# SCH_BMS_1_2022-05-24.net
KiCad netlist of a schematic drawn in EasyEDA
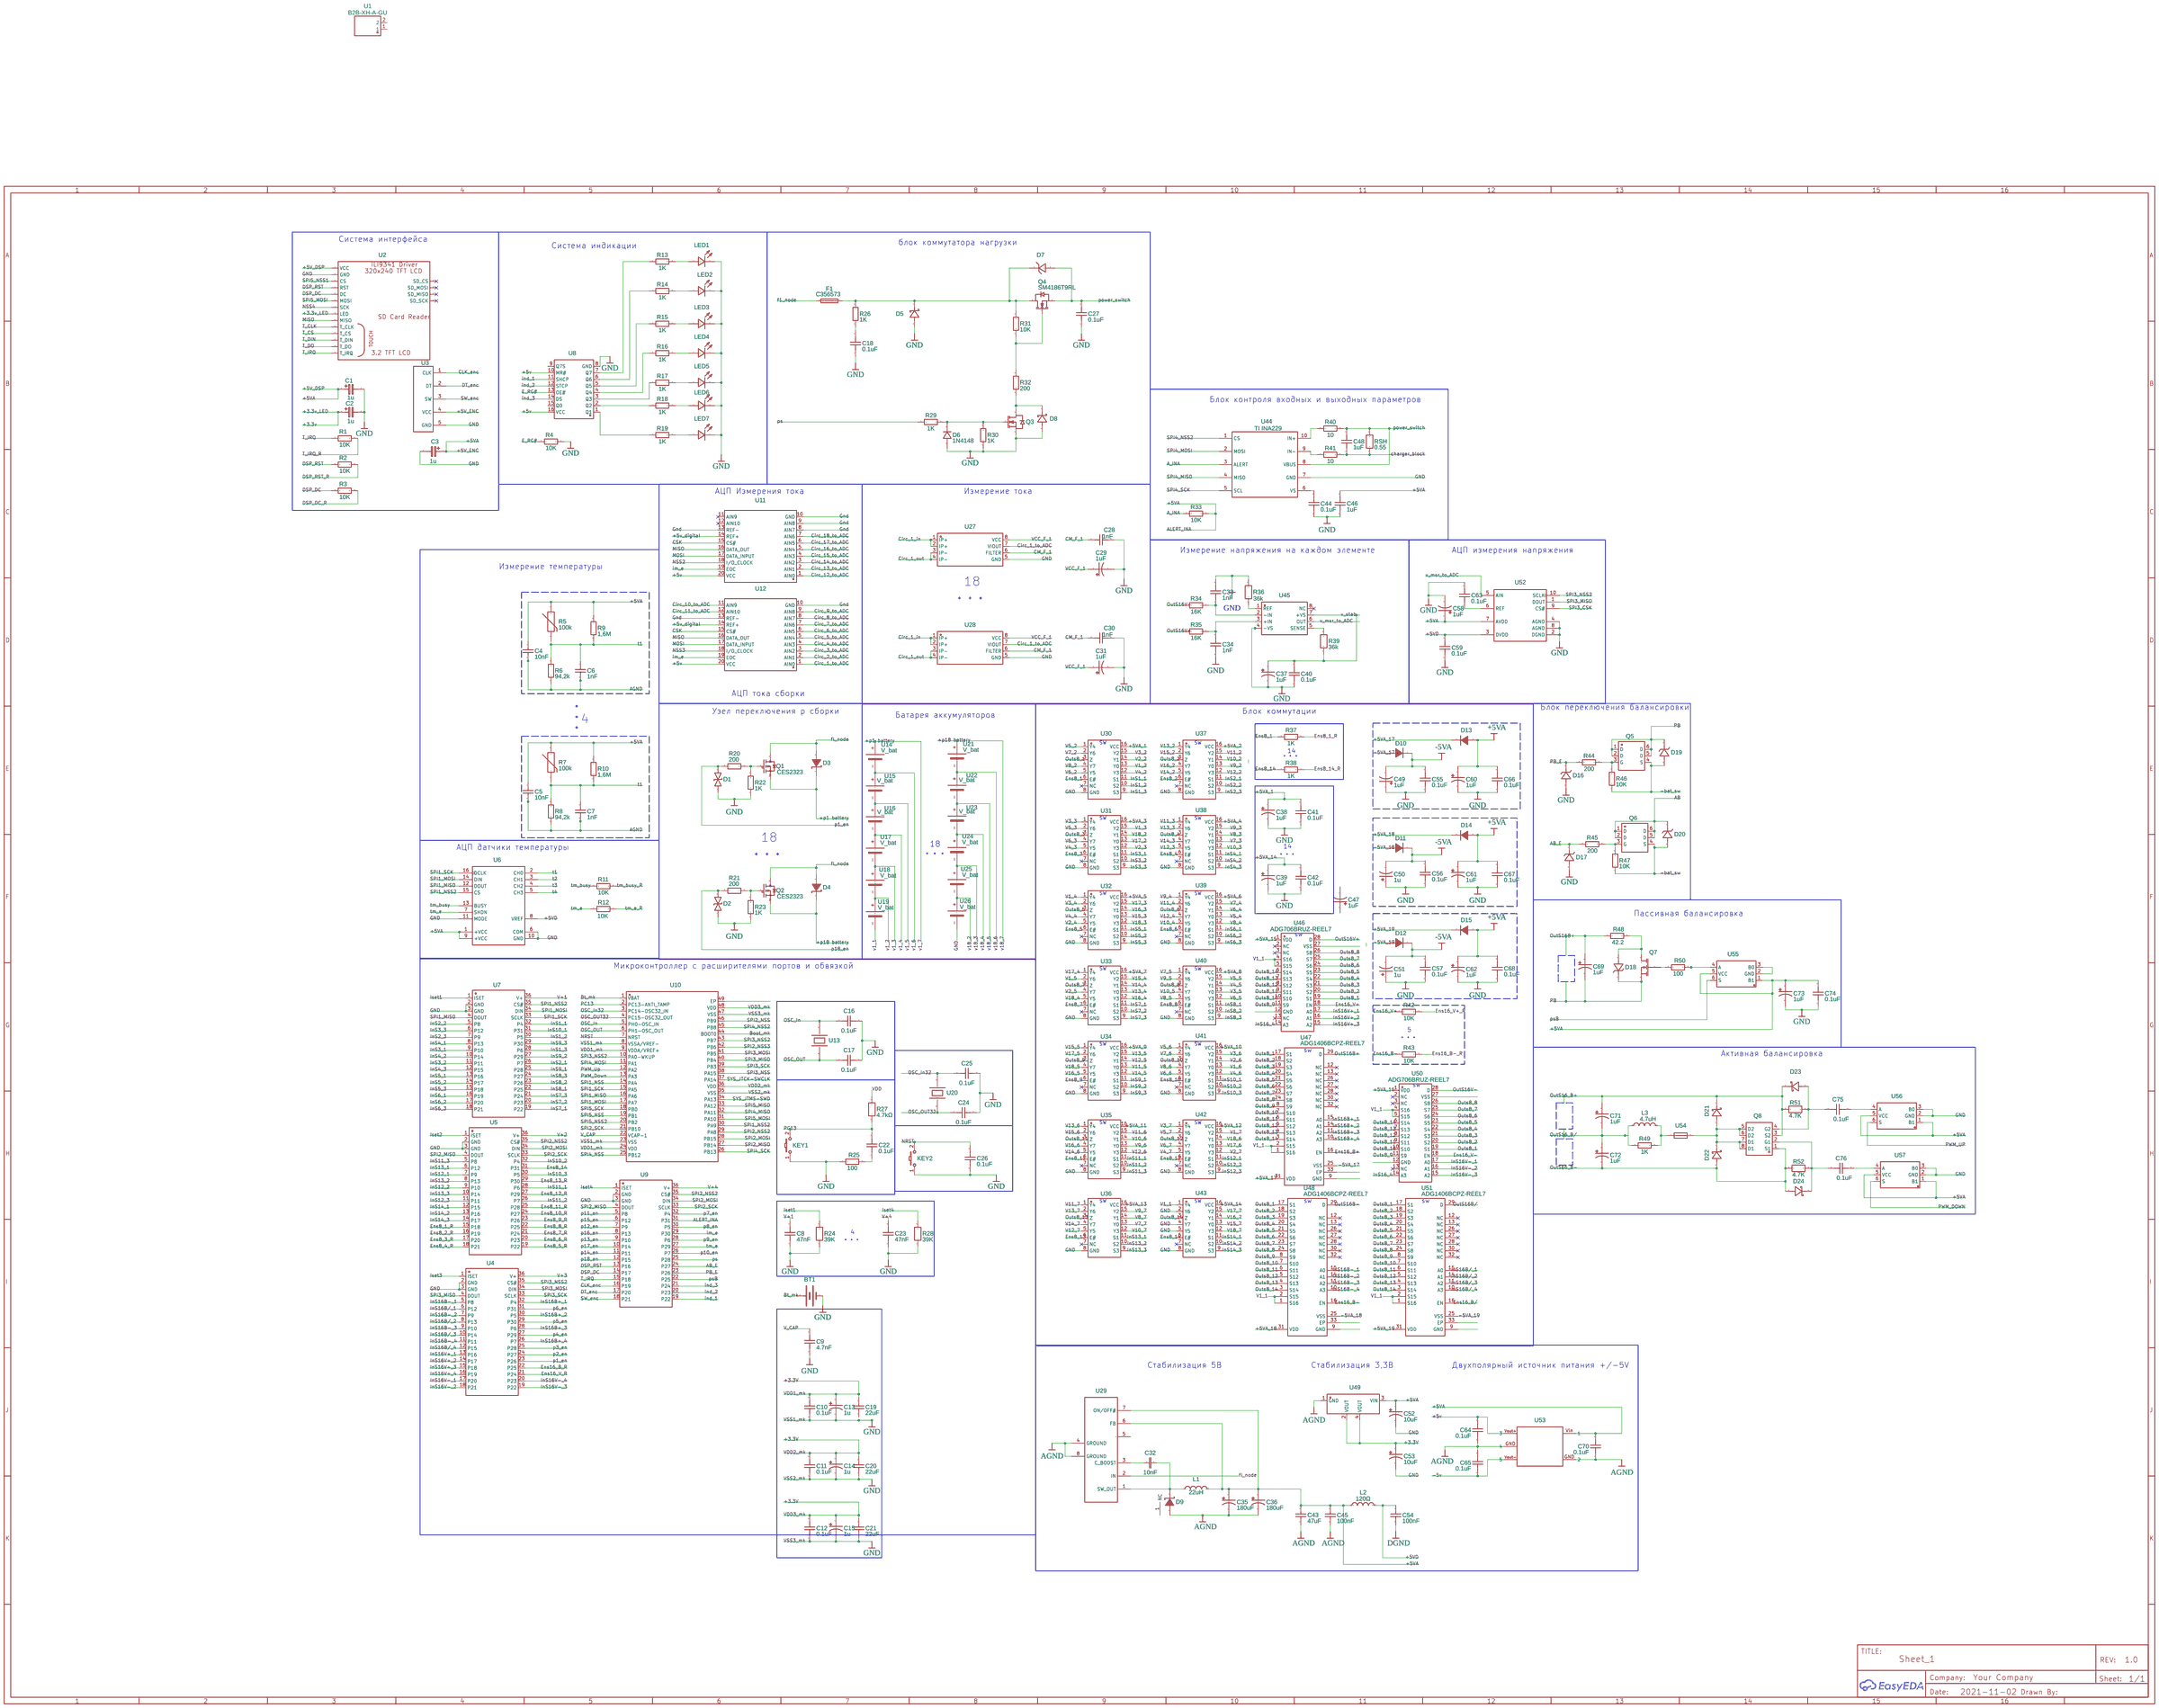
[diagram p0: schematic sheet]

(export (version "E")
  (design (tool "Eeschema 10.0.6"))
  (components
    (comp (ref "BT1")
      (value "1025")
      (fields (field (name "BOM_Supplier Part") "C238060"))
      (libsource (lib "") (part "1025"))
    )
    (comp (ref "C1") (value "1u") (libsource (lib "") (part "C_Tan_SMD_A_EU")))
    (comp (ref "C2") (value "1u") (libsource (lib "") (part "C_Tan_SMD_A_EU")))
    (comp (ref "C3") (value "1u") (libsource (lib "") (part "C_Tan_SMD_A_EU_1")))
    (comp (ref "C4")
      (value "10nF")
      (fields
        (field (name "BOM_Manufacturer Part") "GRM033R71A103KA01D")
        (field (name "BOM_Supplier Part") "C76941")
      )
      (libsource (lib "") (part "GRM033R71A103KA01D"))
    )
    (comp (ref "C5")
      (value "10nF")
      (fields
        (field (name "BOM_Manufacturer Part") "GRM033R71A103KA01D")
        (field (name "BOM_Supplier Part") "C76941")
      )
      (libsource (lib "") (part "GRM033R71A103KA01D"))
    )
    (comp (ref "C6")
      (value "1nF")
      (fields
        (field (name "BOM_Manufacturer Part") "GRM033R71A103KA01D")
        (field (name "BOM_Supplier Part") "C76941")
      )
      (libsource (lib "") (part "GRM033R71A103KA01D"))
    )
    (comp (ref "C7")
      (value "1nF")
      (fields
        (field (name "BOM_Manufacturer Part") "GRM033R71A103KA01D")
        (field (name "BOM_Supplier Part") "C76941")
      )
      (libsource (lib "") (part "GRM033R71A103KA01D"))
    )
    (comp (ref "C8")
      (value "47nF")
      (fields
        (field (name "BOM_Manufacturer Part") "GRT033R60J473KE01D")
        (field (name "BOM_Supplier Part") "C126621")
      )
      (libsource (lib "") (part "GRT033R60J473KE01D"))
    )
    (comp (ref "C9")
      (value "4.7nF")
      (fields
        (field (name "BOM_Manufacturer Part") "CC0201KRX7R5BB472")
        (field (name "BOM_Supplier Part") "C526949")
      )
      (libsource (lib "") (part "CC0201KRX7R5BB472"))
    )
    (comp (ref "C10")
      (value "0.1uF")
      (fields
        (field (name "BOM_Manufacturer Part") "0402BB104K160NGT")
        (field (name "BOM_Supplier Part") "C2173076")
      )
      (libsource (lib "") (part "0402BB104K160NGT"))
    )
    (comp (ref "C11")
      (value "0.1uF")
      (fields
        (field (name "BOM_Manufacturer Part") "0402BB104K160NGT")
        (field (name "BOM_Supplier Part") "C2173076")
      )
      (libsource (lib "") (part "0402BB104K160NGT"))
    )
    (comp (ref "C12")
      (value "0.1uF")
      (fields
        (field (name "BOM_Manufacturer Part") "0402BB104K160NGT")
        (field (name "BOM_Supplier Part") "C2173076")
      )
      (libsource (lib "") (part "0402BB104K160NGT"))
    )
    (comp (ref "C13")
      (value "1u")
      (fields
        (field (name "BOM_Manufacturer Part") "16SVP180MX")
        (field (name "BOM_Supplier Part") "C236288")
      )
      (libsource (lib "") (part "16SVP180MX"))
    )
    (comp (ref "C14")
      (value "1u")
      (fields
        (field (name "BOM_Manufacturer Part") "16SVP180MX")
        (field (name "BOM_Supplier Part") "C236288")
      )
      (libsource (lib "") (part "16SVP180MX"))
    )
    (comp (ref "C15")
      (value "1u")
      (fields
        (field (name "BOM_Manufacturer Part") "16SVP180MX")
        (field (name "BOM_Supplier Part") "C236288")
      )
      (libsource (lib "") (part "16SVP180MX"))
    )
    (comp (ref "C16")
      (value "0.1uF")
      (fields
        (field (name "BOM_Manufacturer Part") "0402BB104K160NGT")
        (field (name "BOM_Supplier Part") "C2173076")
      )
      (libsource (lib "") (part "0402BB104K160NGT_2"))
    )
    (comp (ref "C17")
      (value "0.1uF")
      (fields
        (field (name "BOM_Manufacturer Part") "0402BB104K160NGT")
        (field (name "BOM_Supplier Part") "C2173076")
      )
      (libsource (lib "") (part "0402BB104K160NGT_2"))
    )
    (comp (ref "C18")
      (value "0.1uF")
      (fields
        (field (name "BOM_Manufacturer Part") "0603BB104K500NGT")
        (field (name "BOM_Supplier Part") "C2168571")
      )
      (libsource (lib "") (part "0603BB104K500NGT"))
    )
    (comp (ref "C19")
      (value "22uF")
      (fields
        (field (name "BOM_Manufacturer Part") "GRM188B30J226MEA0D")
        (field (name "BOM_Supplier Part") "C15500")
      )
      (libsource (lib "") (part "GRM188B30J226MEA0D"))
    )
    (comp (ref "C20")
      (value "22uF")
      (fields
        (field (name "BOM_Manufacturer Part") "GRM188B30J226MEA0D")
        (field (name "BOM_Supplier Part") "C15500")
      )
      (libsource (lib "") (part "GRM188B30J226MEA0D"))
    )
    (comp (ref "C21")
      (value "22uF")
      (fields
        (field (name "BOM_Manufacturer Part") "GRM188B30J226MEA0D")
        (field (name "BOM_Supplier Part") "C15500")
      )
      (libsource (lib "") (part "GRM188B30J226MEA0D"))
    )
    (comp (ref "C22")
      (value "0.1uF")
      (fields
        (field (name "BOM_Manufacturer Part") "0402BB104K160NGT")
        (field (name "BOM_Supplier Part") "C2173076")
      )
      (libsource (lib "") (part "0402BB104K160NGT"))
    )
    (comp (ref "C23")
      (value "47nF")
      (fields
        (field (name "BOM_Manufacturer Part") "GRT033R60J473KE01D")
        (field (name "BOM_Supplier Part") "C126621")
      )
      (libsource (lib "") (part "GRT033R60J473KE01D"))
    )
    (comp (ref "C24")
      (value "0.1uF")
      (fields
        (field (name "BOM_Manufacturer Part") "0402BB104K160NGT")
        (field (name "BOM_Supplier Part") "C2173076")
      )
      (libsource (lib "") (part "0402BB104K160NGT_2"))
    )
    (comp (ref "C25")
      (value "0.1uF")
      (fields
        (field (name "BOM_Manufacturer Part") "0402BB104K160NGT")
        (field (name "BOM_Supplier Part") "C2173076")
      )
      (libsource (lib "") (part "0402BB104K160NGT_2"))
    )
    (comp (ref "C26")
      (value "0.1uF")
      (fields
        (field (name "BOM_Manufacturer Part") "0402BB104K160NGT")
        (field (name "BOM_Supplier Part") "C2173076")
      )
      (libsource (lib "") (part "0402BB104K160NGT"))
    )
    (comp (ref "C27")
      (value "0.1uF")
      (fields
        (field (name "BOM_Manufacturer Part") "0603BB104K500NGT")
        (field (name "BOM_Supplier Part") "C2168571")
      )
      (libsource (lib "") (part "0603BB104K500NGT"))
    )
    (comp (ref "C28")
      (value "1nF")
      (fields
        (field (name "BOM_Manufacturer Part") "0201B102J500CT")
        (field (name "BOM_Supplier Part") "C458605")
      )
      (libsource (lib "") (part "0201B102J500CT_1"))
    )
    (comp (ref "C29")
      (value "1uF")
      (fields
        (field (name "BOM_Manufacturer Part") "CA45-A-16V-1uF-K")
        (field (name "BOM_Supplier Part") "C140386")
      )
      (libsource (lib "") (part "CA45-A-16V-1UF-K"))
    )
    (comp (ref "C30")
      (value "1nF")
      (fields
        (field (name "BOM_Manufacturer Part") "0201B102J500CT")
        (field (name "BOM_Supplier Part") "C458605")
      )
      (libsource (lib "") (part "0201B102J500CT_1"))
    )
    (comp (ref "C31")
      (value "1uF")
      (fields
        (field (name "BOM_Manufacturer Part") "CA45-A-16V-1uF-K")
        (field (name "BOM_Supplier Part") "C140386")
      )
      (libsource (lib "") (part "CA45-A-16V-1UF-K"))
    )
    (comp (ref "C32")
      (value "10nF")
      (fields
        (field (name "BOM_Manufacturer Part") "C0603X5R103KDT")
        (field (name "BOM_Supplier Part") "C258479")
      )
      (libsource (lib "") (part "C0603X5R103KDT"))
    )
    (comp (ref "C33")
      (value "1nF")
      (fields
        (field (name "BOM_Manufacturer Part") "0201B102J500CT")
        (field (name "BOM_Supplier Part") "C458605")
      )
      (libsource (lib "") (part "0201B102J500CT"))
    )
    (comp (ref "C34")
      (value "1nF")
      (fields
        (field (name "BOM_Manufacturer Part") "0201B102J500CT")
        (field (name "BOM_Supplier Part") "C458605")
      )
      (libsource (lib "") (part "0201B102J500CT"))
    )
    (comp (ref "C35")
      (value "180uF")
      (fields
        (field (name "BOM_Manufacturer Part") "PCV1V181MCL2GS")
        (field (name "BOM_Supplier Part") "C488000")
      )
      (libsource (lib "") (part "PCV1V181MCL2GS"))
    )
    (comp (ref "C36")
      (value "180uF")
      (fields
        (field (name "BOM_Manufacturer Part") "PCV1V181MCL2GS")
        (field (name "BOM_Supplier Part") "C488000")
      )
      (libsource (lib "") (part "PCV1V181MCL2GS"))
    )
    (comp (ref "C37")
      (value "1uF")
      (fields
        (field (name "BOM_Manufacturer Part") "VE-010M1C0405-TRO")
        (field (name "BOM_Supplier Part") "C249445")
      )
      (libsource (lib "") (part "VE-010M1C0405-TRO"))
    )
    (comp (ref "C38")
      (value "1uF")
      (fields
        (field (name "BOM_Manufacturer Part") "VE-010M1C0405-TRO")
        (field (name "BOM_Supplier Part") "C249445")
      )
      (libsource (lib "") (part "VE-010M1C0405-TRO"))
    )
    (comp (ref "C39")
      (value "1uF")
      (fields
        (field (name "BOM_Manufacturer Part") "VE-010M1C0405-TRO")
        (field (name "BOM_Supplier Part") "C249445")
      )
      (libsource (lib "") (part "VE-010M1C0405-TRO"))
    )
    (comp (ref "C40")
      (value "0.1uF")
      (fields
        (field (name "BOM_Manufacturer Part") "0402BB104K160NGT")
        (field (name "BOM_Supplier Part") "C2173076")
      )
      (libsource (lib "") (part "0402BB104K160NGT"))
    )
    (comp (ref "C41")
      (value "0.1uF")
      (fields
        (field (name "BOM_Manufacturer Part") "0402BB104K160NGT")
        (field (name "BOM_Supplier Part") "C2173076")
      )
      (libsource (lib "") (part "0402BB104K160NGT"))
    )
    (comp (ref "C42")
      (value "0.1uF")
      (fields
        (field (name "BOM_Manufacturer Part") "0402BB104K160NGT")
        (field (name "BOM_Supplier Part") "C2173076")
      )
      (libsource (lib "") (part "0402BB104K160NGT"))
    )
    (comp (ref "C43")
      (value "47uF")
      (fields
        (field (name "BOM_Manufacturer Part") "0805X476M6R3")
        (field (name "BOM_Supplier Part") "C98821")
      )
      (libsource (lib "") (part "0805X476M6R3"))
    )
    (comp (ref "C44")
      (value "0.1uF")
      (fields
        (field (name "BOM_Manufacturer Part") "0402BB104K160NGT")
        (field (name "BOM_Supplier Part") "C2173076")
      )
      (libsource (lib "") (part "0402BB104K160NGT"))
    )
    (comp (ref "C45")
      (value "100nF")
      (fields
        (field (name "BOM_Manufacturer Part") "C0201X6S104K6R3NTA")
        (field (name "BOM_Supplier Part") "C357757")
      )
      (libsource (lib "") (part "C0201X6S104K6R3NTA"))
    )
    (comp (ref "C46")
      (value "1uF")
      (fields
        (field (name "BOM_Manufacturer Part") "CL10F105ZP8NNNC")
        (field (name "BOM_Supplier Part") "C84710")
      )
      (libsource (lib "") (part "CL10F105ZP8NNNC"))
    )
    (comp (ref "C47")
      (value "1uF")
      (fields
        (field (name "BOM_Manufacturer Part") "VE-010M1C0405-TRO")
        (field (name "BOM_Supplier Part") "C249445")
      )
      (libsource (lib "") (part "VE-010M1C0405-TRO_2"))
    )
    (comp (ref "C48")
      (value "1uF")
      (fields
        (field (name "BOM_Manufacturer Part") "CL10F105ZP8NNNC")
        (field (name "BOM_Supplier Part") "C84710")
      )
      (libsource (lib "") (part "CL10F105ZP8NNNC"))
    )
    (comp (ref "C49")
      (value "1uF")
      (fields
        (field (name "BOM_Manufacturer Part") "VE-010M1C0405-TRO")
        (field (name "BOM_Supplier Part") "C249445")
      )
      (libsource (lib "") (part "VE-010M1C0405-TRO_2"))
    )
    (comp (ref "C50") (value "1u") (libsource (lib "") (part "C_Tan_SMD_A_US")))
    (comp (ref "C51") (value "1u") (libsource (lib "") (part "C_Tan_SMD_A_US_1")))
    (comp (ref "C52")
      (value "10uF")
      (fields
        (field (name "BOM_Manufacturer Part") "VE-100M0J0305-TRO")
        (field (name "BOM_Supplier Part") "C249448")
      )
      (libsource (lib "") (part "VE-100M0J0305-TRO"))
    )
    (comp (ref "C53")
      (value "10uF")
      (fields
        (field (name "BOM_Manufacturer Part") "VE-100M0J0305-TRO")
        (field (name "BOM_Supplier Part") "C249448")
      )
      (libsource (lib "") (part "VE-100M0J0305-TRO"))
    )
    (comp (ref "C54")
      (value "100nF")
      (fields
        (field (name "BOM_Manufacturer Part") "C0201X6S104K6R3NTA")
        (field (name "BOM_Supplier Part") "C357757")
      )
      (libsource (lib "") (part "C0201X6S104K6R3NTA"))
    )
    (comp (ref "C55")
      (value "0.1uF")
      (fields
        (field (name "BOM_Manufacturer Part") "0402BB104K160NGT")
        (field (name "BOM_Supplier Part") "C2173076")
      )
      (libsource (lib "") (part "0402BB104K160NGT"))
    )
    (comp (ref "C56")
      (value "0.1uF")
      (fields
        (field (name "BOM_Manufacturer Part") "0402BB104K160NGT")
        (field (name "BOM_Supplier Part") "C2173076")
      )
      (libsource (lib "") (part "0402BB104K160NGT"))
    )
    (comp (ref "C57")
      (value "0.1uF")
      (fields
        (field (name "BOM_Manufacturer Part") "0402BB104K160NGT")
        (field (name "BOM_Supplier Part") "C2173076")
      )
      (libsource (lib "") (part "0402BB104K160NGT"))
    )
    (comp (ref "C58")
      (value "1uF")
      (fields
        (field (name "BOM_Manufacturer Part") "VE-010M1C0405-TRO")
        (field (name "BOM_Supplier Part") "C249445")
      )
      (libsource (lib "") (part "VE-010M1C0405-TRO_2"))
    )
    (comp (ref "C59")
      (value "0.1uF")
      (fields
        (field (name "BOM_Manufacturer Part") "0402BB104K160NGT")
        (field (name "BOM_Supplier Part") "C2173076")
      )
      (libsource (lib "") (part "0402BB104K160NGT"))
    )
    (comp (ref "C60")
      (value "1uF")
      (fields
        (field (name "BOM_Manufacturer Part") "VE-010M1C0405-TRO")
        (field (name "BOM_Supplier Part") "C249445")
      )
      (libsource (lib "") (part "VE-010M1C0405-TRO"))
    )
    (comp (ref "C61")
      (value "1uF")
      (fields
        (field (name "BOM_Manufacturer Part") "VE-010M1C0405-TRO")
        (field (name "BOM_Supplier Part") "C249445")
      )
      (libsource (lib "") (part "VE-010M1C0405-TRO"))
    )
    (comp (ref "C62")
      (value "1uF")
      (fields
        (field (name "BOM_Manufacturer Part") "VE-010M1C0405-TRO")
        (field (name "BOM_Supplier Part") "C249445")
      )
      (libsource (lib "") (part "VE-010M1C0405-TRO_1"))
    )
    (comp (ref "C63")
      (value "0.1uF")
      (fields
        (field (name "BOM_Manufacturer Part") "0402BB104K160NGT")
        (field (name "BOM_Supplier Part") "C2173076")
      )
      (libsource (lib "") (part "0402BB104K160NGT"))
    )
    (comp (ref "C64")
      (value "0.1uF")
      (fields
        (field (name "BOM_Manufacturer Part") "0402BB104K160NGT")
        (field (name "BOM_Supplier Part") "C2173076")
      )
      (libsource (lib "") (part "0402BB104K160NGT_3"))
    )
    (comp (ref "C65")
      (value "0.1uF")
      (fields
        (field (name "BOM_Manufacturer Part") "0402BB104K160NGT")
        (field (name "BOM_Supplier Part") "C2173076")
      )
      (libsource (lib "") (part "0402BB104K160NGT_3"))
    )
    (comp (ref "C66")
      (value "0.1uF")
      (fields
        (field (name "BOM_Manufacturer Part") "0402BB104K160NGT")
        (field (name "BOM_Supplier Part") "C2173076")
      )
      (libsource (lib "") (part "0402BB104K160NGT"))
    )
    (comp (ref "C67")
      (value "0.1uF")
      (fields
        (field (name "BOM_Manufacturer Part") "0402BB104K160NGT")
        (field (name "BOM_Supplier Part") "C2173076")
      )
      (libsource (lib "") (part "0402BB104K160NGT"))
    )
    (comp (ref "C68")
      (value "0.1uF")
      (fields
        (field (name "BOM_Manufacturer Part") "0402BB104K160NGT")
        (field (name "BOM_Supplier Part") "C2173076")
      )
      (libsource (lib "") (part "0402BB104K160NGT"))
    )
    (comp (ref "C69")
      (value "1uF")
      (fields
        (field (name "BOM_Manufacturer Part") "VE-010M1C0405-TRO")
        (field (name "BOM_Supplier Part") "C249445")
      )
      (libsource (lib "") (part "VE-010M1C0405-TRO_1"))
    )
    (comp (ref "C70")
      (value "0.1uF")
      (fields
        (field (name "BOM_Manufacturer Part") "0402BB104K160NGT")
        (field (name "BOM_Supplier Part") "C2173076")
      )
      (libsource (lib "") (part "0402BB104K160NGT_3"))
    )
    (comp (ref "C71")
      (value "1uF")
      (fields
        (field (name "BOM_Manufacturer Part") "VE-010M1C0405-TRO")
        (field (name "BOM_Supplier Part") "C249445")
      )
      (libsource (lib "") (part "VE-010M1C0405-TRO"))
    )
    (comp (ref "C72")
      (value "1uF")
      (fields
        (field (name "BOM_Manufacturer Part") "VE-010M1C0405-TRO")
        (field (name "BOM_Supplier Part") "C249445")
      )
      (libsource (lib "") (part "VE-010M1C0405-TRO_1"))
    )
    (comp (ref "C73")
      (value "1uF")
      (fields
        (field (name "BOM_Manufacturer Part") "VE-010M1C0405-TRO")
        (field (name "BOM_Supplier Part") "C249445")
      )
      (libsource (lib "") (part "VE-010M1C0405-TRO_1"))
    )
    (comp (ref "C74")
      (value "0.1uF")
      (fields
        (field (name "BOM_Manufacturer Part") "0402BB104K160NGT")
        (field (name "BOM_Supplier Part") "C2173076")
      )
      (libsource (lib "") (part "0402BB104K160NGT"))
    )
    (comp (ref "C75")
      (value "0.1uF")
      (fields
        (field (name "BOM_Manufacturer Part") "0402BB104K160NGT")
        (field (name "BOM_Supplier Part") "C2173076")
      )
      (libsource (lib "") (part "0402BB104K160NGT_1"))
    )
    (comp (ref "C76")
      (value "0.1uF")
      (fields
        (field (name "BOM_Manufacturer Part") "0402BB104K160NGT")
        (field (name "BOM_Supplier Part") "C2173076")
      )
      (libsource (lib "") (part "0402BB104K160NGT_1"))
    )
    (comp (ref "D1")
      (value "UCLAMP0541Z.TFT")
      (fields (field (name "BOM_Supplier Part") "C193630"))
      (libsource (lib "") (part "UCLAMP0541Z.TFT"))
    )
    (comp (ref "D2")
      (value "UCLAMP0541Z.TFT")
      (fields (field (name "BOM_Supplier Part") "C193630"))
      (libsource (lib "") (part "UCLAMP0541Z.TFT"))
    )
    (comp (ref "D3")
      (value "1.0SMBJ30A")
      (fields
        (field (name "BOM_Manufacturer Part") "1.0SMBJ20A")
        (field (name "BOM_Supplier Part") "C501367")
      )
      (libsource (lib "") (part "1.0SMBJ20A"))
    )
    (comp (ref "D4")
      (value "1.0SMBJ30A")
      (fields
        (field (name "BOM_Manufacturer Part") "1.0SMBJ20A")
        (field (name "BOM_Supplier Part") "C501367")
      )
      (libsource (lib "") (part "1.0SMBJ20A"))
    )
    (comp (ref "D5")
      (value "PMEG3020EGWJ")
      (fields (field (name "BOM_Supplier Part") "C552875"))
      (libsource (lib "") (part "PMEG3020EGWJ"))
    )
    (comp (ref "D6")
      (value "1N4148")
      (fields (field (name "BOM_Supplier Part") "C14516"))
      (libsource (lib "") (part "1N4148"))
    )
    (comp (ref "D7")
      (value "1SMAF4751A_C475445")
      (fields
        (field (name "BOM_Manufacturer Part") "1SMAF4751A")
        (field (name "BOM_Supplier Part") "C475445")
      )
      (libsource (lib "") (part "1SMAF4751A_C475445"))
    )
    (comp (ref "D8")
      (value "PMEG3020EGWJ")
      (fields (field (name "BOM_Supplier Part") "C552875"))
      (libsource (lib "") (part "PMEG3020EGWJ"))
    )
    (comp (ref "D9")
      (value "VS-6TQ045SPBF")
      (fields (field (name "BOM_Supplier Part") "C145462"))
      (libsource (lib "") (part "VS-6TQ045SPBF"))
    )
    (comp (ref "D10")
      (value "WSB5557Z-2/TR")
      (fields (field (name "BOM_Supplier Part") "C239812"))
      (libsource (lib "") (part "WSB5557Z-2/TR"))
    )
    (comp (ref "D11")
      (value "WSB5557Z-2/TR")
      (fields (field (name "BOM_Supplier Part") "C239812"))
      (libsource (lib "") (part "WSB5557Z-2/TR"))
    )
    (comp (ref "D12")
      (value "WSB5557Z-2/TR")
      (fields (field (name "BOM_Supplier Part") "C239812"))
      (libsource (lib "") (part "WSB5557Z-2/TR"))
    )
    (comp (ref "D13")
      (value "WSB5557Z-2/TR")
      (fields (field (name "BOM_Supplier Part") "C239812"))
      (libsource (lib "") (part "WSB5557Z-2/TR_1"))
    )
    (comp (ref "D14")
      (value "WSB5557Z-2/TR")
      (fields (field (name "BOM_Supplier Part") "C239812"))
      (libsource (lib "") (part "WSB5557Z-2/TR_1"))
    )
    (comp (ref "D15")
      (value "WSB5557Z-2/TR")
      (fields (field (name "BOM_Supplier Part") "C239812"))
      (libsource (lib "") (part "WSB5557Z-2/TR_1"))
    )
    (comp (ref "D16")
      (value "MMSZ5233BS-7-F")
      (fields (field (name "BOM_Supplier Part") "C508230"))
      (libsource (lib "") (part "MMSZ5233BS-7-F"))
    )
    (comp (ref "D17")
      (value "MMSZ5233BS-7-F")
      (fields (field (name "BOM_Supplier Part") "C508230"))
      (libsource (lib "") (part "MMSZ5233BS-7-F"))
    )
    (comp (ref "D18")
      (value "BZT52B10S RRG")
      (fields (field (name "BOM_Supplier Part") "C485479"))
      (libsource (lib "") (part "BZT52B10S RRG"))
    )
    (comp (ref "D19")
      (value "BZT52B10S RRG")
      (fields (field (name "BOM_Supplier Part") "C485479"))
      (libsource (lib "") (part "BZT52B10S RRG_1"))
    )
    (comp (ref "D20")
      (value "BZT52B10S RRG")
      (fields (field (name "BOM_Supplier Part") "C485479"))
      (libsource (lib "") (part "BZT52B10S RRG_1"))
    )
    (comp (ref "D21")
      (value "PMEG3020EGWJ")
      (fields (field (name "BOM_Supplier Part") "C552875"))
      (libsource (lib "") (part "PMEG3020EGWJ"))
    )
    (comp (ref "D22")
      (value "PMEG3020EGWJ")
      (fields (field (name "BOM_Supplier Part") "C552875"))
      (libsource (lib "") (part "PMEG3020EGWJ"))
    )
    (comp (ref "D23")
      (value "PMEG3020EGWJ")
      (fields (field (name "BOM_Supplier Part") "C552875"))
      (libsource (lib "") (part "PMEG3020EGWJ_1"))
    )
    (comp (ref "D24")
      (value "PMEG3020EGWJ")
      (fields (field (name "BOM_Supplier Part") "C552875"))
      (libsource (lib "") (part "PMEG3020EGWJ_2"))
    )
    (comp (ref "F1")
      (value "C356573")
      (fields (field (name "BOM_Manufacturer Part") "25F-100H"))
      (libsource (lib "") (part "25F-100H"))
    )
    (comp (ref "KEY1")
      (value "K2-3.6×6.1_SMD")
      (fields
        (field (name "BOM_Manufacturer Part") "K2-1107ST-A4SW-06")
        (field (name "BOM_Supplier Part") "C118141")
      )
      (libsource (lib "") (part "K2-3.6×6.1_SMD"))
    )
    (comp (ref "KEY2")
      (value "K2-3.6×6.1_SMD")
      (fields
        (field (name "BOM_Manufacturer Part") "K2-1107ST-A4SW-06")
        (field (name "BOM_Supplier Part") "C118141")
      )
      (libsource (lib "") (part "K2-3.6×6.1_SMD"))
    )
    (comp (ref "L1")
      (value "22uH")
      (fields
        (field (name "BOM_Manufacturer Part") "LQH44PN220MP0L")
        (field (name "BOM_Supplier Part") "C341778")
      )
      (libsource (lib "") (part "LQH44PN220MP0L"))
    )
    (comp (ref "L2")
      (value "120Ω")
      (fields
        (field (name "BOM_Manufacturer Part") "BLM21PG121SZ1D")
        (field (name "BOM_Supplier Part") "C160987")
      )
      (libsource (lib "") (part "BLM21PG121SZ1D"))
    )
    (comp (ref "L3")
      (value "4.7uH")
      (fields
        (field (name "BOM_Manufacturer Part") "CKCS4030-4.7uH/M-2131")
        (field (name "BOM_Supplier Part") "C354588")
      )
      (libsource (lib "") (part "CKCS4030-4.7UH/M-2131"))
    )
    (comp (ref "LED1")
      (value "LED-0603_R")
      (fields
        (field (name "BOM_Manufacturer Part") "19-217/R6C-AL1M2VY/3T")
        (field (name "BOM_Supplier Part") "C72044")
      )
      (libsource (lib "") (part "LED-0603_R"))
    )
    (comp (ref "LED2")
      (value "LED-0603_R")
      (fields
        (field (name "BOM_Manufacturer Part") "19-217/R6C-AL1M2VY/3T")
        (field (name "BOM_Supplier Part") "C72044")
      )
      (libsource (lib "") (part "LED-0603_R"))
    )
    (comp (ref "LED3")
      (value "LED-0603_R")
      (fields
        (field (name "BOM_Manufacturer Part") "19-217/R6C-AL1M2VY/3T")
        (field (name "BOM_Supplier Part") "C72044")
      )
      (libsource (lib "") (part "LED-0603_R"))
    )
    (comp (ref "LED4")
      (value "LED-0603_R")
      (fields
        (field (name "BOM_Manufacturer Part") "19-217/R6C-AL1M2VY/3T")
        (field (name "BOM_Supplier Part") "C72044")
      )
      (libsource (lib "") (part "LED-0603_R"))
    )
    (comp (ref "LED5")
      (value "LED-0603_R")
      (fields
        (field (name "BOM_Manufacturer Part") "19-217/R6C-AL1M2VY/3T")
        (field (name "BOM_Supplier Part") "C72044")
      )
      (libsource (lib "") (part "LED-0603_R"))
    )
    (comp (ref "LED6")
      (value "LED-0603_R")
      (fields
        (field (name "BOM_Manufacturer Part") "19-217/R6C-AL1M2VY/3T")
        (field (name "BOM_Supplier Part") "C72044")
      )
      (libsource (lib "") (part "LED-0603_R"))
    )
    (comp (ref "LED7")
      (value "LED-0603_R")
      (fields
        (field (name "BOM_Manufacturer Part") "19-217/R6C-AL1M2VY/3T")
        (field (name "BOM_Supplier Part") "C72044")
      )
      (libsource (lib "") (part "LED-0603_R"))
    )
    (comp (ref "Q1")
      (value "CES2323")
      (fields (field (name "BOM_Supplier Part") "C83044"))
      (libsource (lib "") (part "CES2323"))
    )
    (comp (ref "Q2")
      (value "CES2323")
      (fields (field (name "BOM_Supplier Part") "C83044"))
      (libsource (lib "") (part "CES2323"))
    )
    (comp (ref "Q3")
      (value "SM2326NSANC-TRG")
      (fields (field (name "BOM_Supplier Part") "C368561"))
      (libsource (lib "") (part "SM2326NSANC-TRG"))
    )
    (comp (ref "Q4")
      (value "SM4186T9RL")
      (fields (field (name "BOM_Supplier Part") "C496601"))
      (libsource (lib "") (part "SM4186T9RL"))
    )
    (comp (ref "Q5")
      (value "SI1422DH-T1-GE3")
      (fields (field (name "BOM_Supplier Part") "C144842"))
      (libsource (lib "") (part "SI1422DH-T1-GE3"))
    )
    (comp (ref "Q6")
      (value "SI1422DH-T1-GE3")
      (fields (field (name "BOM_Supplier Part") "C144842"))
      (libsource (lib "") (part "SI1422DH-T1-GE3"))
    )
    (comp (ref "Q7") (value "MTN003N02Y3") (libsource (lib "") (part "SLS2302")))
    (comp (ref "Q8")
      (value "FDS4897A")
      (fields (field (name "BOM_Supplier Part") "C693180"))
      (libsource (lib "") (part "FDS4897A"))
    )
    (comp (ref "R1")
      (value "10K")
      (fields
        (field (name "BOM_Manufacturer Part") "0603WAF1002T5E")
        (field (name "BOM_Supplier Part") "C25804")
      )
      (libsource (lib "") (part "0603WAF1002T5E"))
    )
    (comp (ref "R2")
      (value "10K")
      (fields
        (field (name "BOM_Manufacturer Part") "0603WAF1002T5E")
        (field (name "BOM_Supplier Part") "C25804")
      )
      (libsource (lib "") (part "0603WAF1002T5E"))
    )
    (comp (ref "R3")
      (value "10K")
      (fields
        (field (name "BOM_Manufacturer Part") "0603WAF1002T5E")
        (field (name "BOM_Supplier Part") "C25804")
      )
      (libsource (lib "") (part "0603WAF1002T5E"))
    )
    (comp (ref "R4")
      (value "10K")
      (fields
        (field (name "BOM_Manufacturer Part") "0603WAF1002T5E")
        (field (name "BOM_Supplier Part") "C25804")
      )
      (libsource (lib "") (part "0603WAF1002T5E"))
    )
    (comp (ref "R5")
      (value "100k")
      (fields
        (field (name "BOM_Manufacturer Part") "MF52A1104F3950(P209-15A)")
        (field (name "BOM_Supplier Part") "C13424")
      )
      (libsource (lib "") (part "MF52A1104F3950(P209-15A)"))
    )
    (comp (ref "R6")
      (value "94,2k")
      (fields
        (field (name "BOM_Manufacturer Part") "WR02X1873FAL")
        (field (name "BOM_Supplier Part") "C171920")
      )
      (libsource (lib "") (part "WR02X1873FAL"))
    )
    (comp (ref "R7")
      (value "100k")
      (fields
        (field (name "BOM_Manufacturer Part") "MF52A1104F3950(P209-15A)")
        (field (name "BOM_Supplier Part") "C13424")
      )
      (libsource (lib "") (part "MF52A1104F3950(P209-15A)"))
    )
    (comp (ref "R8")
      (value "94,2k")
      (fields
        (field (name "BOM_Manufacturer Part") "WR02X1873FAL")
        (field (name "BOM_Supplier Part") "C171920")
      )
      (libsource (lib "") (part "WR02X1873FAL"))
    )
    (comp (ref "R9")
      (value "1,6M")
      (fields
        (field (name "BOM_Manufacturer Part") "CR1206-FX-1603ELF")
        (field (name "BOM_Supplier Part") "C204681")
      )
      (libsource (lib "") (part "CR1206-FX-1603ELF"))
    )
    (comp (ref "R10")
      (value "1,6M")
      (fields
        (field (name "BOM_Manufacturer Part") "CR1206-FX-1603ELF")
        (field (name "BOM_Supplier Part") "C204681")
      )
      (libsource (lib "") (part "CR1206-FX-1603ELF"))
    )
    (comp (ref "R11")
      (value "10K")
      (fields
        (field (name "BOM_Manufacturer Part") "0603WAF1002T5E")
        (field (name "BOM_Supplier Part") "C25804")
      )
      (libsource (lib "") (part "0603WAF1002T5E"))
    )
    (comp (ref "R12")
      (value "10K")
      (fields
        (field (name "BOM_Manufacturer Part") "0603WAF1002T5E")
        (field (name "BOM_Supplier Part") "C25804")
      )
      (libsource (lib "") (part "0603WAF1002T5E"))
    )
    (comp (ref "R13")
      (value "1K")
      (fields
        (field (name "BOM_Manufacturer Part") "CR1206F41001G")
        (field (name "BOM_Supplier Part") "C102060")
      )
      (libsource (lib "") (part "CR1206F41001G"))
    )
    (comp (ref "R14")
      (value "1K")
      (fields
        (field (name "BOM_Manufacturer Part") "CR1206F41001G")
        (field (name "BOM_Supplier Part") "C102060")
      )
      (libsource (lib "") (part "CR1206F41001G"))
    )
    (comp (ref "R15")
      (value "1K")
      (fields
        (field (name "BOM_Manufacturer Part") "CR1206F41001G")
        (field (name "BOM_Supplier Part") "C102060")
      )
      (libsource (lib "") (part "CR1206F41001G"))
    )
    (comp (ref "R16")
      (value "1K")
      (fields
        (field (name "BOM_Manufacturer Part") "CR1206F41001G")
        (field (name "BOM_Supplier Part") "C102060")
      )
      (libsource (lib "") (part "CR1206F41001G"))
    )
    (comp (ref "R17")
      (value "1K")
      (fields
        (field (name "BOM_Manufacturer Part") "CR1206F41001G")
        (field (name "BOM_Supplier Part") "C102060")
      )
      (libsource (lib "") (part "CR1206F41001G"))
    )
    (comp (ref "R18")
      (value "1K")
      (fields
        (field (name "BOM_Manufacturer Part") "CR1206F41001G")
        (field (name "BOM_Supplier Part") "C102060")
      )
      (libsource (lib "") (part "CR1206F41001G"))
    )
    (comp (ref "R19")
      (value "1K")
      (fields
        (field (name "BOM_Manufacturer Part") "CR1206F41001G")
        (field (name "BOM_Supplier Part") "C102060")
      )
      (libsource (lib "") (part "CR1206F41001G"))
    )
    (comp (ref "R20")
      (value "200")
      (fields
        (field (name "BOM_Manufacturer Part") "RMC12062005%N")
        (field (name "BOM_Supplier Part") "C269602")
      )
      (libsource (lib "") (part "RMC12062005%N"))
    )
    (comp (ref "R21")
      (value "200")
      (fields
        (field (name "BOM_Manufacturer Part") "RMC12062005%N")
        (field (name "BOM_Supplier Part") "C269602")
      )
      (libsource (lib "") (part "RMC12062005%N"))
    )
    (comp (ref "R22")
      (value "1K")
      (fields
        (field (name "BOM_Manufacturer Part") "CR1206F41001G")
        (field (name "BOM_Supplier Part") "C102060")
      )
      (libsource (lib "") (part "CR1206F41001G_1"))
    )
    (comp (ref "R23")
      (value "1K")
      (fields
        (field (name "BOM_Manufacturer Part") "CR1206F41001G")
        (field (name "BOM_Supplier Part") "C102060")
      )
      (libsource (lib "") (part "CR1206F41001G_1"))
    )
    (comp (ref "R24")
      (value "39K")
      (fields
        (field (name "BOM_Manufacturer Part") "ERJ6ENF3902V")
        (field (name "BOM_Supplier Part") "C413307")
      )
      (libsource (lib "") (part "ERJ6ENF3902V"))
    )
    (comp (ref "R25")
      (value "100")
      (fields
        (field (name "BOM_Manufacturer Part") "CR1206F100RP05")
        (field (name "BOM_Supplier Part") "C245445")
      )
      (libsource (lib "") (part "CR1206F100RP05"))
    )
    (comp (ref "R26")
      (value "1K")
      (fields
        (field (name "BOM_Manufacturer Part") "CR1206F41001G")
        (field (name "BOM_Supplier Part") "C102060")
      )
      (libsource (lib "") (part "CR1206F41001G_1"))
    )
    (comp (ref "R27")
      (value "4.7kΩ")
      (fields
        (field (name "BOM_Manufacturer Part") "RK73G2ATTD4701F")
        (field (name "BOM_Supplier Part") "C516091")
      )
      (libsource (lib "") (part "RK73G2ATTD4701F"))
    )
    (comp (ref "R28")
      (value "39K")
      (fields
        (field (name "BOM_Manufacturer Part") "ERJ6ENF3902V")
        (field (name "BOM_Supplier Part") "C413307")
      )
      (libsource (lib "") (part "ERJ6ENF3902V"))
    )
    (comp (ref "R29")
      (value "1K")
      (fields
        (field (name "BOM_Manufacturer Part") "RMC12061K5%N")
        (field (name "BOM_Supplier Part") "C269755")
      )
      (libsource (lib "") (part "RMC12061K5%N"))
    )
    (comp (ref "R30")
      (value "1K")
      (fields
        (field (name "BOM_Manufacturer Part") "RMC12061K5%N")
        (field (name "BOM_Supplier Part") "C269755")
      )
      (libsource (lib "") (part "RMC12061K5%N_1"))
    )
    (comp (ref "R31")
      (value "10K")
      (fields
        (field (name "BOM_Manufacturer Part") "0603WAF1002T5E")
        (field (name "BOM_Supplier Part") "C25804")
      )
      (libsource (lib "") (part "0603WAF1002T5E_1"))
    )
    (comp (ref "R32")
      (value "200")
      (fields
        (field (name "BOM_Manufacturer Part") "RMC12062005%N")
        (field (name "BOM_Supplier Part") "C269602")
      )
      (libsource (lib "") (part "RMC12062005%N_1"))
    )
    (comp (ref "R33")
      (value "10K")
      (fields
        (field (name "BOM_Manufacturer Part") "RNCF0402BTE10K0")
        (field (name "BOM_Supplier Part") "C346559")
      )
      (libsource (lib "") (part "RNCF0402BTE10K0"))
    )
    (comp (ref "R34")
      (value "16K")
      (fields
        (field (name "BOM_Manufacturer Part") "CR1206-FX-1602ELF")
        (field (name "BOM_Supplier Part") "C204680")
      )
      (libsource (lib "") (part "CR1206-FX-1602ELF"))
    )
    (comp (ref "R35")
      (value "16K")
      (fields
        (field (name "BOM_Manufacturer Part") "CR1206-FX-1602ELF")
        (field (name "BOM_Supplier Part") "C204680")
      )
      (libsource (lib "") (part "CR1206-FX-1602ELF"))
    )
    (comp (ref "R36")
      (value "36k")
      (fields
        (field (name "BOM_Manufacturer Part") "RK73H2BTTD3602F")
        (field (name "BOM_Supplier Part") "C880208")
      )
      (libsource (lib "") (part "RK73H2BTTD3602F"))
    )
    (comp (ref "R37")
      (value "1K")
      (fields
        (field (name "BOM_Manufacturer Part") "RC-01W103JT")
        (field (name "BOM_Supplier Part") "C304504")
      )
      (libsource (lib "") (part "RC-01W103JT"))
    )
    (comp (ref "R38")
      (value "1K")
      (fields
        (field (name "BOM_Manufacturer Part") "RC-01W103JT")
        (field (name "BOM_Supplier Part") "C304504")
      )
      (libsource (lib "") (part "RC-01W103JT"))
    )
    (comp (ref "R39")
      (value "36k")
      (fields
        (field (name "BOM_Manufacturer Part") "RK73H2BTTD3602F")
        (field (name "BOM_Supplier Part") "C880208")
      )
      (libsource (lib "") (part "RK73H2BTTD3602F"))
    )
    (comp (ref "R40")
      (value "10")
      (fields
        (field (name "BOM_Manufacturer Part") "RMC1206101%N")
        (field (name "BOM_Supplier Part") "C269633")
      )
      (libsource (lib "") (part "RMC1206101%N"))
    )
    (comp (ref "R41")
      (value "10")
      (fields
        (field (name "BOM_Manufacturer Part") "RMC1206101%N")
        (field (name "BOM_Supplier Part") "C269633")
      )
      (libsource (lib "") (part "RMC1206101%N"))
    )
    (comp (ref "R42")
      (value "10K")
      (fields
        (field (name "BOM_Manufacturer Part") "RC-01W103JT")
        (field (name "BOM_Supplier Part") "C304504")
      )
      (libsource (lib "") (part "RC-01W103JT"))
    )
    (comp (ref "R43")
      (value "10K")
      (fields
        (field (name "BOM_Manufacturer Part") "RC-01W103JT")
        (field (name "BOM_Supplier Part") "C304504")
      )
      (libsource (lib "") (part "RC-01W103JT"))
    )
    (comp (ref "R44")
      (value "200")
      (fields
        (field (name "BOM_Manufacturer Part") "RMC12062005%N")
        (field (name "BOM_Supplier Part") "C269602")
      )
      (libsource (lib "") (part "RMC12062005%N"))
    )
    (comp (ref "R45")
      (value "200")
      (fields
        (field (name "BOM_Manufacturer Part") "RMC12062005%N")
        (field (name "BOM_Supplier Part") "C269602")
      )
      (libsource (lib "") (part "RMC12062005%N"))
    )
    (comp (ref "R46")
      (value "10K")
      (fields
        (field (name "BOM_Manufacturer Part") "RC-01W103JT")
        (field (name "BOM_Supplier Part") "C304504")
      )
      (libsource (lib "") (part "RC-01W103JT_1"))
    )
    (comp (ref "R47")
      (value "10K")
      (fields
        (field (name "BOM_Manufacturer Part") "RC-01W103JT")
        (field (name "BOM_Supplier Part") "C304504")
      )
      (libsource (lib "") (part "RC-01W103JT_1"))
    )
    (comp (ref "R48")
      (value "42.2")
      (fields
        (field (name "BOM_Manufacturer Part") "RC-12K42R2FT")
        (field (name "BOM_Supplier Part") "C454007")
      )
      (libsource (lib "") (part "RC-12K42R2FT"))
    )
    (comp (ref "R49")
      (value "1K")
      (fields
        (field (name "BOM_Manufacturer Part") "TR1218F1KE0450")
        (field (name "BOM_Supplier Part") "C175641")
      )
      (libsource (lib "") (part "TR1218F1KE0450"))
    )
    (comp (ref "R50")
      (value "100")
      (fields
        (field (name "BOM_Manufacturer Part") "FCR1206J100RP055W")
        (field (name "BOM_Supplier Part") "C153338")
      )
      (libsource (lib "") (part "FCR1206J100RP055W"))
    )
    (comp (ref "R51")
      (value "4.7K")
      (fields (field (name "BOM_Manufacturer Part") "К") (field (name "BOM_Supplier Part") "C427213"))
      (libsource (lib "") (part "ERJPA2J472X"))
    )
    (comp (ref "R52")
      (value "4.7K")
      (fields
        (field (name "BOM_Manufacturer Part") "ERJPA2J472X")
        (field (name "BOM_Supplier Part") "C427213")
      )
      (libsource (lib "") (part "ERJPA2J472X"))
    )
    (comp (ref "RSH")
      (value "0.55")
      (fields (field (name "BOM_Manufacturer Part") "CSS1206DT50L0"))
      (libsource (lib "") (part "R_0603_EU"))
    )
    (comp (ref "U1")
      (value "B2B-XH-A-GU")
      (fields (field (name "BOM_Supplier Part") "C265283"))
      (libsource (lib "") (part "B2B-XH-A-GU"))
    )
    (comp (ref "U2") (value "3.2_TFT_LCD_SPI_TOUCH") (libsource (lib "") (part "3.2_TFT_LCD_SPI_TOUCH")))
    (comp (ref "U3")
      (value "Rotary_encoder_module")
      (fields (field (name "BOM_Supplier Part") "undefined"))
      (libsource (lib "") (part "Rotary_encoder_module"))
    )
    (comp (ref "U4")
      (value "MAX7301AAX+")
      (fields (field (name "BOM_Supplier Part") "C143583"))
      (libsource (lib "") (part "MAX7301AAX+"))
    )
    (comp (ref "U5")
      (value "MAX7301AAX+")
      (fields (field (name "BOM_Supplier Part") "C143583"))
      (libsource (lib "") (part "MAX7301AAX+"))
    )
    (comp (ref "U6")
      (value "ADS7841E/2K5")
      (fields (field (name "BOM_Supplier Part") "C41778"))
      (libsource (lib "") (part "ADS7841E/2K5"))
    )
    (comp (ref "U7")
      (value "MAX7301AAX+")
      (fields (field (name "BOM_Supplier Part") "C143583"))
      (libsource (lib "") (part "MAX7301AAX+"))
    )
    (comp (ref "U8")
      (value "74HC595PW,112")
      (fields (field (name "BOM_Supplier Part") "C547128"))
      (libsource (lib "") (part "74HC595PW,112"))
    )
    (comp (ref "U9")
      (value "MAX7301AAX+")
      (fields (field (name "BOM_Supplier Part") "C143583"))
      (libsource (lib "") (part "MAX7301AAX+"))
    )
    (comp (ref "U10")
      (value "STM32F411CCU6TR")
      (fields (field (name "BOM_Supplier Part") "C190642"))
      (libsource (lib "") (part "STM32F411CCU6TR"))
    )
    (comp (ref "U11")
      (value "TLC2543N")
      (fields (field (name "BOM_Supplier Part") "C398066"))
      (libsource (lib "") (part "TLC2543N"))
    )
    (comp (ref "U12")
      (value "TLC2543N")
      (fields (field (name "BOM_Supplier Part") "C398066"))
      (libsource (lib "") (part "TLC2543N"))
    )
    (comp (ref "U13") (value "SMAQ-7050A") (libsource (lib "") (part "SMAQ-7050A")))
    (comp (ref "U14") (value "V_bat") (libsource (lib "") (part "V_bat")))
    (comp (ref "U15") (value "V_bat") (libsource (lib "") (part "V_bat")))
    (comp (ref "U16") (value "V_bat") (libsource (lib "") (part "V_bat")))
    (comp (ref "U17") (value "V_bat") (libsource (lib "") (part "V_bat")))
    (comp (ref "U18") (value "V_bat") (libsource (lib "") (part "V_bat")))
    (comp (ref "U19") (value "V_bat") (libsource (lib "") (part "V_bat")))
    (comp (ref "U20") (value "SMAQ-7050A") (libsource (lib "") (part "SMAQ-7050A")))
    (comp (ref "U21") (value "V_bat") (libsource (lib "") (part "V_bat")))
    (comp (ref "U22") (value "V_bat") (libsource (lib "") (part "V_bat")))
    (comp (ref "U23") (value "V_bat") (libsource (lib "") (part "V_bat")))
    (comp (ref "U24") (value "V_bat") (libsource (lib "") (part "V_bat")))
    (comp (ref "U25") (value "V_bat") (libsource (lib "") (part "V_bat")))
    (comp (ref "U26") (value "V_bat") (libsource (lib "") (part "V_bat")))
    (comp (ref "U27")
      (value "ACS714LLCTR-50A-T")
      (fields (field (name "BOM_Supplier Part") "C163302"))
      (libsource (lib "") (part "ACS714LLCTR-50A-T"))
    )
    (comp (ref "U28")
      (value "ACS714LLCTR-50A-T")
      (fields (field (name "BOM_Supplier Part") "C163302"))
      (libsource (lib "") (part "ACS714LLCTR-50A-T"))
    )
    (comp (ref "U29")
      (value "LM2678SX-ADJ/NOPB")
      (fields (field (name "BOM_Supplier Part") "C40844"))
      (libsource (lib "") (part "LM2678SX-ADJ/NOPB"))
    )
    (comp (ref "U30")
      (value "NX3L4051PW,118")
      (fields (field (name "BOM_Supplier Part") "C2673441"))
      (libsource (lib "") (part "NX3L4051PW,118"))
    )
    (comp (ref "U31")
      (value "NX3L4051PW,118")
      (fields (field (name "BOM_Supplier Part") "C2673441"))
      (libsource (lib "") (part "NX3L4051PW,118"))
    )
    (comp (ref "U32")
      (value "NX3L4051PW,118")
      (fields (field (name "BOM_Supplier Part") "C2673441"))
      (libsource (lib "") (part "NX3L4051PW,118"))
    )
    (comp (ref "U33")
      (value "NX3L4051PW,118")
      (fields (field (name "BOM_Supplier Part") "C2673441"))
      (libsource (lib "") (part "NX3L4051PW,118"))
    )
    (comp (ref "U34")
      (value "NX3L4051PW,118")
      (fields (field (name "BOM_Supplier Part") "C2673441"))
      (libsource (lib "") (part "NX3L4051PW,118"))
    )
    (comp (ref "U35")
      (value "NX3L4051PW,118")
      (fields (field (name "BOM_Supplier Part") "C2673441"))
      (libsource (lib "") (part "NX3L4051PW,118"))
    )
    (comp (ref "U36")
      (value "NX3L4051PW,118")
      (fields (field (name "BOM_Supplier Part") "C2673441"))
      (libsource (lib "") (part "NX3L4051PW,118"))
    )
    (comp (ref "U37")
      (value "NX3L4051PW,118")
      (fields (field (name "BOM_Supplier Part") "C2673441"))
      (libsource (lib "") (part "NX3L4051PW,118"))
    )
    (comp (ref "U38")
      (value "NX3L4051PW,118")
      (fields (field (name "BOM_Supplier Part") "C2673441"))
      (libsource (lib "") (part "NX3L4051PW,118"))
    )
    (comp (ref "U39")
      (value "NX3L4051PW,118")
      (fields (field (name "BOM_Supplier Part") "C2673441"))
      (libsource (lib "") (part "NX3L4051PW,118"))
    )
    (comp (ref "U40")
      (value "NX3L4051PW,118")
      (fields (field (name "BOM_Supplier Part") "C2673441"))
      (libsource (lib "") (part "NX3L4051PW,118"))
    )
    (comp (ref "U41")
      (value "NX3L4051PW,118")
      (fields (field (name "BOM_Supplier Part") "C2673441"))
      (libsource (lib "") (part "NX3L4051PW,118"))
    )
    (comp (ref "U42")
      (value "NX3L4051PW,118")
      (fields (field (name "BOM_Supplier Part") "C2673441"))
      (libsource (lib "") (part "NX3L4051PW,118"))
    )
    (comp (ref "U43")
      (value "NX3L4051PW,118")
      (fields (field (name "BOM_Supplier Part") "C2673441"))
      (libsource (lib "") (part "NX3L4051PW,118"))
    )
    (comp (ref "U44")
      (value "TI INA229")
      (fields (field (name "BOM_Manufacturer Part") "INA229"))
      (libsource (lib "") (part "TI INA229"))
    )
    (comp (ref "U45")
      (value "AD8278ARZ-R7")
      (fields (field (name "BOM_Supplier Part") "C652635"))
      (libsource (lib "") (part "AD8278ARZ-R7"))
    )
    (comp (ref "U46")
      (value "ADG706BRUZ-REEL7")
      (fields (field (name "BOM_Supplier Part") "C408400"))
      (libsource (lib "") (part "ADG706BRUZ-REEL7"))
    )
    (comp (ref "U47") (value "ADG1406BCPZ-REEL7") (libsource (lib "") (part "ADG1406BCPZ-REEL7")))
    (comp (ref "U48") (value "ADG1406BCPZ-REEL7") (libsource (lib "") (part "ADG1406BCPZ-REEL7")))
    (comp (ref "U49")
      (value "AIC1117A-25GYTR")
      (fields (field (name "BOM_Supplier Part") "C238209"))
      (libsource (lib "") (part "AIC1117A-25GYTR"))
    )
    (comp (ref "U50")
      (value "ADG706BRUZ-REEL7")
      (fields (field (name "BOM_Supplier Part") "C408400"))
      (libsource (lib "") (part "ADG706BRUZ-REEL7"))
    )
    (comp (ref "U51") (value "ADG1406BCPZ-REEL7") (libsource (lib "") (part "ADG1406BCPZ-REEL7")))
    (comp (ref "U52")
      (value "MAX11100EUB+")
      (fields (field (name "BOM_Supplier Part") "C143329"))
      (libsource (lib "") (part "MAX11100EUB+"))
    )
    (comp (ref "U53") (value "DD1718PA") (libsource (lib "") (part "DD1718PA")))
    (comp (ref "U54")
      (value "0435002.KR")
      (fields (field (name "BOM_Supplier Part") "C206948"))
      (libsource (lib "") (part "0435002.KR"))
    )
    (comp (ref "U55")
      (value "NLAS4157DFT2G")
      (fields (field (name "BOM_Supplier Part") "C106912"))
      (libsource (lib "") (part "NLAS4157DFT2G"))
    )
    (comp (ref "U56")
      (value "NLAS4157DFT2G")
      (fields (field (name "BOM_Supplier Part") "C106912"))
      (libsource (lib "") (part "NLAS4157DFT2G"))
    )
    (comp (ref "U57")
      (value "NLAS4157DFT2G")
      (fields (field (name "BOM_Supplier Part") "C106912"))
      (libsource (lib "") (part "NLAS4157DFT2G"))
    )
  )
  (nets
    (net (code "1") (name "+5VA") (class "Default")
      (node (ref "C1") (pin "1") (pinfunction "1_1") (pintype "unspecified"))
      (node (ref "C3") (pin "1") (pinfunction "1_1") (pintype "unspecified"))
      (node (ref "C35") (pin "1") (pinfunction "1_1") (pintype "unspecified"))
      (node (ref "C36") (pin "1") (pinfunction "1_1") (pintype "unspecified"))
      (node (ref "C4") (pin "1") (pinfunction "1_1") (pintype "input"))
      (node (ref "C43") (pin "2") (pinfunction "2_2") (pintype "input"))
      (node (ref "C45") (pin "1") (pinfunction "1_1") (pintype "input"))
      (node (ref "C46") (pin "2") (pinfunction "2_2") (pintype "unspecified"))
      (node (ref "C5") (pin "1") (pinfunction "1_1") (pintype "input"))
      (node (ref "C52") (pin "1") (pinfunction "1_1") (pintype "unspecified"))
      (node (ref "C58") (pin "1") (pinfunction "1_1") (pintype "unspecified"))
      (node (ref "C60") (pin "1") (pinfunction "1_1") (pintype "unspecified"))
      (node (ref "C61") (pin "1") (pinfunction "1_1") (pintype "unspecified"))
      (node (ref "C62") (pin "1") (pinfunction "1_1") (pintype "unspecified"))
      (node (ref "C66") (pin "2") (pinfunction "2_2") (pintype "unspecified"))
      (node (ref "C67") (pin "2") (pinfunction "2_2") (pintype "unspecified"))
      (node (ref "C70") (pin "2") (pinfunction "2_2") (pintype "unspecified"))
      (node (ref "C73") (pin "1") (pinfunction "1_1") (pintype "unspecified"))
      (node (ref "C74") (pin "2") (pinfunction "2_2") (pintype "unspecified"))
      (node (ref "D13") (pin "2") (pinfunction "A_2") (pintype "unspecified"))
      (node (ref "D14") (pin "2") (pinfunction "A_2") (pintype "unspecified"))
      (node (ref "D15") (pin "2") (pinfunction "A_2") (pintype "unspecified"))
      (node (ref "L1") (pin "2") (pinfunction "2_2") (pintype "unspecified"))
      (node (ref "L2") (pin "1") (pinfunction "1_1") (pintype "unspecified"))
      (node (ref "R10") (pin "2") (pinfunction "2_2") (pintype "unspecified"))
      (node (ref "R33") (pin "1") (pinfunction "1_1") (pintype "unspecified"))
      (node (ref "R5") (pin "2") (pinfunction "2_2") (pintype "unspecified"))
      (node (ref "R7") (pin "2") (pinfunction "2_2") (pintype "unspecified"))
      (node (ref "R9") (pin "2") (pinfunction "2_2") (pintype "unspecified"))
      (node (ref "U2") (pin "1") (pinfunction "VCC_1") (pintype "passive"))
      (node (ref "U29") (pin "6") (pinfunction "FB_6") (pintype "unspecified"))
      (node (ref "U29") (pin "7") (pinfunction "ON/OFF#_7") (pintype "unspecified"))
      (node (ref "U3") (pin "4") (pinfunction "VCC_4") (pintype "unspecified"))
      (node (ref "U49") (pin "3") (pinfunction "VIN_3") (pintype "unspecified"))
      (node (ref "U52") (pin "7") (pinfunction "AVDD_7") (pintype "passive"))
      (node (ref "U55") (pin "1") (pinfunction "B1_1") (pintype "unspecified"))
      (node (ref "U55") (pin "5") (pinfunction "VCC_5") (pintype "unspecified"))
      (node (ref "U56") (pin "1") (pinfunction "B1_1") (pintype "unspecified"))
      (node (ref "U56") (pin "5") (pinfunction "VCC_5") (pintype "unspecified"))
      (node (ref "U57") (pin "1") (pinfunction "B1_1") (pintype "unspecified"))
      (node (ref "U57") (pin "5") (pinfunction "VCC_5") (pintype "unspecified"))
      (node (ref "U6") (pin "1") (pinfunction "+VCC_1") (pintype "passive"))
      (node (ref "U6") (pin "9") (pinfunction "+VCC_9") (pintype "passive"))
      (node (ref "U9") (pin "31") (pinfunction "P31_31") (pintype "unspecified"))
    )
    (net (code "2") (name "-5VA") (class "Default")
      (node (ref "C49") (pin "2") (pinfunction "2_2") (pintype "unspecified"))
      (node (ref "C50") (pin "2") (pinfunction "2_2") (pintype "unspecified"))
      (node (ref "C51") (pin "2") (pinfunction "2_2") (pintype "unspecified"))
      (node (ref "C55") (pin "2") (pinfunction "2_2") (pintype "unspecified"))
      (node (ref "D10") (pin "1") (pinfunction "K_1") (pintype "unspecified"))
      (node (ref "D11") (pin "1") (pinfunction "K_1") (pintype "unspecified"))
      (node (ref "D12") (pin "1") (pinfunction "K_1") (pintype "unspecified"))
    )
    (net (code "3") (name "/+3.3V") (class "Default")
      (node (ref "C10") (pin "2") (pinfunction "2_2") (pintype "unspecified"))
      (node (ref "C11") (pin "2") (pinfunction "2_2") (pintype "unspecified"))
      (node (ref "C12") (pin "2") (pinfunction "2_2") (pintype "unspecified"))
      (node (ref "C13") (pin "1") (pinfunction "1_1") (pintype "unspecified"))
      (node (ref "C14") (pin "1") (pinfunction "1_1") (pintype "unspecified"))
      (node (ref "C15") (pin "1") (pinfunction "1_1") (pintype "unspecified"))
      (node (ref "C19") (pin "2") (pinfunction "2_2") (pintype "input"))
      (node (ref "C20") (pin "2") (pinfunction "2_2") (pintype "input"))
      (node (ref "C21") (pin "2") (pinfunction "2_2") (pintype "input"))
      (node (ref "C53") (pin "1") (pinfunction "1_1") (pintype "unspecified"))
      (node (ref "U10") (pin "24") (pinfunction "VDD_24") (pintype "unspecified"))
      (node (ref "U10") (pin "36") (pinfunction "VDD_36") (pintype "unspecified"))
      (node (ref "U10") (pin "48") (pinfunction "VDD_48") (pintype "unspecified"))
      (node (ref "U10") (pin "9") (pinfunction "VDDA/VREF+_9") (pintype "unspecified"))
      (node (ref "U49") (pin "2") (pinfunction "VOUT_2") (pintype "unspecified"))
      (node (ref "U49") (pin "4") (pinfunction "VOUT_4") (pintype "unspecified"))
    )
    (net (code "4") (name "/+3.3v") (class "Default")
      (node (ref "C2") (pin "1") (pinfunction "1_1") (pintype "unspecified"))
      (node (ref "U2") (pin "8") (pinfunction "LED_8") (pintype "unspecified"))
    )
    (net (code "5") (name "/+5VA_1") (class "Default")
      (node (ref "C38") (pin "1") (pinfunction "1_1") (pintype "unspecified"))
      (node (ref "C41") (pin "2") (pinfunction "2_2") (pintype "unspecified"))
      (node (ref "U30") (pin "16") (pinfunction "VCC_16") (pintype "unspecified"))
    )
    (net (code "6") (name "/+5VA_2") (class "Default")
      (node (ref "U37") (pin "16") (pinfunction "VCC_16") (pintype "unspecified"))
    )
    (net (code "7") (name "/+5VA_3") (class "Default")
      (node (ref "U31") (pin "16") (pinfunction "VCC_16") (pintype "unspecified"))
    )
    (net (code "8") (name "/+5VA_4") (class "Default")
      (node (ref "U38") (pin "16") (pinfunction "VCC_16") (pintype "unspecified"))
    )
    (net (code "9") (name "/+5VA_5") (class "Default")
      (node (ref "U32") (pin "16") (pinfunction "VCC_16") (pintype "unspecified"))
    )
    (net (code "10") (name "/+5VA_6") (class "Default")
      (node (ref "U39") (pin "16") (pinfunction "VCC_16") (pintype "unspecified"))
    )
    (net (code "11") (name "/+5VA_7") (class "Default")
      (node (ref "U33") (pin "16") (pinfunction "VCC_16") (pintype "unspecified"))
    )
    (net (code "12") (name "/+5VA_8") (class "Default")
      (node (ref "U40") (pin "16") (pinfunction "VCC_16") (pintype "unspecified"))
    )
    (net (code "13") (name "/+5VA_9") (class "Default")
      (node (ref "U34") (pin "16") (pinfunction "VCC_16") (pintype "unspecified"))
    )
    (net (code "14") (name "/+5VA_10") (class "Default")
      (node (ref "U41") (pin "16") (pinfunction "VCC_16") (pintype "unspecified"))
    )
    (net (code "15") (name "/+5VA_11") (class "Default")
      (node (ref "U35") (pin "16") (pinfunction "VCC_16") (pintype "unspecified"))
    )
    (net (code "16") (name "/+5VA_12") (class "Default")
      (node (ref "U42") (pin "16") (pinfunction "VCC_16") (pintype "unspecified"))
    )
    (net (code "17") (name "/+5VA_13") (class "Default")
      (node (ref "U36") (pin "16") (pinfunction "VCC_16") (pintype "unspecified"))
    )
    (net (code "18") (name "/+5VA_14") (class "Default")
      (node (ref "C39") (pin "1") (pinfunction "1_1") (pintype "unspecified"))
      (node (ref "C42") (pin "2") (pinfunction "2_2") (pintype "unspecified"))
      (node (ref "U43") (pin "16") (pinfunction "VCC_16") (pintype "unspecified"))
    )
    (net (code "19") (name "/+5VA_15") (class "Default")
      (node (ref "U46") (pin "1") (pinfunction "VDD_1") (pintype "unspecified"))
    )
    (net (code "20") (name "/+5VA_16") (class "Default")
      (node (ref "U50") (pin "1") (pinfunction "VDD_1") (pintype "unspecified"))
    )
    (net (code "21") (name "/+5VA_17") (class "Default")
      (node (ref "D13") (pin "1") (pinfunction "K_1") (pintype "unspecified"))
      (node (ref "U47") (pin "31") (pinfunction "VDD_31") (pintype "passive"))
    )
    (net (code "22") (name "/+5VA_18") (class "Default")
      (node (ref "D14") (pin "1") (pinfunction "K_1") (pintype "unspecified"))
      (node (ref "U48") (pin "31") (pinfunction "VDD_31") (pintype "passive"))
    )
    (net (code "23") (name "/+5VA_19") (class "Default")
      (node (ref "D15") (pin "1") (pinfunction "K_1") (pintype "unspecified"))
      (node (ref "U51") (pin "31") (pinfunction "VDD_31") (pintype "passive"))
    )
    (net (code "24") (name "/+5VD") (class "Default")
      (node (ref "C54") (pin "1") (pinfunction "1_1") (pintype "input"))
      (node (ref "C59") (pin "2") (pinfunction "2_2") (pintype "unspecified"))
      (node (ref "L2") (pin "2") (pinfunction "2_2") (pintype "unspecified"))
      (node (ref "U52") (pin "3") (pinfunction "DVDD_3") (pintype "passive"))
      (node (ref "U6") (pin "8") (pinfunction "VREF_8") (pintype "unspecified"))
    )
    (net (code "25") (name "/+5v") (class "Default")
      (node (ref "C64") (pin "2") (pinfunction "2_2") (pintype "unspecified"))
      (node (ref "U11") (pin "20") (pinfunction "VCC_20") (pintype "unspecified"))
      (node (ref "U12") (pin "20") (pinfunction "VCC_20") (pintype "unspecified"))
      (node (ref "U8") (pin "10") (pinfunction "MR#_10") (pintype "unspecified"))
      (node (ref "U8") (pin "16") (pinfunction "VCC_16") (pintype "unspecified"))
    )
    (net (code "26") (name "/+5v_digital") (class "Default")
      (node (ref "U11") (pin "14") (pinfunction "REF+_14") (pintype "unspecified"))
      (node (ref "U12") (pin "14") (pinfunction "REF+_14") (pintype "unspecified"))
    )
    (net (code "27") (name "/+p1 battery") (class "Default")
      (node (ref "D3") (pin "1") (pinfunction "K_1") (pintype "unspecified"))
      (node (ref "Q1") (pin "2") (pinfunction "S_2") (pintype "unspecified"))
      (node (ref "U14") (pin "+") (pinfunction "5_+") (pintype "unspecified"))
    )
    (net (code "28") (name "/+p18 battery") (class "Default")
      (node (ref "D4") (pin "1") (pinfunction "K_1") (pintype "unspecified"))
      (node (ref "Q2") (pin "2") (pinfunction "S_2") (pintype "unspecified"))
      (node (ref "U21") (pin "+") (pinfunction "5_+") (pintype "unspecified"))
    )
    (net (code "29") (name "/-5VA_17") (class "Default")
      (node (ref "D10") (pin "2") (pinfunction "A_2") (pintype "unspecified"))
      (node (ref "U47") (pin "25") (pinfunction "VSS_25") (pintype "passive"))
    )
    (net (code "30") (name "/-5VA_18") (class "Default")
      (node (ref "D11") (pin "2") (pinfunction "A_2") (pintype "unspecified"))
      (node (ref "U48") (pin "25") (pinfunction "VSS_25") (pintype "passive"))
    )
    (net (code "31") (name "/-5VA_19") (class "Default")
      (node (ref "D12") (pin "2") (pinfunction "A_2") (pintype "unspecified"))
      (node (ref "U51") (pin "25") (pinfunction "VSS_25") (pintype "passive"))
    )
    (net (code "32") (name "/-5v") (class "Default")
      (node (ref "C65") (pin "1") (pinfunction "1_1") (pintype "unspecified"))
    )
    (net (code "33") (name "/-bat_sw") (class "Default")
      (node (ref "D19") (pin "2") (pinfunction "A_2") (pintype "unspecified"))
      (node (ref "D20") (pin "2") (pinfunction "A_2") (pintype "unspecified"))
      (node (ref "Q5") (pin "4") (pinfunction "S_4") (pintype "unspecified"))
      (node (ref "Q6") (pin "4") (pinfunction "S_4") (pintype "unspecified"))
      (node (ref "R46") (pin "1") (pinfunction "1_1") (pintype "unspecified"))
      (node (ref "R47") (pin "1") (pinfunction "1_1") (pintype "unspecified"))
    )
    (net (code "34") (name "/AB") (class "Default")
      (node (ref "D20") (pin "1") (pinfunction "K_1") (pintype "unspecified"))
      (node (ref "Q6") (pin "1") (pinfunction "D_1") (pintype "unspecified"))
      (node (ref "Q6") (pin "2") (pinfunction "D_2") (pintype "unspecified"))
      (node (ref "Q6") (pin "5") (pinfunction "D_5") (pintype "unspecified"))
      (node (ref "Q6") (pin "6") (pinfunction "D_6") (pintype "unspecified"))
    )
    (net (code "35") (name "/AB_E") (class "Default")
      (node (ref "D17") (pin "1") (pinfunction "K_1") (pintype "unspecified"))
      (node (ref "R45") (pin "2") (pinfunction "2_2") (pintype "unspecified"))
      (node (ref "U9") (pin "24") (pinfunction "P27_24") (pintype "unspecified"))
    )
    (net (code "36") (name "/A_INA") (class "Default")
      (node (ref "R33") (pin "2") (pinfunction "2_2") (pintype "unspecified"))
      (node (ref "U44") (pin "3") (pinfunction "ALERT_3") (pintype "unspecified"))
    )
    (net (code "37") (name "/Boot_mk") (class "Default")
      (node (ref "U10") (pin "44") (pinfunction "BOOT0_44") (pintype "unspecified"))
    )
    (net (code "38") (name "/Bt_mk") (class "Default")
      (node (ref "BT1") (pin "1") (pinfunction "+_1") (pintype "passive"))
      (node (ref "U10") (pin "1") (pinfunction "VBAT_1") (pintype "unspecified"))
    )
    (net (code "39") (name "/CLK_enc") (class "Default")
      (node (ref "U3") (pin "1") (pinfunction "CLK_1") (pintype "unspecified"))
      (node (ref "U9") (pin "16") (pinfunction "P19_16") (pintype "unspecified"))
    )
    (net (code "40") (name "/CM_F_1") (class "Default")
      (node (ref "C28") (pin "1") (pinfunction "1_1") (pintype "unspecified"))
      (node (ref "C30") (pin "1") (pinfunction "1_1") (pintype "unspecified"))
      (node (ref "U27") (pin "6") (pinfunction "FILTER_6") (pintype "unspecified"))
      (node (ref "U28") (pin "6") (pinfunction "FILTER_6") (pintype "unspecified"))
    )
    (net (code "41") (name "/CSK") (class "Default")
      (node (ref "U11") (pin "15") (pinfunction "CS#_15") (pintype "unspecified"))
      (node (ref "U12") (pin "15") (pinfunction "CS#_15") (pintype "unspecified"))
    )
    (net (code "42") (name "/Circ_1_in") (class "Default")
      (node (ref "U27") (pin "1") (pinfunction "IP+_1") (pintype "unspecified"))
      (node (ref "U27") (pin "2") (pinfunction "IP+_2") (pintype "unspecified"))
      (node (ref "U28") (pin "1") (pinfunction "IP+_1") (pintype "unspecified"))
      (node (ref "U28") (pin "2") (pinfunction "IP+_2") (pintype "unspecified"))
    )
    (net (code "43") (name "/Circ_1_out") (class "Default")
      (node (ref "U27") (pin "3") (pinfunction "IP-_3") (pintype "unspecified"))
      (node (ref "U27") (pin "4") (pinfunction "IP-_4") (pintype "unspecified"))
      (node (ref "U28") (pin "3") (pinfunction "IP-_3") (pintype "unspecified"))
      (node (ref "U28") (pin "4") (pinfunction "IP-_4") (pintype "unspecified"))
    )
    (net (code "44") (name "/Circ_1_to_ADC") (class "Default")
      (node (ref "U12") (pin "1") (pinfunction "AIN0_1") (pintype "unspecified"))
      (node (ref "U27") (pin "7") (pinfunction "VIOUT_7") (pintype "unspecified"))
      (node (ref "U28") (pin "7") (pinfunction "VIOUT_7") (pintype "unspecified"))
    )
    (net (code "45") (name "/Circ_2_to_ADC") (class "Default")
      (node (ref "U12") (pin "2") (pinfunction "AIN1_2") (pintype "unspecified"))
    )
    (net (code "46") (name "/Circ_3_to_ADC") (class "Default")
      (node (ref "U12") (pin "3") (pinfunction "AIN2_3") (pintype "unspecified"))
    )
    (net (code "47") (name "/Circ_4_to_ADC") (class "Default")
      (node (ref "U12") (pin "4") (pinfunction "AIN3_4") (pintype "unspecified"))
    )
    (net (code "48") (name "/Circ_5_to_ADC") (class "Default")
      (node (ref "U12") (pin "5") (pinfunction "AIN4_5") (pintype "unspecified"))
    )
    (net (code "49") (name "/Circ_6_to_ADC") (class "Default")
      (node (ref "U12") (pin "6") (pinfunction "AIN5_6") (pintype "unspecified"))
    )
    (net (code "50") (name "/Circ_7_to_ADC") (class "Default")
      (node (ref "U12") (pin "7") (pinfunction "AIN6_7") (pintype "unspecified"))
    )
    (net (code "51") (name "/Circ_8_to_ADC") (class "Default")
      (node (ref "U12") (pin "8") (pinfunction "AIN7_8") (pintype "unspecified"))
    )
    (net (code "52") (name "/Circ_9_to_ADC") (class "Default")
      (node (ref "U12") (pin "9") (pinfunction "AIN8_9") (pintype "unspecified"))
    )
    (net (code "53") (name "/Circ_10_to_ADC") (class "Default")
      (node (ref "U12") (pin "11") (pinfunction "AIN9_11") (pintype "unspecified"))
    )
    (net (code "54") (name "/Circ_11_to_ADC") (class "Default")
      (node (ref "U12") (pin "12") (pinfunction "AIN10_12") (pintype "unspecified"))
    )
    (net (code "55") (name "/Circ_12_to_ADC") (class "Default")
      (node (ref "U11") (pin "1") (pinfunction "AIN0_1") (pintype "unspecified"))
    )
    (net (code "56") (name "/Circ_13_to_ADC") (class "Default")
      (node (ref "U11") (pin "2") (pinfunction "AIN1_2") (pintype "unspecified"))
    )
    (net (code "57") (name "/Circ_14_to_ADC") (class "Default")
      (node (ref "U11") (pin "3") (pinfunction "AIN2_3") (pintype "unspecified"))
    )
    (net (code "58") (name "/Circ_15_to_ADC") (class "Default")
      (node (ref "U11") (pin "4") (pinfunction "AIN3_4") (pintype "unspecified"))
    )
    (net (code "59") (name "/Circ_16_to_ADC") (class "Default")
      (node (ref "U11") (pin "5") (pinfunction "AIN4_5") (pintype "unspecified"))
    )
    (net (code "60") (name "/Circ_17_to_ADC") (class "Default")
      (node (ref "U11") (pin "6") (pinfunction "AIN5_6") (pintype "unspecified"))
    )
    (net (code "61") (name "/Circ_18_to_ADC") (class "Default")
      (node (ref "U11") (pin "7") (pinfunction "AIN6_7") (pintype "unspecified"))
    )
    (net (code "62") (name "/DSP_DC") (class "Default")
      (node (ref "R3") (pin "1") (pinfunction "1_1") (pintype "input"))
      (node (ref "U2") (pin "5") (pinfunction "DC_5") (pintype "unspecified"))
      (node (ref "U9") (pin "14") (pinfunction "P17_14") (pintype "unspecified"))
    )
    (net (code "63") (name "/DSP_DC_R") (class "Default")
      (node (ref "R3") (pin "2") (pinfunction "2_2") (pintype "input"))
    )
    (net (code "64") (name "/DSP_RST") (class "Default")
      (node (ref "R2") (pin "1") (pinfunction "1_1") (pintype "input"))
      (node (ref "U2") (pin "4") (pinfunction "RST_4") (pintype "unspecified"))
      (node (ref "U9") (pin "13") (pinfunction "P16_13") (pintype "unspecified"))
    )
    (net (code "65") (name "/DSP_RST_R") (class "Default")
      (node (ref "R2") (pin "2") (pinfunction "2_2") (pintype "input"))
    )
    (net (code "66") (name "/DT_enc") (class "Default")
      (node (ref "U3") (pin "2") (pinfunction "DT_2") (pintype "unspecified"))
      (node (ref "U9") (pin "17") (pinfunction "P20_17") (pintype "unspecified"))
    )
    (net (code "67") (name "/E_RG#") (class "Default")
      (node (ref "R4") (pin "1") (pinfunction "1_1") (pintype "input"))
      (node (ref "U8") (pin "13") (pinfunction "OE#_13") (pintype "unspecified"))
    )
    (net (code "68") (name "/Ens8_1") (class "Default")
      (node (ref "R37") (pin "1") (pinfunction "1_1") (pintype "unspecified"))
      (node (ref "U30") (pin "6") (pinfunction "E#_6") (pintype "unspecified"))
    )
    (net (code "69") (name "/Ens8_1_R") (class "Default")
      (node (ref "R37") (pin "2") (pinfunction "2_2") (pintype "unspecified"))
      (node (ref "U5") (pin "15") (pinfunction "P18_15") (pintype "unspecified"))
    )
    (net (code "70") (name "/Ens8_2") (class "Default")
      (node (ref "U37") (pin "6") (pinfunction "E#_6") (pintype "unspecified"))
    )
    (net (code "71") (name "/Ens8_2_R") (class "Default")
      (node (ref "U5") (pin "16") (pinfunction "P19_16") (pintype "unspecified"))
    )
    (net (code "72") (name "/Ens8_3") (class "Default")
      (node (ref "U31") (pin "6") (pinfunction "E#_6") (pintype "unspecified"))
    )
    (net (code "73") (name "/Ens8_3_R") (class "Default")
      (node (ref "U5") (pin "17") (pinfunction "P20_17") (pintype "unspecified"))
    )
    (net (code "74") (name "/Ens8_4") (class "Default")
      (node (ref "U38") (pin "6") (pinfunction "E#_6") (pintype "unspecified"))
    )
    (net (code "75") (name "/Ens8_4_R") (class "Default")
      (node (ref "U5") (pin "18") (pinfunction "P21_18") (pintype "unspecified"))
    )
    (net (code "76") (name "/Ens8_5") (class "Default")
      (node (ref "U32") (pin "6") (pinfunction "E#_6") (pintype "unspecified"))
    )
    (net (code "77") (name "/Ens8_5_R") (class "Default")
      (node (ref "U5") (pin "19") (pinfunction "P22_19") (pintype "unspecified"))
    )
    (net (code "78") (name "/Ens8_6") (class "Default")
      (node (ref "U39") (pin "6") (pinfunction "E#_6") (pintype "unspecified"))
    )
    (net (code "79") (name "/Ens8_6_R") (class "Default")
      (node (ref "U5") (pin "20") (pinfunction "P23_20") (pintype "unspecified"))
    )
    (net (code "80") (name "/Ens8_7") (class "Default")
      (node (ref "U33") (pin "6") (pinfunction "E#_6") (pintype "unspecified"))
    )
    (net (code "81") (name "/Ens8_7_R") (class "Default")
      (node (ref "U5") (pin "21") (pinfunction "P24_21") (pintype "unspecified"))
    )
    (net (code "82") (name "/Ens8_8") (class "Default")
      (node (ref "U40") (pin "6") (pinfunction "E#_6") (pintype "unspecified"))
    )
    (net (code "83") (name "/Ens8_8_R") (class "Default")
      (node (ref "U5") (pin "22") (pinfunction "P25_22") (pintype "unspecified"))
    )
    (net (code "84") (name "/Ens8_9") (class "Default")
      (node (ref "U34") (pin "6") (pinfunction "E#_6") (pintype "unspecified"))
    )
    (net (code "85") (name "/Ens8_9_R") (class "Default")
      (node (ref "U5") (pin "23") (pinfunction "P26_23") (pintype "unspecified"))
    )
    (net (code "86") (name "/Ens8_10") (class "Default")
      (node (ref "U41") (pin "6") (pinfunction "E#_6") (pintype "unspecified"))
    )
    (net (code "87") (name "/Ens8_10_R") (class "Default")
      (node (ref "U5") (pin "24") (pinfunction "P27_24") (pintype "unspecified"))
    )
    (net (code "88") (name "/Ens8_11") (class "Default")
      (node (ref "U35") (pin "6") (pinfunction "E#_6") (pintype "unspecified"))
    )
    (net (code "89") (name "/Ens8_11_R") (class "Default")
      (node (ref "U5") (pin "25") (pinfunction "P28_25") (pintype "unspecified"))
    )
    (net (code "90") (name "/Ens8_12") (class "Default")
      (node (ref "U42") (pin "6") (pinfunction "E#_6") (pintype "unspecified"))
    )
    (net (code "91") (name "/Ens8_12_R") (class "Default")
      (node (ref "U5") (pin "27") (pinfunction "P29_27") (pintype "unspecified"))
    )
    (net (code "92") (name "/Ens8_13") (class "Default")
      (node (ref "U36") (pin "6") (pinfunction "E#_6") (pintype "unspecified"))
    )
    (net (code "93") (name "/Ens8_13_R") (class "Default")
      (node (ref "U5") (pin "29") (pinfunction "P30_29") (pintype "unspecified"))
    )
    (net (code "94") (name "/Ens8_14") (class "Default")
      (node (ref "R38") (pin "1") (pinfunction "1_1") (pintype "unspecified"))
      (node (ref "U43") (pin "6") (pinfunction "E#_6") (pintype "unspecified"))
      (node (ref "U5") (pin "31") (pinfunction "P31_31") (pintype "unspecified"))
    )
    (net (code "95") (name "/Ens8_14_R") (class "Default")
      (node (ref "R38") (pin "2") (pinfunction "2_2") (pintype "unspecified"))
    )
    (net (code "96") (name "/Ens16_B+") (class "Default")
      (node (ref "U47") (pin "16") (pinfunction "EN_16") (pintype "unspecified"))
    )
    (net (code "97") (name "/Ens16_B-") (class "Default")
      (node (ref "R43") (pin "1") (pinfunction "1_1") (pintype "unspecified"))
      (node (ref "U48") (pin "16") (pinfunction "EN_16") (pintype "unspecified"))
    )
    (net (code "98") (name "/Ens16_B-_R") (class "Default")
      (node (ref "R43") (pin "2") (pinfunction "2_2") (pintype "unspecified"))
    )
    (net (code "99") (name "/Ens16_B_R") (class "Default")
      (node (ref "U4") (pin "22") (pinfunction "P25_22") (pintype "unspecified"))
    )
    (net (code "100") (name "/Ens16_B{slash}") (class "Default")
      (node (ref "U51") (pin "16") (pinfunction "EN_16") (pintype "unspecified"))
    )
    (net (code "101") (name "/Ens16_V+") (class "Default")
      (node (ref "R42") (pin "1") (pinfunction "1_1") (pintype "unspecified"))
      (node (ref "U46") (pin "18") (pinfunction "EN_18") (pintype "unspecified"))
    )
    (net (code "102") (name "/Ens16_V+_R") (class "Default")
      (node (ref "R42") (pin "2") (pinfunction "2_2") (pintype "unspecified"))
    )
    (net (code "103") (name "/Ens16_V-") (class "Default")
      (node (ref "U50") (pin "18") (pinfunction "EN_18") (pintype "unspecified"))
    )
    (net (code "104") (name "/Ens16_V_R") (class "Default")
      (node (ref "U4") (pin "21") (pinfunction "P24_21") (pintype "unspecified"))
    )
    (net (code "105") (name "/Gnd") (class "Default")
      (node (ref "U11") (pin "10") (pinfunction "GND_10") (pintype "unspecified"))
      (node (ref "U11") (pin "13") (pinfunction "REF-_13") (pintype "unspecified"))
      (node (ref "U11") (pin "8") (pinfunction "AIN7_8") (pintype "unspecified"))
      (node (ref "U11") (pin "9") (pinfunction "AIN8_9") (pintype "unspecified"))
      (node (ref "U12") (pin "10") (pinfunction "GND_10") (pintype "unspecified"))
      (node (ref "U12") (pin "13") (pinfunction "REF-_13") (pintype "unspecified"))
    )
    (net (code "106") (name "/InS1_1") (class "Default")
      (node (ref "U30") (pin "11") (pinfunction "S1_11") (pintype "unspecified"))
      (node (ref "U7") (pin "32") (pinfunction "P4_32") (pintype "unspecified"))
    )
    (net (code "107") (name "/InS1_2") (class "Default")
      (node (ref "U30") (pin "10") (pinfunction "S2_10") (pintype "unspecified"))
      (node (ref "U7") (pin "30") (pinfunction "P5_30") (pintype "unspecified"))
    )
    (net (code "108") (name "/InS1_3") (class "Default")
      (node (ref "U30") (pin "9") (pinfunction "S3_9") (pintype "unspecified"))
      (node (ref "U7") (pin "28") (pinfunction "P6_28") (pintype "unspecified"))
    )
    (net (code "109") (name "/InS2_1") (class "Default")
      (node (ref "U37") (pin "11") (pinfunction "S1_11") (pintype "unspecified"))
      (node (ref "U7") (pin "26") (pinfunction "P7_26") (pintype "unspecified"))
    )
    (net (code "110") (name "/InS2_2") (class "Default")
      (node (ref "U37") (pin "10") (pinfunction "S2_10") (pintype "unspecified"))
      (node (ref "U7") (pin "5") (pinfunction "P8_5") (pintype "unspecified"))
    )
    (net (code "111") (name "/InS2_3") (class "Default")
      (node (ref "U37") (pin "9") (pinfunction "S3_9") (pintype "unspecified"))
      (node (ref "U7") (pin "7") (pinfunction "P9_7") (pintype "unspecified"))
    )
    (net (code "112") (name "/InS3_1") (class "Default")
      (node (ref "U31") (pin "11") (pinfunction "S1_11") (pintype "unspecified"))
      (node (ref "U7") (pin "9") (pinfunction "P10_9") (pintype "unspecified"))
    )
    (net (code "113") (name "/InS3_2") (class "Default")
      (node (ref "U31") (pin "10") (pinfunction "S2_10") (pintype "unspecified"))
      (node (ref "U7") (pin "11") (pinfunction "P11_11") (pintype "unspecified"))
    )
    (net (code "114") (name "/InS3_3") (class "Default")
      (node (ref "U31") (pin "9") (pinfunction "S3_9") (pintype "unspecified"))
      (node (ref "U7") (pin "6") (pinfunction "P12_6") (pintype "unspecified"))
    )
    (net (code "115") (name "/InS4_1") (class "Default")
      (node (ref "U38") (pin "11") (pinfunction "S1_11") (pintype "unspecified"))
      (node (ref "U7") (pin "8") (pinfunction "P13_8") (pintype "unspecified"))
    )
    (net (code "116") (name "/InS4_2") (class "Default")
      (node (ref "U38") (pin "10") (pinfunction "S2_10") (pintype "unspecified"))
      (node (ref "U7") (pin "10") (pinfunction "P14_10") (pintype "unspecified"))
    )
    (net (code "117") (name "/InS4_3") (class "Default")
      (node (ref "U38") (pin "9") (pinfunction "S3_9") (pintype "unspecified"))
      (node (ref "U7") (pin "12") (pinfunction "P15_12") (pintype "unspecified"))
    )
    (net (code "118") (name "/InS5_1") (class "Default")
      (node (ref "U32") (pin "11") (pinfunction "S1_11") (pintype "unspecified"))
      (node (ref "U7") (pin "13") (pinfunction "P16_13") (pintype "unspecified"))
    )
    (net (code "119") (name "/InS5_2") (class "Default")
      (node (ref "U32") (pin "10") (pinfunction "S2_10") (pintype "unspecified"))
      (node (ref "U7") (pin "14") (pinfunction "P17_14") (pintype "unspecified"))
    )
    (net (code "120") (name "/InS5_3") (class "Default")
      (node (ref "U32") (pin "9") (pinfunction "S3_9") (pintype "unspecified"))
      (node (ref "U7") (pin "15") (pinfunction "P18_15") (pintype "unspecified"))
    )
    (net (code "121") (name "/InS6_1") (class "Default")
      (node (ref "U39") (pin "11") (pinfunction "S1_11") (pintype "unspecified"))
      (node (ref "U7") (pin "16") (pinfunction "P19_16") (pintype "unspecified"))
    )
    (net (code "122") (name "/InS6_2") (class "Default")
      (node (ref "U39") (pin "10") (pinfunction "S2_10") (pintype "unspecified"))
      (node (ref "U7") (pin "17") (pinfunction "P20_17") (pintype "unspecified"))
    )
    (net (code "123") (name "/InS6_3") (class "Default")
      (node (ref "U39") (pin "9") (pinfunction "S3_9") (pintype "unspecified"))
      (node (ref "U7") (pin "18") (pinfunction "P21_18") (pintype "unspecified"))
    )
    (net (code "124") (name "/InS7_1") (class "Default")
      (node (ref "U33") (pin "11") (pinfunction "S1_11") (pintype "unspecified"))
      (node (ref "U7") (pin "19") (pinfunction "P22_19") (pintype "unspecified"))
    )
    (net (code "125") (name "/InS7_2") (class "Default")
      (node (ref "U33") (pin "10") (pinfunction "S2_10") (pintype "unspecified"))
      (node (ref "U7") (pin "20") (pinfunction "P23_20") (pintype "unspecified"))
    )
    (net (code "126") (name "/InS7_3") (class "Default")
      (node (ref "U33") (pin "9") (pinfunction "S3_9") (pintype "unspecified"))
      (node (ref "U7") (pin "21") (pinfunction "P24_21") (pintype "unspecified"))
    )
    (net (code "127") (name "/InS8_1") (class "Default")
      (node (ref "U40") (pin "11") (pinfunction "S1_11") (pintype "unspecified"))
      (node (ref "U7") (pin "22") (pinfunction "P25_22") (pintype "unspecified"))
    )
    (net (code "128") (name "/InS8_2") (class "Default")
      (node (ref "U40") (pin "10") (pinfunction "S2_10") (pintype "unspecified"))
      (node (ref "U7") (pin "23") (pinfunction "P26_23") (pintype "unspecified"))
    )
    (net (code "129") (name "/InS8_3") (class "Default")
      (node (ref "U40") (pin "9") (pinfunction "S3_9") (pintype "unspecified"))
      (node (ref "U7") (pin "24") (pinfunction "P27_24") (pintype "unspecified"))
    )
    (net (code "130") (name "/InS9_1") (class "Default")
      (node (ref "U34") (pin "11") (pinfunction "S1_11") (pintype "unspecified"))
      (node (ref "U7") (pin "25") (pinfunction "P28_25") (pintype "unspecified"))
    )
    (net (code "131") (name "/InS9_2") (class "Default")
      (node (ref "U34") (pin "10") (pinfunction "S2_10") (pintype "unspecified"))
      (node (ref "U7") (pin "27") (pinfunction "P29_27") (pintype "unspecified"))
    )
    (net (code "132") (name "/InS9_3") (class "Default")
      (node (ref "U34") (pin "9") (pinfunction "S3_9") (pintype "unspecified"))
      (node (ref "U7") (pin "29") (pinfunction "P30_29") (pintype "unspecified"))
    )
    (net (code "133") (name "/InS10_1") (class "Default")
      (node (ref "U41") (pin "11") (pinfunction "S1_11") (pintype "unspecified"))
      (node (ref "U7") (pin "31") (pinfunction "P31_31") (pintype "unspecified"))
    )
    (net (code "134") (name "/InS10_2") (class "Default")
      (node (ref "U41") (pin "10") (pinfunction "S2_10") (pintype "unspecified"))
      (node (ref "U5") (pin "32") (pinfunction "P4_32") (pintype "unspecified"))
    )
    (net (code "135") (name "/InS10_3") (class "Default")
      (node (ref "U41") (pin "9") (pinfunction "S3_9") (pintype "unspecified"))
      (node (ref "U5") (pin "30") (pinfunction "P5_30") (pintype "unspecified"))
    )
    (net (code "136") (name "/InS11_1") (class "Default")
      (node (ref "U35") (pin "11") (pinfunction "S1_11") (pintype "unspecified"))
      (node (ref "U5") (pin "28") (pinfunction "P6_28") (pintype "unspecified"))
    )
    (net (code "137") (name "/InS11_2") (class "Default")
      (node (ref "U35") (pin "10") (pinfunction "S2_10") (pintype "unspecified"))
      (node (ref "U5") (pin "26") (pinfunction "P7_26") (pintype "unspecified"))
    )
    (net (code "138") (name "/InS11_3") (class "Default")
      (node (ref "U35") (pin "9") (pinfunction "S3_9") (pintype "unspecified"))
      (node (ref "U5") (pin "5") (pinfunction "P8_5") (pintype "unspecified"))
    )
    (net (code "139") (name "/InS12_1") (class "Default")
      (node (ref "U42") (pin "11") (pinfunction "S1_11") (pintype "unspecified"))
      (node (ref "U5") (pin "7") (pinfunction "P9_7") (pintype "unspecified"))
    )
    (net (code "140") (name "/InS12_2") (class "Default")
      (node (ref "U42") (pin "10") (pinfunction "S2_10") (pintype "unspecified"))
      (node (ref "U5") (pin "9") (pinfunction "P10_9") (pintype "unspecified"))
    )
    (net (code "141") (name "/InS12_3") (class "Default")
      (node (ref "U42") (pin "9") (pinfunction "S3_9") (pintype "unspecified"))
      (node (ref "U5") (pin "11") (pinfunction "P11_11") (pintype "unspecified"))
    )
    (net (code "142") (name "/InS13_1") (class "Default")
      (node (ref "U36") (pin "11") (pinfunction "S1_11") (pintype "unspecified"))
      (node (ref "U5") (pin "6") (pinfunction "P12_6") (pintype "unspecified"))
    )
    (net (code "143") (name "/InS13_2") (class "Default")
      (node (ref "U36") (pin "10") (pinfunction "S2_10") (pintype "unspecified"))
      (node (ref "U5") (pin "8") (pinfunction "P13_8") (pintype "unspecified"))
    )
    (net (code "144") (name "/InS13_3") (class "Default")
      (node (ref "U36") (pin "9") (pinfunction "S3_9") (pintype "unspecified"))
      (node (ref "U5") (pin "10") (pinfunction "P14_10") (pintype "unspecified"))
    )
    (net (code "145") (name "/InS14_1") (class "Default")
      (node (ref "U43") (pin "11") (pinfunction "S1_11") (pintype "unspecified"))
      (node (ref "U5") (pin "12") (pinfunction "P15_12") (pintype "unspecified"))
    )
    (net (code "146") (name "/InS14_2") (class "Default")
      (node (ref "U43") (pin "10") (pinfunction "S2_10") (pintype "unspecified"))
      (node (ref "U5") (pin "13") (pinfunction "P16_13") (pintype "unspecified"))
    )
    (net (code "147") (name "/InS14_3") (class "Default")
      (node (ref "U43") (pin "9") (pinfunction "S3_9") (pintype "unspecified"))
      (node (ref "U5") (pin "14") (pinfunction "P17_14") (pintype "unspecified"))
    )
    (net (code "148") (name "/InS16B+_1") (class "Default")
      (node (ref "U4") (pin "32") (pinfunction "P4_32") (pintype "unspecified"))
      (node (ref "U47") (pin "15") (pinfunction "A0_15") (pintype "unspecified"))
    )
    (net (code "149") (name "/InS16B+_2") (class "Default")
      (node (ref "U4") (pin "30") (pinfunction "P5_30") (pintype "unspecified"))
      (node (ref "U47") (pin "14") (pinfunction "A1_14") (pintype "unspecified"))
    )
    (net (code "150") (name "/InS16B+_3") (class "Default")
      (node (ref "U4") (pin "28") (pinfunction "P6_28") (pintype "unspecified"))
      (node (ref "U47") (pin "11") (pinfunction "A2_11") (pintype "unspecified"))
    )
    (net (code "151") (name "/InS16B+_4") (class "Default")
      (node (ref "U4") (pin "26") (pinfunction "P7_26") (pintype "unspecified"))
      (node (ref "U47") (pin "10") (pinfunction "A3_10") (pintype "unspecified"))
    )
    (net (code "152") (name "/InS16B-_1") (class "Default")
      (node (ref "U4") (pin "5") (pinfunction "P8_5") (pintype "unspecified"))
      (node (ref "U48") (pin "15") (pinfunction "A0_15") (pintype "unspecified"))
    )
    (net (code "153") (name "/InS16B-_2") (class "Default")
      (node (ref "U4") (pin "7") (pinfunction "P9_7") (pintype "unspecified"))
      (node (ref "U48") (pin "14") (pinfunction "A1_14") (pintype "unspecified"))
    )
    (net (code "154") (name "/InS16B-_3") (class "Default")
      (node (ref "U4") (pin "9") (pinfunction "P10_9") (pintype "unspecified"))
      (node (ref "U48") (pin "11") (pinfunction "A2_11") (pintype "unspecified"))
    )
    (net (code "155") (name "/InS16B-_4") (class "Default")
      (node (ref "U4") (pin "11") (pinfunction "P11_11") (pintype "unspecified"))
      (node (ref "U48") (pin "10") (pinfunction "A3_10") (pintype "unspecified"))
    )
    (net (code "156") (name "/InS16B{slash}_1") (class "Default")
      (node (ref "U4") (pin "6") (pinfunction "P12_6") (pintype "unspecified"))
      (node (ref "U51") (pin "15") (pinfunction "A0_15") (pintype "unspecified"))
    )
    (net (code "157") (name "/InS16B{slash}_2") (class "Default")
      (node (ref "U4") (pin "8") (pinfunction "P13_8") (pintype "unspecified"))
      (node (ref "U51") (pin "14") (pinfunction "A1_14") (pintype "unspecified"))
    )
    (net (code "158") (name "/InS16B{slash}_3") (class "Default")
      (node (ref "U4") (pin "10") (pinfunction "P14_10") (pintype "unspecified"))
      (node (ref "U51") (pin "11") (pinfunction "A2_11") (pintype "unspecified"))
    )
    (net (code "159") (name "/InS16B{slash}_4") (class "Default")
      (node (ref "U4") (pin "12") (pinfunction "P15_12") (pintype "unspecified"))
      (node (ref "U51") (pin "10") (pinfunction "A3_10") (pintype "unspecified"))
    )
    (net (code "160") (name "/InS16V+_1") (class "Default")
      (node (ref "U4") (pin "13") (pinfunction "P16_13") (pintype "unspecified"))
      (node (ref "U46") (pin "17") (pinfunction "A0_17") (pintype "unspecified"))
    )
    (net (code "161") (name "/InS16V+_2") (class "Default")
      (node (ref "U4") (pin "14") (pinfunction "P17_14") (pintype "unspecified"))
      (node (ref "U46") (pin "16") (pinfunction "A1_16") (pintype "unspecified"))
    )
    (net (code "162") (name "/InS16V+_3") (class "Default")
      (node (ref "U4") (pin "15") (pinfunction "P18_15") (pintype "unspecified"))
      (node (ref "U46") (pin "15") (pinfunction "A2_15") (pintype "unspecified"))
    )
    (net (code "163") (name "/InS16V+_4") (class "Default")
      (node (ref "U4") (pin "16") (pinfunction "P19_16") (pintype "unspecified"))
    )
    (net (code "164") (name "/InS16V-_1") (class "Default")
      (node (ref "U4") (pin "17") (pinfunction "P20_17") (pintype "unspecified"))
      (node (ref "U50") (pin "17") (pinfunction "A0_17") (pintype "unspecified"))
    )
    (net (code "165") (name "/InS16V-_2") (class "Default")
      (node (ref "U4") (pin "18") (pinfunction "P21_18") (pintype "unspecified"))
      (node (ref "U50") (pin "16") (pinfunction "A1_16") (pintype "unspecified"))
    )
    (net (code "166") (name "/InS16V-_3") (class "Default")
      (node (ref "U4") (pin "19") (pinfunction "P22_19") (pintype "unspecified"))
      (node (ref "U50") (pin "15") (pinfunction "A2_15") (pintype "unspecified"))
    )
    (net (code "167") (name "/InS16V-_4") (class "Default")
      (node (ref "U4") (pin "20") (pinfunction "P23_20") (pintype "unspecified"))
    )
    (net (code "168") (name "/InS16_4") (class "Default")
      (node (ref "U46") (pin "14") (pinfunction "A3_14") (pintype "unspecified"))
      (node (ref "U50") (pin "14") (pinfunction "A3_14") (pintype "unspecified"))
    )
    (net (code "169") (name "/Iset1") (class "Default")
      (node (ref "R24") (pin "2") (pinfunction "2_2") (pintype "unspecified"))
      (node (ref "U7") (pin "1") (pinfunction "ISET_1") (pintype "unspecified"))
    )
    (net (code "170") (name "/Iset2") (class "Default")
      (node (ref "U5") (pin "1") (pinfunction "ISET_1") (pintype "unspecified"))
    )
    (net (code "171") (name "/Iset3") (class "Default")
      (node (ref "U4") (pin "1") (pinfunction "ISET_1") (pintype "unspecified"))
    )
    (net (code "172") (name "/Iset4") (class "Default")
      (node (ref "R28") (pin "2") (pinfunction "2_2") (pintype "unspecified"))
      (node (ref "U9") (pin "1") (pinfunction "ISET_1") (pintype "unspecified"))
    )
    (net (code "173") (name "/MISO") (class "Default")
      (node (ref "U11") (pin "16") (pinfunction "DATA_OUT_16") (pintype "unspecified"))
      (node (ref "U12") (pin "16") (pinfunction "DATA_OUT_16") (pintype "unspecified"))
      (node (ref "U2") (pin "9") (pinfunction "MISO_9") (pintype "unspecified"))
    )
    (net (code "174") (name "/MOSI") (class "Default")
      (node (ref "U11") (pin "17") (pinfunction "DATA_INPUT_17") (pintype "unspecified"))
      (node (ref "U12") (pin "17") (pinfunction "DATA_INPUT_17") (pintype "unspecified"))
    )
    (net (code "175") (name "/NRST") (class "Default")
      (node (ref "C26") (pin "2") (pinfunction "2_2") (pintype "unspecified"))
      (node (ref "KEY2") (pin "2") (pinfunction "2_2") (pintype "unspecified"))
      (node (ref "U10") (pin "7") (pinfunction "NRST_7") (pintype "unspecified"))
    )
    (net (code "176") (name "/NSS2") (class "Default")
      (node (ref "U11") (pin "18") (pinfunction "I/O_CLOCK_18") (pintype "unspecified"))
    )
    (net (code "177") (name "/NSS3") (class "Default")
      (node (ref "U12") (pin "18") (pinfunction "I/O_CLOCK_18") (pintype "unspecified"))
    )
    (net (code "178") (name "/NSS4") (class "Default")
      (node (ref "U2") (pin "7") (pinfunction "SCK_7") (pintype "unspecified"))
    )
    (net (code "179") (name "/OSC_In") (class "Default")
      (node (ref "C16") (pin "1") (pinfunction "1_1") (pintype "unspecified"))
      (node (ref "U10") (pin "5") (pinfunction "PH0-OSC_IN_5") (pintype "unspecified"))
      (node (ref "U13") (pin "P$1") (pinfunction "PIN1_P$1") (pintype "unspecified"))
    )
    (net (code "180") (name "/OSC_In32") (class "Default")
      (node (ref "C25") (pin "1") (pinfunction "1_1") (pintype "unspecified"))
      (node (ref "U10") (pin "3") (pinfunction "PC14-OSC32_IN_3") (pintype "unspecified"))
      (node (ref "U20") (pin "P$1") (pinfunction "PIN1_P$1") (pintype "unspecified"))
    )
    (net (code "181") (name "/OSC_OUT") (class "Default")
      (node (ref "C17") (pin "1") (pinfunction "1_1") (pintype "unspecified"))
      (node (ref "U10") (pin "6") (pinfunction "PH1-OSC_OUT_6") (pintype "unspecified"))
      (node (ref "U13") (pin "P$2") (pinfunction "PIN2_P$2") (pintype "unspecified"))
    )
    (net (code "182") (name "/OSC_OUT32") (class "Default")
      (node (ref "C24") (pin "1") (pinfunction "1_1") (pintype "unspecified"))
      (node (ref "U10") (pin "4") (pinfunction "PC15-OSC32_OUT_4") (pintype "unspecified"))
      (node (ref "U20") (pin "P$2") (pinfunction "PIN2_P$2") (pintype "unspecified"))
    )
    (net (code "183") (name "/OutS16B+") (class "Default")
      (node (ref "C69") (pin "1") (pinfunction "1_1") (pintype "unspecified"))
      (node (ref "R48") (pin "1") (pinfunction "1_1") (pintype "unspecified"))
      (node (ref "U47") (pin "29") (pinfunction "D_29") (pintype "unspecified"))
    )
    (net (code "184") (name "/OutS16B-") (class "Default")
      (node (ref "U48") (pin "29") (pinfunction "D_29") (pintype "unspecified"))
    )
    (net (code "185") (name "/OutS16B{slash}") (class "Default")
      (node (ref "U51") (pin "29") (pinfunction "D_29") (pintype "unspecified"))
    )
    (net (code "186") (name "/OutS16V+") (class "Default")
      (node (ref "R35") (pin "1") (pinfunction "1_1") (pintype "unspecified"))
      (node (ref "U46") (pin "28") (pinfunction "D_28") (pintype "unspecified"))
    )
    (net (code "187") (name "/OutS16V-") (class "Default")
      (node (ref "R34") (pin "1") (pinfunction "1_1") (pintype "unspecified"))
      (node (ref "U50") (pin "28") (pinfunction "D_28") (pintype "unspecified"))
    )
    (net (code "188") (name "/OutS16_B+") (class "Default")
      (node (ref "C71") (pin "1") (pinfunction "1_1") (pintype "unspecified"))
      (node (ref "D21") (pin "1") (pinfunction "C_1") (pintype "unspecified"))
      (node (ref "D23") (pin "1") (pinfunction "C_1") (pintype "unspecified"))
      (node (ref "Q8") (pin "3") (pinfunction "S2_3") (pintype "unspecified"))
      (node (ref "R51") (pin "1") (pinfunction "1_1") (pintype "unspecified"))
    )
    (net (code "189") (name "/OutS16_B-") (class "Default")
      (node (ref "C72") (pin "2") (pinfunction "2_2") (pintype "unspecified"))
      (node (ref "D22") (pin "2") (pinfunction "A_2") (pintype "unspecified"))
      (node (ref "D24") (pin "2") (pinfunction "A_2") (pintype "unspecified"))
      (node (ref "Q8") (pin "1") (pinfunction "S1_1") (pintype "unspecified"))
      (node (ref "R52") (pin "1") (pinfunction "1_1") (pintype "unspecified"))
    )
    (net (code "190") (name "/OutS16_B{slash}") (class "Default")
      (node (ref "C71") (pin "2") (pinfunction "2_2") (pintype "unspecified"))
      (node (ref "C72") (pin "1") (pinfunction "1_1") (pintype "unspecified"))
      (node (ref "L3") (pin "1") (pinfunction "1_1") (pintype "unspecified"))
      (node (ref "R49") (pin "1") (pinfunction "1_1") (pintype "unspecified"))
    )
    (net (code "191") (name "/Outs8_1") (class "Default")
      (node (ref "U30") (pin "3") (pinfunction "Z_3") (pintype "unspecified"))
      (node (ref "U46") (pin "19") (pinfunction "S1_19") (pintype "unspecified"))
      (node (ref "U47") (pin "17") (pinfunction "S1_17") (pintype "unspecified"))
      (node (ref "U48") (pin "17") (pinfunction "S1_17") (pintype "unspecified"))
      (node (ref "U50") (pin "19") (pinfunction "S1_19") (pintype "unspecified"))
      (node (ref "U51") (pin "17") (pinfunction "S1_17") (pintype "unspecified"))
    )
    (net (code "192") (name "/Outs8_2") (class "Default")
      (node (ref "U37") (pin "3") (pinfunction "Z_3") (pintype "unspecified"))
      (node (ref "U46") (pin "20") (pinfunction "S2_20") (pintype "unspecified"))
      (node (ref "U47") (pin "18") (pinfunction "S2_18") (pintype "unspecified"))
      (node (ref "U48") (pin "18") (pinfunction "S2_18") (pintype "unspecified"))
      (node (ref "U50") (pin "20") (pinfunction "S2_20") (pintype "unspecified"))
      (node (ref "U51") (pin "18") (pinfunction "S2_18") (pintype "unspecified"))
    )
    (net (code "193") (name "/Outs8_3") (class "Default")
      (node (ref "U31") (pin "3") (pinfunction "Z_3") (pintype "unspecified"))
      (node (ref "U46") (pin "21") (pinfunction "S3_21") (pintype "unspecified"))
      (node (ref "U47") (pin "19") (pinfunction "S3_19") (pintype "unspecified"))
      (node (ref "U48") (pin "19") (pinfunction "S3_19") (pintype "unspecified"))
      (node (ref "U50") (pin "21") (pinfunction "S3_21") (pintype "unspecified"))
      (node (ref "U51") (pin "19") (pinfunction "S3_19") (pintype "unspecified"))
    )
    (net (code "194") (name "/Outs8_4") (class "Default")
      (node (ref "U38") (pin "3") (pinfunction "Z_3") (pintype "unspecified"))
      (node (ref "U46") (pin "22") (pinfunction "S4_22") (pintype "unspecified"))
      (node (ref "U47") (pin "20") (pinfunction "S4_20") (pintype "unspecified"))
      (node (ref "U48") (pin "20") (pinfunction "S4_20") (pintype "unspecified"))
      (node (ref "U50") (pin "22") (pinfunction "S4_22") (pintype "unspecified"))
      (node (ref "U51") (pin "20") (pinfunction "S4_20") (pintype "unspecified"))
    )
    (net (code "195") (name "/Outs8_5") (class "Default")
      (node (ref "U32") (pin "3") (pinfunction "Z_3") (pintype "unspecified"))
      (node (ref "U46") (pin "23") (pinfunction "S5_23") (pintype "unspecified"))
      (node (ref "U47") (pin "21") (pinfunction "S5_21") (pintype "unspecified"))
      (node (ref "U48") (pin "21") (pinfunction "S5_21") (pintype "unspecified"))
      (node (ref "U50") (pin "23") (pinfunction "S5_23") (pintype "unspecified"))
      (node (ref "U51") (pin "21") (pinfunction "S5_21") (pintype "unspecified"))
    )
    (net (code "196") (name "/Outs8_6") (class "Default")
      (node (ref "U39") (pin "3") (pinfunction "Z_3") (pintype "unspecified"))
      (node (ref "U46") (pin "24") (pinfunction "S6_24") (pintype "unspecified"))
      (node (ref "U47") (pin "22") (pinfunction "S6_22") (pintype "unspecified"))
      (node (ref "U48") (pin "22") (pinfunction "S6_22") (pintype "unspecified"))
      (node (ref "U50") (pin "24") (pinfunction "S6_24") (pintype "unspecified"))
      (node (ref "U51") (pin "22") (pinfunction "S6_22") (pintype "unspecified"))
    )
    (net (code "197") (name "/Outs8_7") (class "Default")
      (node (ref "U33") (pin "3") (pinfunction "Z_3") (pintype "unspecified"))
      (node (ref "U46") (pin "25") (pinfunction "S7_25") (pintype "unspecified"))
      (node (ref "U47") (pin "23") (pinfunction "S7_23") (pintype "unspecified"))
      (node (ref "U48") (pin "23") (pinfunction "S7_23") (pintype "unspecified"))
      (node (ref "U50") (pin "25") (pinfunction "S7_25") (pintype "unspecified"))
      (node (ref "U51") (pin "23") (pinfunction "S7_23") (pintype "unspecified"))
    )
    (net (code "198") (name "/Outs8_8") (class "Default")
      (node (ref "U40") (pin "3") (pinfunction "Z_3") (pintype "unspecified"))
      (node (ref "U46") (pin "26") (pinfunction "S8_26") (pintype "unspecified"))
      (node (ref "U47") (pin "24") (pinfunction "S8_24") (pintype "unspecified"))
      (node (ref "U48") (pin "24") (pinfunction "S8_24") (pintype "unspecified"))
      (node (ref "U50") (pin "26") (pinfunction "S8_26") (pintype "unspecified"))
      (node (ref "U51") (pin "24") (pinfunction "S8_24") (pintype "unspecified"))
    )
    (net (code "199") (name "/Outs8_9") (class "Default")
      (node (ref "U34") (pin "3") (pinfunction "Z_3") (pintype "unspecified"))
      (node (ref "U46") (pin "11") (pinfunction "S9_11") (pintype "unspecified"))
      (node (ref "U47") (pin "8") (pinfunction "S9_8") (pintype "unspecified"))
      (node (ref "U48") (pin "8") (pinfunction "S9_8") (pintype "unspecified"))
      (node (ref "U50") (pin "11") (pinfunction "S9_11") (pintype "unspecified"))
      (node (ref "U51") (pin "8") (pinfunction "S9_8") (pintype "unspecified"))
    )
    (net (code "200") (name "/Outs8_10") (class "Default")
      (node (ref "U41") (pin "3") (pinfunction "Z_3") (pintype "unspecified"))
      (node (ref "U46") (pin "10") (pinfunction "S10_10") (pintype "unspecified"))
      (node (ref "U47") (pin "7") (pinfunction "S10_7") (pintype "unspecified"))
      (node (ref "U48") (pin "7") (pinfunction "S10_7") (pintype "unspecified"))
      (node (ref "U50") (pin "10") (pinfunction "S10_10") (pintype "unspecified"))
      (node (ref "U51") (pin "7") (pinfunction "S10_7") (pintype "unspecified"))
    )
    (net (code "201") (name "/Outs8_11") (class "Default")
      (node (ref "U35") (pin "3") (pinfunction "Z_3") (pintype "unspecified"))
      (node (ref "U46") (pin "9") (pinfunction "S11_9") (pintype "unspecified"))
      (node (ref "U47") (pin "6") (pinfunction "S11_6") (pintype "unspecified"))
      (node (ref "U48") (pin "6") (pinfunction "S11_6") (pintype "unspecified"))
      (node (ref "U50") (pin "9") (pinfunction "S11_9") (pintype "unspecified"))
      (node (ref "U51") (pin "6") (pinfunction "S11_6") (pintype "unspecified"))
    )
    (net (code "202") (name "/Outs8_12") (class "Default")
      (node (ref "U42") (pin "3") (pinfunction "Z_3") (pintype "unspecified"))
      (node (ref "U46") (pin "8") (pinfunction "S12_8") (pintype "unspecified"))
      (node (ref "U47") (pin "5") (pinfunction "S12_5") (pintype "unspecified"))
      (node (ref "U48") (pin "5") (pinfunction "S12_5") (pintype "unspecified"))
      (node (ref "U50") (pin "8") (pinfunction "S12_8") (pintype "unspecified"))
      (node (ref "U51") (pin "5") (pinfunction "S12_5") (pintype "unspecified"))
    )
    (net (code "203") (name "/Outs8_13") (class "Default")
      (node (ref "U36") (pin "3") (pinfunction "Z_3") (pintype "unspecified"))
      (node (ref "U46") (pin "7") (pinfunction "S13_7") (pintype "unspecified"))
      (node (ref "U47") (pin "4") (pinfunction "S13_4") (pintype "unspecified"))
      (node (ref "U48") (pin "4") (pinfunction "S13_4") (pintype "unspecified"))
      (node (ref "U50") (pin "7") (pinfunction "S13_7") (pintype "unspecified"))
      (node (ref "U51") (pin "4") (pinfunction "S13_4") (pintype "unspecified"))
    )
    (net (code "204") (name "/Outs8_14") (class "Default")
      (node (ref "U43") (pin "3") (pinfunction "Z_3") (pintype "unspecified"))
      (node (ref "U46") (pin "6") (pinfunction "S14_6") (pintype "unspecified"))
      (node (ref "U47") (pin "3") (pinfunction "S14_3") (pintype "unspecified"))
      (node (ref "U48") (pin "3") (pinfunction "S14_3") (pintype "unspecified"))
      (node (ref "U50") (pin "6") (pinfunction "S14_6") (pintype "unspecified"))
      (node (ref "U51") (pin "3") (pinfunction "S14_3") (pintype "unspecified"))
    )
    (net (code "205") (name "/PB") (class "Default")
      (node (ref "C69") (pin "2") (pinfunction "2_2") (pintype "unspecified"))
      (node (ref "D18") (pin "1") (pinfunction "K_1") (pintype "unspecified"))
      (node (ref "D19") (pin "1") (pinfunction "K_1") (pintype "unspecified"))
      (node (ref "Q5") (pin "1") (pinfunction "D_1") (pintype "unspecified"))
      (node (ref "Q5") (pin "2") (pinfunction "D_2") (pintype "unspecified"))
      (node (ref "Q5") (pin "5") (pinfunction "D_5") (pintype "unspecified"))
      (node (ref "Q5") (pin "6") (pinfunction "D_6") (pintype "unspecified"))
      (node (ref "Q7") (pin "3") (pinfunction "D_3") (pintype "unspecified"))
    )
    (net (code "206") (name "/PB_E") (class "Default")
      (node (ref "D16") (pin "1") (pinfunction "K_1") (pintype "unspecified"))
      (node (ref "R44") (pin "2") (pinfunction "2_2") (pintype "unspecified"))
      (node (ref "U9") (pin "23") (pinfunction "P26_23") (pintype "unspecified"))
    )
    (net (code "207") (name "/PC13") (class "Default")
      (node (ref "C22") (pin "2") (pinfunction "2_2") (pintype "unspecified"))
      (node (ref "KEY1") (pin "2") (pinfunction "2_2") (pintype "unspecified"))
      (node (ref "R27") (pin "1") (pinfunction "1_1") (pintype "unspecified"))
      (node (ref "U10") (pin "2") (pinfunction "PC13-ANTI_TAMP_2") (pintype "unspecified"))
    )
    (net (code "208") (name "/PWM_DOWN") (class "Default")
      (node (ref "U57") (pin "6") (pinfunction "S_6") (pintype "unspecified"))
    )
    (net (code "209") (name "/PWM_Down") (class "Default")
      (node (ref "U10") (pin "13") (pinfunction "PA3_13") (pintype "unspecified"))
    )
    (net (code "210") (name "/PWM_UP") (class "Default")
      (node (ref "U56") (pin "6") (pinfunction "S_6") (pintype "unspecified"))
    )
    (net (code "211") (name "/PWM_Up") (class "Default")
      (node (ref "U10") (pin "12") (pinfunction "PA2_12") (pintype "unspecified"))
    )
    (net (code "212") (name "/SPI1_MISO") (class "Default")
      (node (ref "U10") (pin "16") (pinfunction "PA6_16") (pintype "unspecified"))
      (node (ref "U6") (pin "12") (pinfunction "DOUT_12") (pintype "unspecified"))
      (node (ref "U7") (pin "4") (pinfunction "DOUT_4") (pintype "unspecified"))
    )
    (net (code "213") (name "/SPI1_MOSI") (class "Default")
      (node (ref "U10") (pin "17") (pinfunction "PA7_17") (pintype "unspecified"))
      (node (ref "U6") (pin "14") (pinfunction "DIN_14") (pintype "unspecified"))
      (node (ref "U7") (pin "34") (pinfunction "DIN_34") (pintype "unspecified"))
    )
    (net (code "214") (name "/SPI1_NSS") (class "Default")
      (node (ref "U10") (pin "14") (pinfunction "PA4_14") (pintype "unspecified"))
    )
    (net (code "215") (name "/SPI1_NSS2") (class "Default")
      (node (ref "U10") (pin "30") (pinfunction "PA9_30") (pintype "unspecified"))
      (node (ref "U6") (pin "15") (pinfunction "CS_15") (pintype "unspecified"))
      (node (ref "U7") (pin "35") (pinfunction "CS#_35") (pintype "unspecified"))
    )
    (net (code "216") (name "/SPI1_SCK") (class "Default")
      (node (ref "U10") (pin "15") (pinfunction "PA5_15") (pintype "unspecified"))
      (node (ref "U6") (pin "16") (pinfunction "DCLK_16") (pintype "unspecified"))
      (node (ref "U7") (pin "33") (pinfunction "SCLK_33") (pintype "unspecified"))
    )
    (net (code "217") (name "/SPI2_MISO") (class "Default")
      (node (ref "U10") (pin "27") (pinfunction "PB14_27") (pintype "unspecified"))
      (node (ref "U5") (pin "4") (pinfunction "DOUT_4") (pintype "unspecified"))
      (node (ref "U9") (pin "4") (pinfunction "DOUT_4") (pintype "unspecified"))
    )
    (net (code "218") (name "/SPI2_MOSI") (class "Default")
      (node (ref "U10") (pin "28") (pinfunction "PB15_28") (pintype "unspecified"))
      (node (ref "U5") (pin "34") (pinfunction "DIN_34") (pintype "unspecified"))
      (node (ref "U9") (pin "34") (pinfunction "DIN_34") (pintype "unspecified"))
    )
    (net (code "219") (name "/SPI2_NSS") (class "Default")
      (node (ref "U10") (pin "46") (pinfunction "PB9_46") (pintype "unspecified"))
    )
    (net (code "220") (name "/SPI2_NSS2") (class "Default")
      (node (ref "U10") (pin "29") (pinfunction "PA8_29") (pintype "unspecified"))
      (node (ref "U5") (pin "35") (pinfunction "CS#_35") (pintype "unspecified"))
      (node (ref "U9") (pin "35") (pinfunction "CS#_35") (pintype "unspecified"))
    )
    (net (code "221") (name "/SPI2_NSS3") (class "Default")
      (node (ref "U10") (pin "42") (pinfunction "PB6_42") (pintype "unspecified"))
    )
    (net (code "222") (name "/SPI2_SCK") (class "Default")
      (node (ref "U10") (pin "21") (pinfunction "PB10_21") (pintype "unspecified"))
      (node (ref "U5") (pin "33") (pinfunction "SCLK_33") (pintype "unspecified"))
      (node (ref "U9") (pin "33") (pinfunction "SCLK_33") (pintype "unspecified"))
    )
    (net (code "223") (name "/SPI3_CSK") (class "Default")
      (node (ref "U52") (pin "9") (pinfunction "CS#_9") (pintype "unspecified"))
    )
    (net (code "224") (name "/SPI3_MISO") (class "Default")
      (node (ref "U10") (pin "40") (pinfunction "PB4_40") (pintype "unspecified"))
      (node (ref "U4") (pin "4") (pinfunction "DOUT_4") (pintype "unspecified"))
      (node (ref "U52") (pin "1") (pinfunction "DOUT_1") (pintype "unspecified"))
    )
    (net (code "225") (name "/SPI3_MOSI") (class "Default")
      (node (ref "U10") (pin "41") (pinfunction "PB5_41") (pintype "unspecified"))
      (node (ref "U4") (pin "34") (pinfunction "DIN_34") (pintype "unspecified"))
    )
    (net (code "226") (name "/SPI3_NSS") (class "Default")
      (node (ref "U10") (pin "38") (pinfunction "PA15_38") (pintype "unspecified"))
    )
    (net (code "227") (name "/SPI3_NSS2") (class "Default")
      (node (ref "U10") (pin "10") (pinfunction "PA0-WKUP_10") (pintype "unspecified"))
      (node (ref "U10") (pin "43") (pinfunction "PB7_43") (pintype "unspecified"))
      (node (ref "U4") (pin "35") (pinfunction "CS#_35") (pintype "unspecified"))
      (node (ref "U52") (pin "10") (pinfunction "SCLK_10") (pintype "unspecified"))
    )
    (net (code "228") (name "/SPI3_SCK") (class "Default")
      (node (ref "U10") (pin "39") (pinfunction "PB3_39") (pintype "unspecified"))
      (node (ref "U4") (pin "33") (pinfunction "SCLK_33") (pintype "unspecified"))
    )
    (net (code "229") (name "/SPI4_MISO") (class "Default")
      (node (ref "U10") (pin "32") (pinfunction "PA11_32") (pintype "unspecified"))
      (node (ref "U44") (pin "4") (pinfunction "MISO_4") (pintype "unspecified"))
    )
    (net (code "230") (name "/SPI4_MOSI") (class "Default")
      (node (ref "U10") (pin "11") (pinfunction "PA1_11") (pintype "unspecified"))
      (node (ref "U44") (pin "2") (pinfunction "MOSI_2") (pintype "unspecified"))
    )
    (net (code "231") (name "/SPI4_NSS") (class "Default")
      (node (ref "U10") (pin "25") (pinfunction "PB12_25") (pintype "unspecified"))
    )
    (net (code "232") (name "/SPI4_NSS2") (class "Default")
      (node (ref "U10") (pin "45") (pinfunction "PB8_45") (pintype "unspecified"))
      (node (ref "U44") (pin "1") (pinfunction "CS_1") (pintype "unspecified"))
    )
    (net (code "233") (name "/SPI4_SCK") (class "Default")
      (node (ref "U10") (pin "26") (pinfunction "PB13_26") (pintype "unspecified"))
      (node (ref "U44") (pin "5") (pinfunction "SCL_5") (pintype "unspecified"))
    )
    (net (code "234") (name "/SPI5_MISO") (class "Default")
      (node (ref "U10") (pin "33") (pinfunction "PA12_33") (pintype "unspecified"))
    )
    (net (code "235") (name "/SPI5_MOSI") (class "Default")
      (node (ref "U10") (pin "31") (pinfunction "PA10_31") (pintype "unspecified"))
      (node (ref "U2") (pin "6") (pinfunction "MOSI_6") (pintype "unspecified"))
    )
    (net (code "236") (name "/SPI5_NSS") (class "Default")
      (node (ref "U10") (pin "19") (pinfunction "PB1_19") (pintype "unspecified"))
    )
    (net (code "237") (name "/SPI5_NSS1") (class "Default")
      (node (ref "U2") (pin "3") (pinfunction "CS_3") (pintype "unspecified"))
    )
    (net (code "238") (name "/SPI5_NSS2") (class "Default")
      (node (ref "U10") (pin "20") (pinfunction "PB2_20") (pintype "unspecified"))
    )
    (net (code "239") (name "/SPI5_SCK") (class "Default")
      (node (ref "U10") (pin "18") (pinfunction "PB0_18") (pintype "unspecified"))
    )
    (net (code "240") (name "/SW_enc") (class "Default")
      (node (ref "U3") (pin "3") (pinfunction "SW_3") (pintype "unspecified"))
      (node (ref "U9") (pin "18") (pinfunction "P21_18") (pintype "unspecified"))
    )
    (net (code "241") (name "/SYS_JTCK-SWCLK") (class "Default")
      (node (ref "U10") (pin "37") (pinfunction "PA14_37") (pintype "unspecified"))
    )
    (net (code "242") (name "/SYS_JTMS-SWD") (class "Default")
      (node (ref "U10") (pin "34") (pinfunction "PA13_34") (pintype "unspecified"))
    )
    (net (code "243") (name "/T_CLK") (class "Default")
      (node (ref "U2") (pin "10") (pinfunction "T_CLK_10") (pintype "unspecified"))
    )
    (net (code "244") (name "/T_CS") (class "Default")
      (node (ref "U2") (pin "11") (pinfunction "T_CS_11") (pintype "unspecified"))
    )
    (net (code "245") (name "/T_DIN") (class "Default")
      (node (ref "U2") (pin "12") (pinfunction "T_DIN_12") (pintype "unspecified"))
    )
    (net (code "246") (name "/T_DO") (class "Default")
      (node (ref "U2") (pin "13") (pinfunction "T_DO_13") (pintype "unspecified"))
    )
    (net (code "247") (name "/T_IRQ") (class "Default")
      (node (ref "R1") (pin "1") (pinfunction "1_1") (pintype "input"))
      (node (ref "U2") (pin "14") (pinfunction "T_IRQ_14") (pintype "unspecified"))
      (node (ref "U9") (pin "15") (pinfunction "P18_15") (pintype "unspecified"))
    )
    (net (code "248") (name "/T_IRQ_R") (class "Default")
      (node (ref "R1") (pin "2") (pinfunction "2_2") (pintype "input"))
    )
    (net (code "249") (name "/V+1") (class "Default")
      (node (ref "C8") (pin "2") (pinfunction "2_2") (pintype "unspecified"))
      (node (ref "U7") (pin "36") (pinfunction "V+_36") (pintype "unspecified"))
    )
    (net (code "250") (name "/V+2") (class "Default")
      (node (ref "U5") (pin "36") (pinfunction "V+_36") (pintype "unspecified"))
    )
    (net (code "251") (name "/V+3") (class "Default")
      (node (ref "U4") (pin "36") (pinfunction "V+_36") (pintype "unspecified"))
    )
    (net (code "252") (name "/V+4") (class "Default")
      (node (ref "C23") (pin "2") (pinfunction "2_2") (pintype "unspecified"))
      (node (ref "U9") (pin "36") (pinfunction "V+_36") (pintype "unspecified"))
    )
    (net (code "253") (name "/V1_1") (class "Default")
      (node (ref "U43") (pin "1") (pinfunction "Y4_1") (pintype "unspecified"))
      (node (ref "U46") (pin "4") (pinfunction "S16_4") (pintype "unspecified"))
      (node (ref "U46") (pin "5") (pinfunction "S15_5") (pintype "unspecified"))
      (node (ref "U47") (pin "1") (pinfunction "S16_1") (pintype "unspecified"))
      (node (ref "U47") (pin "2") (pinfunction "S15_2") (pintype "unspecified"))
      (node (ref "U48") (pin "1") (pinfunction "S16_1") (pintype "unspecified"))
      (node (ref "U48") (pin "2") (pinfunction "S15_2") (pintype "unspecified"))
      (node (ref "U50") (pin "4") (pinfunction "S16_4") (pintype "unspecified"))
      (node (ref "U50") (pin "5") (pinfunction "S15_5") (pintype "unspecified"))
      (node (ref "U51") (pin "1") (pinfunction "S16_1") (pintype "unspecified"))
      (node (ref "U51") (pin "2") (pinfunction "S15_2") (pintype "unspecified"))
    )
    (net (code "254") (name "/V1_2") (class "Default")
      (node (ref "U30") (pin "13") (pinfunction "Y0_13") (pintype "unspecified"))
    )
    (net (code "255") (name "/V1_3") (class "Default")
      (node (ref "U31") (pin "15") (pinfunction "Y2_15") (pintype "unspecified"))
    )
    (net (code "256") (name "/V1_4") (class "Default")
      (node (ref "U32") (pin "1") (pinfunction "Y4_1") (pintype "unspecified"))
    )
    (net (code "257") (name "/V1_5") (class "Default")
      (node (ref "U33") (pin "2") (pinfunction "Y6_2") (pintype "unspecified"))
    )
    (net (code "258") (name "/V1_6") (class "Default")
      (node (ref "U41") (pin "13") (pinfunction "Y0_13") (pintype "unspecified"))
    )
    (net (code "259") (name "/V1_7") (class "Default")
      (node (ref "U42") (pin "15") (pinfunction "Y2_15") (pintype "unspecified"))
    )
    (net (code "260") (name "/V2_2") (class "Default")
      (node (ref "U30") (pin "14") (pinfunction "Y1_14") (pintype "unspecified"))
    )
    (net (code "261") (name "/V2_3") (class "Default")
      (node (ref "U31") (pin "12") (pinfunction "Y3_12") (pintype "unspecified"))
    )
    (net (code "262") (name "/V2_4") (class "Default")
      (node (ref "U32") (pin "5") (pinfunction "Y5_5") (pintype "unspecified"))
    )
    (net (code "263") (name "/V2_5") (class "Default")
      (node (ref "U33") (pin "4") (pinfunction "Y7_4") (pintype "unspecified"))
    )
    (net (code "264") (name "/V2_6") (class "Default")
      (node (ref "U41") (pin "14") (pinfunction "Y1_14") (pintype "unspecified"))
    )
    (net (code "265") (name "/V2_7") (class "Default")
      (node (ref "U42") (pin "12") (pinfunction "Y3_12") (pintype "unspecified"))
    )
    (net (code "266") (name "/V3_2") (class "Default")
      (node (ref "U30") (pin "15") (pinfunction "Y2_15") (pintype "unspecified"))
    )
    (net (code "267") (name "/V3_3") (class "Default")
      (node (ref "U31") (pin "1") (pinfunction "Y4_1") (pintype "unspecified"))
    )
    (net (code "268") (name "/V3_4") (class "Default")
      (node (ref "U32") (pin "2") (pinfunction "Y6_2") (pintype "unspecified"))
    )
    (net (code "269") (name "/V3_5") (class "Default")
      (node (ref "U40") (pin "13") (pinfunction "Y0_13") (pintype "unspecified"))
    )
    (net (code "270") (name "/V3_6") (class "Default")
      (node (ref "U41") (pin "15") (pinfunction "Y2_15") (pintype "unspecified"))
    )
    (net (code "271") (name "/V3_7") (class "Default")
      (node (ref "U42") (pin "1") (pinfunction "Y4_1") (pintype "unspecified"))
    )
    (net (code "272") (name "/V4_2") (class "Default")
      (node (ref "U30") (pin "12") (pinfunction "Y3_12") (pintype "unspecified"))
    )
    (net (code "273") (name "/V4_3") (class "Default")
      (node (ref "U31") (pin "5") (pinfunction "Y5_5") (pintype "unspecified"))
    )
    (net (code "274") (name "/V4_4") (class "Default")
      (node (ref "U32") (pin "4") (pinfunction "Y7_4") (pintype "unspecified"))
    )
    (net (code "275") (name "/V4_5") (class "Default")
      (node (ref "U40") (pin "14") (pinfunction "Y1_14") (pintype "unspecified"))
    )
    (net (code "276") (name "/V4_6") (class "Default")
      (node (ref "U41") (pin "12") (pinfunction "Y3_12") (pintype "unspecified"))
    )
    (net (code "277") (name "/V4_7") (class "Default")
      (node (ref "U42") (pin "5") (pinfunction "Y5_5") (pintype "unspecified"))
    )
    (net (code "278") (name "/V5_2") (class "Default")
      (node (ref "U30") (pin "1") (pinfunction "Y4_1") (pintype "unspecified"))
    )
    (net (code "279") (name "/V5_3") (class "Default")
      (node (ref "U31") (pin "2") (pinfunction "Y6_2") (pintype "unspecified"))
    )
    (net (code "280") (name "/V5_4") (class "Default")
      (node (ref "U39") (pin "13") (pinfunction "Y0_13") (pintype "unspecified"))
    )
    (net (code "281") (name "/V5_5") (class "Default")
      (node (ref "U40") (pin "15") (pinfunction "Y2_15") (pintype "unspecified"))
    )
    (net (code "282") (name "/V5_6") (class "Default")
      (node (ref "U41") (pin "1") (pinfunction "Y4_1") (pintype "unspecified"))
    )
    (net (code "283") (name "/V5_7") (class "Default")
      (node (ref "U42") (pin "2") (pinfunction "Y6_2") (pintype "unspecified"))
    )
    (net (code "284") (name "/V6_2") (class "Default")
      (node (ref "U30") (pin "5") (pinfunction "Y5_5") (pintype "unspecified"))
    )
    (net (code "285") (name "/V6_3") (class "Default")
      (node (ref "U31") (pin "4") (pinfunction "Y7_4") (pintype "unspecified"))
    )
    (net (code "286") (name "/V6_4") (class "Default")
      (node (ref "U39") (pin "14") (pinfunction "Y1_14") (pintype "unspecified"))
    )
    (net (code "287") (name "/V6_5") (class "Default")
      (node (ref "U40") (pin "12") (pinfunction "Y3_12") (pintype "unspecified"))
    )
    (net (code "288") (name "/V6_6") (class "Default")
      (node (ref "U41") (pin "5") (pinfunction "Y5_5") (pintype "unspecified"))
    )
    (net (code "289") (name "/V6_7") (class "Default")
      (node (ref "U42") (pin "4") (pinfunction "Y7_4") (pintype "unspecified"))
    )
    (net (code "290") (name "/V7_2") (class "Default")
      (node (ref "U30") (pin "2") (pinfunction "Y6_2") (pintype "unspecified"))
    )
    (net (code "291") (name "/V7_3") (class "Default")
      (node (ref "U38") (pin "13") (pinfunction "Y0_13") (pintype "unspecified"))
    )
    (net (code "292") (name "/V7_4") (class "Default")
      (node (ref "U39") (pin "15") (pinfunction "Y2_15") (pintype "unspecified"))
    )
    (net (code "293") (name "/V7_5") (class "Default")
      (node (ref "U40") (pin "1") (pinfunction "Y4_1") (pintype "unspecified"))
    )
    (net (code "294") (name "/V7_6") (class "Default")
      (node (ref "U41") (pin "2") (pinfunction "Y6_2") (pintype "unspecified"))
    )
    (net (code "295") (name "/V7_7") (class "Default")
      (node (ref "U36") (pin "13") (pinfunction "Y0_13") (pintype "unspecified"))
    )
    (net (code "296") (name "/V8_2") (class "Default")
      (node (ref "U30") (pin "4") (pinfunction "Y7_4") (pintype "unspecified"))
    )
    (net (code "297") (name "/V8_3") (class "Default")
      (node (ref "U38") (pin "14") (pinfunction "Y1_14") (pintype "unspecified"))
    )
    (net (code "298") (name "/V8_4") (class "Default")
      (node (ref "U39") (pin "12") (pinfunction "Y3_12") (pintype "unspecified"))
    )
    (net (code "299") (name "/V8_5") (class "Default")
      (node (ref "U40") (pin "5") (pinfunction "Y5_5") (pintype "unspecified"))
    )
    (net (code "300") (name "/V8_6") (class "Default")
      (node (ref "U41") (pin "4") (pinfunction "Y7_4") (pintype "unspecified"))
    )
    (net (code "301") (name "/V8_7") (class "Default")
      (node (ref "U36") (pin "14") (pinfunction "Y1_14") (pintype "unspecified"))
    )
    (net (code "302") (name "/V9_2") (class "Default")
      (node (ref "U37") (pin "13") (pinfunction "Y0_13") (pintype "unspecified"))
    )
    (net (code "303") (name "/V9_3") (class "Default")
      (node (ref "U38") (pin "15") (pinfunction "Y2_15") (pintype "unspecified"))
    )
    (net (code "304") (name "/V9_4") (class "Default")
      (node (ref "U39") (pin "1") (pinfunction "Y4_1") (pintype "unspecified"))
    )
    (net (code "305") (name "/V9_5") (class "Default")
      (node (ref "U40") (pin "2") (pinfunction "Y6_2") (pintype "unspecified"))
    )
    (net (code "306") (name "/V9_6") (class "Default")
      (node (ref "U35") (pin "13") (pinfunction "Y0_13") (pintype "unspecified"))
    )
    (net (code "307") (name "/V9_7") (class "Default")
      (node (ref "U36") (pin "15") (pinfunction "Y2_15") (pintype "unspecified"))
    )
    (net (code "308") (name "/V10_2") (class "Default")
      (node (ref "U37") (pin "14") (pinfunction "Y1_14") (pintype "unspecified"))
    )
    (net (code "309") (name "/V10_3") (class "Default")
      (node (ref "U38") (pin "12") (pinfunction "Y3_12") (pintype "unspecified"))
    )
    (net (code "310") (name "/V10_4") (class "Default")
      (node (ref "U39") (pin "5") (pinfunction "Y5_5") (pintype "unspecified"))
    )
    (net (code "311") (name "/V10_5") (class "Default")
      (node (ref "U40") (pin "4") (pinfunction "Y7_4") (pintype "unspecified"))
    )
    (net (code "312") (name "/V10_6") (class "Default")
      (node (ref "U35") (pin "14") (pinfunction "Y1_14") (pintype "unspecified"))
    )
    (net (code "313") (name "/V10_7") (class "Default")
      (node (ref "U36") (pin "12") (pinfunction "Y3_12") (pintype "unspecified"))
    )
    (net (code "314") (name "/V11_2") (class "Default")
      (node (ref "U37") (pin "15") (pinfunction "Y2_15") (pintype "unspecified"))
    )
    (net (code "315") (name "/V11_3") (class "Default")
      (node (ref "U38") (pin "1") (pinfunction "Y4_1") (pintype "unspecified"))
    )
    (net (code "316") (name "/V11_4") (class "Default")
      (node (ref "U39") (pin "2") (pinfunction "Y6_2") (pintype "unspecified"))
    )
    (net (code "317") (name "/V11_5") (class "Default")
      (node (ref "U34") (pin "13") (pinfunction "Y0_13") (pintype "unspecified"))
    )
    (net (code "318") (name "/V11_6") (class "Default")
      (node (ref "U35") (pin "15") (pinfunction "Y2_15") (pintype "unspecified"))
    )
    (net (code "319") (name "/V11_7") (class "Default")
      (node (ref "U36") (pin "1") (pinfunction "Y4_1") (pintype "unspecified"))
    )
    (net (code "320") (name "/V12_2") (class "Default")
      (node (ref "U37") (pin "12") (pinfunction "Y3_12") (pintype "unspecified"))
    )
    (net (code "321") (name "/V12_3") (class "Default")
      (node (ref "U38") (pin "5") (pinfunction "Y5_5") (pintype "unspecified"))
    )
    (net (code "322") (name "/V12_4") (class "Default")
      (node (ref "U39") (pin "4") (pinfunction "Y7_4") (pintype "unspecified"))
    )
    (net (code "323") (name "/V12_5") (class "Default")
      (node (ref "U34") (pin "14") (pinfunction "Y1_14") (pintype "unspecified"))
    )
    (net (code "324") (name "/V12_6") (class "Default")
      (node (ref "U35") (pin "12") (pinfunction "Y3_12") (pintype "unspecified"))
    )
    (net (code "325") (name "/V12_7") (class "Default")
      (node (ref "U36") (pin "5") (pinfunction "Y5_5") (pintype "unspecified"))
    )
    (net (code "326") (name "/V13_2") (class "Default")
      (node (ref "U37") (pin "1") (pinfunction "Y4_1") (pintype "unspecified"))
    )
    (net (code "327") (name "/V13_3") (class "Default")
      (node (ref "U38") (pin "2") (pinfunction "Y6_2") (pintype "unspecified"))
    )
    (net (code "328") (name "/V13_4") (class "Default")
      (node (ref "U33") (pin "13") (pinfunction "Y0_13") (pintype "unspecified"))
    )
    (net (code "329") (name "/V13_5") (class "Default")
      (node (ref "U34") (pin "15") (pinfunction "Y2_15") (pintype "unspecified"))
    )
    (net (code "330") (name "/V13_6") (class "Default")
      (node (ref "U35") (pin "1") (pinfunction "Y4_1") (pintype "unspecified"))
    )
    (net (code "331") (name "/V13_7") (class "Default")
      (node (ref "U36") (pin "2") (pinfunction "Y6_2") (pintype "unspecified"))
    )
    (net (code "332") (name "/V14_2") (class "Default")
      (node (ref "U37") (pin "5") (pinfunction "Y5_5") (pintype "unspecified"))
    )
    (net (code "333") (name "/V14_3") (class "Default")
      (node (ref "U38") (pin "4") (pinfunction "Y7_4") (pintype "unspecified"))
    )
    (net (code "334") (name "/V14_4") (class "Default")
      (node (ref "U33") (pin "14") (pinfunction "Y1_14") (pintype "unspecified"))
    )
    (net (code "335") (name "/V14_5") (class "Default")
      (node (ref "U34") (pin "12") (pinfunction "Y3_12") (pintype "unspecified"))
    )
    (net (code "336") (name "/V14_6") (class "Default")
      (node (ref "U35") (pin "5") (pinfunction "Y5_5") (pintype "unspecified"))
    )
    (net (code "337") (name "/V14_7") (class "Default")
      (node (ref "U36") (pin "4") (pinfunction "Y7_4") (pintype "unspecified"))
    )
    (net (code "338") (name "/V15_2") (class "Default")
      (node (ref "U37") (pin "2") (pinfunction "Y6_2") (pintype "unspecified"))
    )
    (net (code "339") (name "/V15_3") (class "Default")
      (node (ref "U32") (pin "13") (pinfunction "Y0_13") (pintype "unspecified"))
    )
    (net (code "340") (name "/V15_4") (class "Default")
      (node (ref "U33") (pin "15") (pinfunction "Y2_15") (pintype "unspecified"))
    )
    (net (code "341") (name "/V15_5") (class "Default")
      (node (ref "U34") (pin "1") (pinfunction "Y4_1") (pintype "unspecified"))
    )
    (net (code "342") (name "/V15_6") (class "Default")
      (node (ref "U35") (pin "2") (pinfunction "Y6_2") (pintype "unspecified"))
    )
    (net (code "343") (name "/V15_7") (class "Default")
      (node (ref "U43") (pin "13") (pinfunction "Y0_13") (pintype "unspecified"))
    )
    (net (code "344") (name "/V16_2") (class "Default")
      (node (ref "U37") (pin "4") (pinfunction "Y7_4") (pintype "unspecified"))
    )
    (net (code "345") (name "/V16_3") (class "Default")
      (node (ref "U32") (pin "14") (pinfunction "Y1_14") (pintype "unspecified"))
    )
    (net (code "346") (name "/V16_4") (class "Default")
      (node (ref "U33") (pin "12") (pinfunction "Y3_12") (pintype "unspecified"))
    )
    (net (code "347") (name "/V16_5") (class "Default")
      (node (ref "U34") (pin "5") (pinfunction "Y5_5") (pintype "unspecified"))
    )
    (net (code "348") (name "/V16_6") (class "Default")
      (node (ref "U35") (pin "4") (pinfunction "Y7_4") (pintype "unspecified"))
    )
    (net (code "349") (name "/V16_7") (class "Default")
      (node (ref "U43") (pin "14") (pinfunction "Y1_14") (pintype "unspecified"))
    )
    (net (code "350") (name "/V17_2") (class "Default")
      (node (ref "U31") (pin "13") (pinfunction "Y0_13") (pintype "unspecified"))
    )
    (net (code "351") (name "/V17_3") (class "Default")
      (node (ref "U32") (pin "15") (pinfunction "Y2_15") (pintype "unspecified"))
    )
    (net (code "352") (name "/V17_4") (class "Default")
      (node (ref "U33") (pin "1") (pinfunction "Y4_1") (pintype "unspecified"))
    )
    (net (code "353") (name "/V17_5") (class "Default")
      (node (ref "U34") (pin "2") (pinfunction "Y6_2") (pintype "unspecified"))
    )
    (net (code "354") (name "/V17_6") (class "Default")
      (node (ref "U42") (pin "13") (pinfunction "Y0_13") (pintype "unspecified"))
    )
    (net (code "355") (name "/V17_7") (class "Default")
      (node (ref "U43") (pin "15") (pinfunction "Y2_15") (pintype "unspecified"))
    )
    (net (code "356") (name "/V18_2") (class "Default")
      (node (ref "U31") (pin "14") (pinfunction "Y1_14") (pintype "unspecified"))
    )
    (net (code "357") (name "/V18_3") (class "Default")
      (node (ref "U32") (pin "12") (pinfunction "Y3_12") (pintype "unspecified"))
    )
    (net (code "358") (name "/V18_4") (class "Default")
      (node (ref "U33") (pin "5") (pinfunction "Y5_5") (pintype "unspecified"))
    )
    (net (code "359") (name "/V18_5") (class "Default")
      (node (ref "U34") (pin "4") (pinfunction "Y7_4") (pintype "unspecified"))
    )
    (net (code "360") (name "/V18_6") (class "Default")
      (node (ref "U42") (pin "14") (pinfunction "Y1_14") (pintype "unspecified"))
    )
    (net (code "361") (name "/V18_7") (class "Default")
      (node (ref "U43") (pin "12") (pinfunction "Y3_12") (pintype "unspecified"))
    )
    (net (code "362") (name "/VCC_F_1") (class "Default")
      (node (ref "C29") (pin "1") (pinfunction "1_1") (pintype "unspecified"))
      (node (ref "C31") (pin "1") (pinfunction "1_1") (pintype "unspecified"))
      (node (ref "U27") (pin "8") (pinfunction "VCC_8") (pintype "unspecified"))
      (node (ref "U28") (pin "8") (pinfunction "VCC_8") (pintype "unspecified"))
    )
    (net (code "363") (name "/VDD") (class "Default")
      (node (ref "R27") (pin "2") (pinfunction "2_2") (pintype "unspecified"))
    )
    (net (code "364") (name "/V_CAP") (class "Default")
      (node (ref "C9") (pin "2") (pinfunction "2_2") (pintype "unspecified"))
      (node (ref "U10") (pin "22") (pinfunction "VCAP-1_22") (pintype "unspecified"))
    )
    (net (code "365") (name "/charger_block") (class "Default")
      (node (ref "C48") (pin "1") (pinfunction "1_1") (pintype "unspecified"))
      (node (ref "R41") (pin "2") (pinfunction "2_2") (pintype "unspecified"))
      (node (ref "RSH") (pin "1") (pinfunction "1_1") (pintype "unspecified"))
    )
    (net (code "366") (name "/f1_node") (class "Default")
      (node (ref "F1") (pin "1") (pinfunction "1_1") (pintype "unspecified"))
    )
    (net (code "367") (name "/fl_node") (class "Default")
      (node (ref "D3") (pin "2") (pinfunction "A_2") (pintype "unspecified"))
      (node (ref "D4") (pin "2") (pinfunction "A_2") (pintype "unspecified"))
      (node (ref "Q1") (pin "3") (pinfunction "D_3") (pintype "unspecified"))
      (node (ref "Q2") (pin "3") (pinfunction "D_3") (pintype "unspecified"))
      (node (ref "U29") (pin "2") (pinfunction "IN_2") (pintype "unspecified"))
    )
    (net (code "368") (name "/im_e") (class "Default")
      (node (ref "U11") (pin "19") (pinfunction "EOC_19") (pintype "unspecified"))
      (node (ref "U12") (pin "19") (pinfunction "EOC_19") (pintype "unspecified"))
      (node (ref "U9") (pin "29") (pinfunction "P30_29") (pintype "unspecified"))
    )
    (net (code "369") (name "/ind_1") (class "Default")
      (node (ref "U8") (pin "11") (pinfunction "SHCP_11") (pintype "unspecified"))
      (node (ref "U9") (pin "19") (pinfunction "P22_19") (pintype "unspecified"))
    )
    (net (code "370") (name "/ind_2") (class "Default")
      (node (ref "U8") (pin "12") (pinfunction "STCP_12") (pintype "unspecified"))
      (node (ref "U9") (pin "20") (pinfunction "P23_20") (pintype "unspecified"))
    )
    (net (code "371") (name "/ind_3") (class "Default")
      (node (ref "U8") (pin "14") (pinfunction "DS_14") (pintype "unspecified"))
      (node (ref "U9") (pin "21") (pinfunction "P24_21") (pintype "unspecified"))
    )
    (net (code "372") (name "/p1_en") (class "Default")
      (node (ref "D1") (pin "2") (pinfunction "A_2") (pintype "unspecified"))
      (node (ref "R20") (pin "2") (pinfunction "2_2") (pintype "unspecified"))
      (node (ref "U4") (pin "23") (pinfunction "P26_23") (pintype "unspecified"))
    )
    (net (code "373") (name "/p2_en") (class "Default")
      (node (ref "U4") (pin "24") (pinfunction "P27_24") (pintype "unspecified"))
    )
    (net (code "374") (name "/p3_en") (class "Default")
      (node (ref "U4") (pin "25") (pinfunction "P28_25") (pintype "unspecified"))
    )
    (net (code "375") (name "/p4_en") (class "Default")
      (node (ref "U4") (pin "27") (pinfunction "P29_27") (pintype "unspecified"))
    )
    (net (code "376") (name "/p5_en") (class "Default")
      (node (ref "U4") (pin "29") (pinfunction "P30_29") (pintype "unspecified"))
    )
    (net (code "377") (name "/p6_en") (class "Default")
      (node (ref "U4") (pin "31") (pinfunction "P31_31") (pintype "unspecified"))
    )
    (net (code "378") (name "/p7_en") (class "Default")
      (node (ref "U9") (pin "32") (pinfunction "P4_32") (pintype "unspecified"))
    )
    (net (code "379") (name "/p8_en") (class "Default")
      (node (ref "U9") (pin "30") (pinfunction "P5_30") (pintype "unspecified"))
    )
    (net (code "380") (name "/p9_en") (class "Default")
      (node (ref "U9") (pin "28") (pinfunction "P6_28") (pintype "unspecified"))
    )
    (net (code "381") (name "/p10_en") (class "Default")
      (node (ref "U9") (pin "26") (pinfunction "P7_26") (pintype "unspecified"))
    )
    (net (code "382") (name "/p11_en") (class "Default")
      (node (ref "U9") (pin "5") (pinfunction "P8_5") (pintype "unspecified"))
    )
    (net (code "383") (name "/p12_en") (class "Default")
      (node (ref "U9") (pin "7") (pinfunction "P9_7") (pintype "unspecified"))
    )
    (net (code "384") (name "/p13_en") (class "Default")
      (node (ref "U9") (pin "9") (pinfunction "P10_9") (pintype "unspecified"))
    )
    (net (code "385") (name "/p14_en") (class "Default")
      (node (ref "U9") (pin "11") (pinfunction "P11_11") (pintype "unspecified"))
    )
    (net (code "386") (name "/p15_en") (class "Default")
      (node (ref "U9") (pin "6") (pinfunction "P12_6") (pintype "unspecified"))
    )
    (net (code "387") (name "/p16_en") (class "Default")
      (node (ref "U9") (pin "8") (pinfunction "P13_8") (pintype "unspecified"))
    )
    (net (code "388") (name "/p17_en") (class "Default")
      (node (ref "U9") (pin "10") (pinfunction "P14_10") (pintype "unspecified"))
    )
    (net (code "389") (name "/p18_en") (class "Default")
      (node (ref "D2") (pin "2") (pinfunction "A_2") (pintype "unspecified"))
      (node (ref "R21") (pin "2") (pinfunction "2_2") (pintype "unspecified"))
      (node (ref "U9") (pin "12") (pinfunction "P15_12") (pintype "unspecified"))
    )
    (net (code "390") (name "/power_switch") (class "Default")
      (node (ref "C27") (pin "2") (pinfunction "2_2") (pintype "unspecified"))
      (node (ref "C48") (pin "2") (pinfunction "2_2") (pintype "unspecified"))
      (node (ref "D7") (pin "2") (pinfunction "A_2") (pintype "unspecified"))
      (node (ref "Q4") (pin "3") (pinfunction "S_3") (pintype "unspecified"))
      (node (ref "R40") (pin "2") (pinfunction "2_2") (pintype "unspecified"))
      (node (ref "RSH") (pin "2") (pinfunction "2_2") (pintype "unspecified"))
      (node (ref "U44") (pin "8") (pinfunction "VBUS_8") (pintype "unspecified"))
    )
    (net (code "391") (name "/ps") (class "Default")
      (node (ref "R29") (pin "1") (pinfunction "1_1") (pintype "unspecified"))
      (node (ref "U9") (pin "25") (pinfunction "P28_25") (pintype "unspecified"))
    )
    (net (code "392") (name "/psB") (class "Default")
      (node (ref "U55") (pin "6") (pinfunction "S_6") (pintype "unspecified"))
      (node (ref "U9") (pin "22") (pinfunction "P25_22") (pintype "unspecified"))
    )
    (net (code "393") (name "/t1") (class "Default")
      (node (ref "C6") (pin "1") (pinfunction "1_1") (pintype "input"))
      (node (ref "C7") (pin "1") (pinfunction "1_1") (pintype "input"))
      (node (ref "R10") (pin "1") (pinfunction "1_1") (pintype "unspecified"))
      (node (ref "R5") (pin "1") (pinfunction "1_1") (pintype "unspecified"))
      (node (ref "R6") (pin "2") (pinfunction "2_2") (pintype "unspecified"))
      (node (ref "R7") (pin "1") (pinfunction "1_1") (pintype "unspecified"))
      (node (ref "R8") (pin "2") (pinfunction "2_2") (pintype "unspecified"))
      (node (ref "R9") (pin "1") (pinfunction "1_1") (pintype "unspecified"))
      (node (ref "U6") (pin "2") (pinfunction "CH0_2") (pintype "unspecified"))
    )
    (net (code "394") (name "/t2") (class "Default")
      (node (ref "U6") (pin "3") (pinfunction "CH1_3") (pintype "unspecified"))
    )
    (net (code "395") (name "/t3") (class "Default")
      (node (ref "U6") (pin "4") (pinfunction "CH2_4") (pintype "unspecified"))
    )
    (net (code "396") (name "/t4") (class "Default")
      (node (ref "U6") (pin "5") (pinfunction "CH3_5") (pintype "unspecified"))
    )
    (net (code "397") (name "/tm_busy") (class "Default")
      (node (ref "R11") (pin "1") (pinfunction "1_1") (pintype "input"))
      (node (ref "U6") (pin "13") (pinfunction "BUSY_13") (pintype "unspecified"))
    )
    (net (code "398") (name "/tm_busy_R") (class "Default")
      (node (ref "R11") (pin "2") (pinfunction "2_2") (pintype "input"))
    )
    (net (code "399") (name "/tm_e") (class "Default")
      (node (ref "R12") (pin "1") (pinfunction "1_1") (pintype "input"))
      (node (ref "U6") (pin "7") (pinfunction "SHDN_7") (pintype "unspecified"))
      (node (ref "U9") (pin "27") (pinfunction "P29_27") (pintype "unspecified"))
    )
    (net (code "400") (name "/tm_e_R") (class "Default")
      (node (ref "R12") (pin "2") (pinfunction "2_2") (pintype "input"))
    )
    (net (code "401") (name "/v1_1") (class "Default")
      (node (ref "U19") (pin "-") (pinfunction "6_-") (pintype "unspecified"))
    )
    (net (code "402") (name "/v1_2") (class "Default")
      (node (ref "U18") (pin "-") (pinfunction "6_-") (pintype "unspecified"))
      (node (ref "U19") (pin "+") (pinfunction "5_+") (pintype "unspecified"))
    )
    (net (code "403") (name "/v1_3") (class "Default")
      (node (ref "U17") (pin "-") (pinfunction "6_-") (pintype "unspecified"))
    )
    (net (code "404") (name "/v1_4") (class "Default")
      (node (ref "U16") (pin "-") (pinfunction "6_-") (pintype "unspecified"))
      (node (ref "U17") (pin "+") (pinfunction "5_+") (pintype "unspecified"))
    )
    (net (code "405") (name "/v1_5") (class "Default")
      (node (ref "U15") (pin "-") (pinfunction "6_-") (pintype "unspecified"))
      (node (ref "U16") (pin "+") (pinfunction "5_+") (pintype "unspecified"))
    )
    (net (code "406") (name "/v1_6") (class "Default")
      (node (ref "U14") (pin "-") (pinfunction "6_-") (pintype "unspecified"))
      (node (ref "U15") (pin "+") (pinfunction "5_+") (pintype "unspecified"))
    )
    (net (code "407") (name "/v18_2") (class "Default")
      (node (ref "U25") (pin "-") (pinfunction "6_-") (pintype "unspecified"))
      (node (ref "U26") (pin "+") (pinfunction "5_+") (pintype "unspecified"))
    )
    (net (code "408") (name "/v18_3") (class "Default")
      (node (ref "U24") (pin "-") (pinfunction "6_-") (pintype "unspecified"))
    )
    (net (code "409") (name "/v18_4") (class "Default")
      (node (ref "U23") (pin "-") (pinfunction "6_-") (pintype "unspecified"))
      (node (ref "U24") (pin "+") (pinfunction "5_+") (pintype "unspecified"))
    )
    (net (code "410") (name "/v18_5") (class "Default")
      (node (ref "U22") (pin "-") (pinfunction "6_-") (pintype "unspecified"))
      (node (ref "U23") (pin "+") (pinfunction "5_+") (pintype "unspecified"))
    )
    (net (code "411") (name "/v18_6") (class "Default")
      (node (ref "U21") (pin "-") (pinfunction "6_-") (pintype "unspecified"))
      (node (ref "U22") (pin "+") (pinfunction "5_+") (pintype "unspecified"))
    )
    (net (code "412") (name "/v_msr_to_ADC") (class "Default")
      (node (ref "U45") (pin "6") (pinfunction "OUT_6") (pintype "unspecified"))
      (node (ref "U52") (pin "5") (pinfunction "AIN_5") (pintype "unspecified"))
    )
    (net (code "413") (name "/v_stab") (class "Default")
      (node (ref "C37") (pin "1") (pinfunction "1_1") (pintype "unspecified"))
      (node (ref "C40") (pin "2") (pinfunction "2_2") (pintype "unspecified"))
      (node (ref "R39") (pin "1") (pinfunction "1_1") (pintype "unspecified"))
      (node (ref "U45") (pin "7") (pinfunction "+VS_7") (pintype "unspecified"))
    )
    (net (code "414") (name "AGND") (class "Default")
      (node (ref "C35") (pin "2") (pinfunction "2_2") (pintype "unspecified"))
      (node (ref "C36") (pin "2") (pinfunction "2_2") (pintype "unspecified"))
      (node (ref "C4") (pin "2") (pinfunction "2_2") (pintype "input"))
      (node (ref "C43") (pin "1") (pinfunction "1_1") (pintype "input"))
      (node (ref "C45") (pin "2") (pinfunction "2_2") (pintype "input"))
      (node (ref "C5") (pin "2") (pinfunction "2_2") (pintype "input"))
      (node (ref "C6") (pin "2") (pinfunction "2_2") (pintype "input"))
      (node (ref "C64") (pin "1") (pinfunction "1_1") (pintype "unspecified"))
      (node (ref "C65") (pin "2") (pinfunction "2_2") (pintype "unspecified"))
      (node (ref "C7") (pin "2") (pinfunction "2_2") (pintype "input"))
      (node (ref "C70") (pin "1") (pinfunction "1_1") (pintype "unspecified"))
      (node (ref "D9") (pin "3") (pinfunction "A_3") (pintype "unspecified"))
      (node (ref "R6") (pin "1") (pinfunction "1_1") (pintype "unspecified"))
      (node (ref "R8") (pin "1") (pinfunction "1_1") (pintype "unspecified"))
      (node (ref "U29") (pin "4") (pinfunction "GROUND_4") (pintype "unspecified"))
      (node (ref "U29") (pin "8") (pinfunction "GROUND_8") (pintype "unspecified"))
      (node (ref "U49") (pin "1") (pinfunction "GND_1") (pintype "unspecified"))
    )
    (net (code "415") (name "DGND") (class "Default")
      (node (ref "C54") (pin "2") (pinfunction "2_2") (pintype "input"))
    )
    (net (code "416") (name "GND") (class "Default")
      (node (ref "BT1") (pin "2") (pinfunction "-_2") (pintype "passive"))
      (node (ref "C1") (pin "2") (pinfunction "2_2") (pintype "unspecified"))
      (node (ref "C10") (pin "1") (pinfunction "1_1") (pintype "unspecified"))
      (node (ref "C11") (pin "1") (pinfunction "1_1") (pintype "unspecified"))
      (node (ref "C12") (pin "1") (pinfunction "1_1") (pintype "unspecified"))
      (node (ref "C13") (pin "2") (pinfunction "2_2") (pintype "unspecified"))
      (node (ref "C14") (pin "2") (pinfunction "2_2") (pintype "unspecified"))
      (node (ref "C15") (pin "2") (pinfunction "2_2") (pintype "unspecified"))
      (node (ref "C16") (pin "2") (pinfunction "2_2") (pintype "unspecified"))
      (node (ref "C17") (pin "2") (pinfunction "2_2") (pintype "unspecified"))
      (node (ref "C18") (pin "1") (pinfunction "1_1") (pintype "unspecified"))
      (node (ref "C2") (pin "2") (pinfunction "2_2") (pintype "unspecified"))
      (node (ref "C20") (pin "1") (pinfunction "1_1") (pintype "input"))
      (node (ref "C21") (pin "1") (pinfunction "1_1") (pintype "input"))
      (node (ref "C23") (pin "1") (pinfunction "1_1") (pintype "unspecified"))
      (node (ref "C24") (pin "2") (pinfunction "2_2") (pintype "unspecified"))
      (node (ref "C25") (pin "2") (pinfunction "2_2") (pintype "unspecified"))
      (node (ref "C26") (pin "1") (pinfunction "1_1") (pintype "unspecified"))
      (node (ref "C27") (pin "1") (pinfunction "1_1") (pintype "unspecified"))
      (node (ref "C28") (pin "2") (pinfunction "2_2") (pintype "unspecified"))
      (node (ref "C29") (pin "2") (pinfunction "2_2") (pintype "unspecified"))
      (node (ref "C3") (pin "2") (pinfunction "2_2") (pintype "unspecified"))
      (node (ref "C30") (pin "2") (pinfunction "2_2") (pintype "unspecified"))
      (node (ref "C31") (pin "2") (pinfunction "2_2") (pintype "unspecified"))
      (node (ref "C33") (pin "2") (pinfunction "2_2") (pintype "unspecified"))
      (node (ref "C34") (pin "1") (pinfunction "1_1") (pintype "unspecified"))
      (node (ref "C37") (pin "2") (pinfunction "2_2") (pintype "unspecified"))
      (node (ref "C38") (pin "2") (pinfunction "2_2") (pintype "unspecified"))
      (node (ref "C39") (pin "2") (pinfunction "2_2") (pintype "unspecified"))
      (node (ref "C40") (pin "1") (pinfunction "1_1") (pintype "unspecified"))
      (node (ref "C41") (pin "1") (pinfunction "1_1") (pintype "unspecified"))
      (node (ref "C42") (pin "1") (pinfunction "1_1") (pintype "unspecified"))
      (node (ref "C44") (pin "1") (pinfunction "1_1") (pintype "unspecified"))
      (node (ref "C46") (pin "1") (pinfunction "1_1") (pintype "unspecified"))
      (node (ref "C49") (pin "1") (pinfunction "1_1") (pintype "unspecified"))
      (node (ref "C50") (pin "1") (pinfunction "1_1") (pintype "unspecified"))
      (node (ref "C51") (pin "1") (pinfunction "1_1") (pintype "unspecified"))
      (node (ref "C52") (pin "2") (pinfunction "2_2") (pintype "unspecified"))
      (node (ref "C53") (pin "2") (pinfunction "2_2") (pintype "unspecified"))
      (node (ref "C55") (pin "1") (pinfunction "1_1") (pintype "unspecified"))
      (node (ref "C58") (pin "2") (pinfunction "2_2") (pintype "unspecified"))
      (node (ref "C59") (pin "1") (pinfunction "1_1") (pintype "unspecified"))
      (node (ref "C60") (pin "2") (pinfunction "2_2") (pintype "unspecified"))
      (node (ref "C61") (pin "2") (pinfunction "2_2") (pintype "unspecified"))
      (node (ref "C62") (pin "2") (pinfunction "2_2") (pintype "unspecified"))
      (node (ref "C63") (pin "2") (pinfunction "2_2") (pintype "unspecified"))
      (node (ref "C66") (pin "1") (pinfunction "1_1") (pintype "unspecified"))
      (node (ref "C67") (pin "1") (pinfunction "1_1") (pintype "unspecified"))
      (node (ref "C73") (pin "2") (pinfunction "2_2") (pintype "unspecified"))
      (node (ref "C74") (pin "1") (pinfunction "1_1") (pintype "unspecified"))
      (node (ref "C8") (pin "1") (pinfunction "1_1") (pintype "unspecified"))
      (node (ref "C9") (pin "1") (pinfunction "1_1") (pintype "unspecified"))
      (node (ref "D1") (pin "1") (pinfunction "K_1") (pintype "unspecified"))
      (node (ref "D16") (pin "2") (pinfunction "A_2") (pintype "unspecified"))
      (node (ref "D17") (pin "2") (pinfunction "A_2") (pintype "unspecified"))
      (node (ref "D2") (pin "1") (pinfunction "K_1") (pintype "unspecified"))
      (node (ref "D5") (pin "2") (pinfunction "A_2") (pintype "unspecified"))
      (node (ref "D6") (pin "1") (pinfunction "1_1") (pintype "unspecified"))
      (node (ref "D8") (pin "2") (pinfunction "A_2") (pintype "unspecified"))
      (node (ref "KEY1") (pin "1") (pinfunction "1_1") (pintype "unspecified"))
      (node (ref "KEY2") (pin "1") (pinfunction "1_1") (pintype "unspecified"))
      (node (ref "LED1") (pin "2") (pinfunction "2_2") (pintype "unspecified"))
      (node (ref "LED2") (pin "2") (pinfunction "2_2") (pintype "unspecified"))
      (node (ref "LED3") (pin "2") (pinfunction "2_2") (pintype "unspecified"))
      (node (ref "LED4") (pin "2") (pinfunction "2_2") (pintype "unspecified"))
      (node (ref "LED5") (pin "2") (pinfunction "2_2") (pintype "unspecified"))
      (node (ref "LED6") (pin "2") (pinfunction "2_2") (pintype "unspecified"))
      (node (ref "LED7") (pin "2") (pinfunction "2_2") (pintype "unspecified"))
      (node (ref "Q3") (pin "2") (pinfunction "S_2") (pintype "unspecified"))
      (node (ref "R22") (pin "1") (pinfunction "1_1") (pintype "input"))
      (node (ref "R23") (pin "1") (pinfunction "1_1") (pintype "input"))
      (node (ref "R24") (pin "1") (pinfunction "1_1") (pintype "unspecified"))
      (node (ref "R25") (pin "1") (pinfunction "1_1") (pintype "unspecified"))
      (node (ref "R28") (pin "1") (pinfunction "1_1") (pintype "unspecified"))
      (node (ref "R30") (pin "1") (pinfunction "1_1") (pintype "unspecified"))
      (node (ref "R36") (pin "2") (pinfunction "2_2") (pintype "unspecified"))
      (node (ref "R4") (pin "2") (pinfunction "2_2") (pintype "input"))
      (node (ref "U10") (pin "23") (pinfunction "VSS_23") (pintype "unspecified"))
      (node (ref "U10") (pin "35") (pinfunction "VSS_35") (pintype "unspecified"))
      (node (ref "U10") (pin "47") (pinfunction "VSS_47") (pintype "unspecified"))
      (node (ref "U10") (pin "8") (pinfunction "VSSA/VREF-_8") (pintype "unspecified"))
      (node (ref "U2") (pin "2") (pinfunction "GND_2") (pintype "passive"))
      (node (ref "U26") (pin "-") (pinfunction "6_-") (pintype "unspecified"))
      (node (ref "U27") (pin "5") (pinfunction "GND_5") (pintype "unspecified"))
      (node (ref "U28") (pin "5") (pinfunction "GND_5") (pintype "unspecified"))
      (node (ref "U3") (pin "5") (pinfunction "GND_5") (pintype "unspecified"))
      (node (ref "U30") (pin "8") (pinfunction "GND_8") (pintype "unspecified"))
      (node (ref "U31") (pin "8") (pinfunction "GND_8") (pintype "unspecified"))
      (node (ref "U32") (pin "8") (pinfunction "GND_8") (pintype "unspecified"))
      (node (ref "U33") (pin "8") (pinfunction "GND_8") (pintype "unspecified"))
      (node (ref "U34") (pin "8") (pinfunction "GND_8") (pintype "unspecified"))
      (node (ref "U35") (pin "8") (pinfunction "GND_8") (pintype "unspecified"))
      (node (ref "U36") (pin "8") (pinfunction "GND_8") (pintype "unspecified"))
      (node (ref "U37") (pin "8") (pinfunction "GND_8") (pintype "unspecified"))
      (node (ref "U38") (pin "8") (pinfunction "GND_8") (pintype "unspecified"))
      (node (ref "U39") (pin "8") (pinfunction "GND_8") (pintype "unspecified"))
      (node (ref "U4") (pin "2") (pinfunction "GND_2") (pintype "unspecified"))
      (node (ref "U4") (pin "3") (pinfunction "GND_3") (pintype "unspecified"))
      (node (ref "U40") (pin "8") (pinfunction "GND_8") (pintype "unspecified"))
      (node (ref "U41") (pin "8") (pinfunction "GND_8") (pintype "unspecified"))
      (node (ref "U42") (pin "8") (pinfunction "GND_8") (pintype "unspecified"))
      (node (ref "U43") (pin "2") (pinfunction "Y6_2") (pintype "unspecified"))
      (node (ref "U43") (pin "4") (pinfunction "Y7_4") (pintype "unspecified"))
      (node (ref "U43") (pin "5") (pinfunction "Y5_5") (pintype "unspecified"))
      (node (ref "U43") (pin "8") (pinfunction "GND_8") (pintype "unspecified"))
      (node (ref "U44") (pin "7") (pinfunction "GND_7") (pintype "unspecified"))
      (node (ref "U45") (pin "4") (pinfunction "-VS_4") (pintype "unspecified"))
      (node (ref "U5") (pin "2") (pinfunction "GND_2") (pintype "unspecified"))
      (node (ref "U5") (pin "3") (pinfunction "GND_3") (pintype "unspecified"))
      (node (ref "U52") (pin "2") (pinfunction "DGND_2") (pintype "passive"))
      (node (ref "U52") (pin "4") (pinfunction "AGND_4") (pintype "passive"))
      (node (ref "U52") (pin "8") (pinfunction "AGND_8") (pintype "passive"))
      (node (ref "U56") (pin "2") (pinfunction "GND_2") (pintype "unspecified"))
      (node (ref "U56") (pin "3") (pinfunction "B0_3") (pintype "unspecified"))
      (node (ref "U57") (pin "2") (pinfunction "GND_2") (pintype "unspecified"))
      (node (ref "U57") (pin "3") (pinfunction "B0_3") (pintype "unspecified"))
      (node (ref "U6") (pin "10") (pinfunction "GND_10") (pintype "passive"))
      (node (ref "U6") (pin "11") (pinfunction "MODE_11") (pintype "unspecified"))
      (node (ref "U6") (pin "6") (pinfunction "COM_6") (pintype "passive"))
      (node (ref "U7") (pin "2") (pinfunction "GND_2") (pintype "unspecified"))
      (node (ref "U7") (pin "3") (pinfunction "GND_3") (pintype "unspecified"))
      (node (ref "U8") (pin "8") (pinfunction "GND_8") (pintype "unspecified"))
      (node (ref "U9") (pin "2") (pinfunction "GND_2") (pintype "unspecified"))
      (node (ref "U9") (pin "3") (pinfunction "GND_3") (pintype "unspecified"))
    )
    (net (code "417") (name "Net-(C18-Pad2)") (class "Default")
      (node (ref "C18") (pin "2") (pinfunction "2_2") (pintype "unspecified"))
      (node (ref "R26") (pin "1") (pinfunction "1_1") (pintype "input"))
    )
    (net (code "418") (name "Net-(C22-Pad1)") (class "Default")
      (node (ref "C22") (pin "1") (pinfunction "1_1") (pintype "unspecified"))
      (node (ref "R25") (pin "2") (pinfunction "2_2") (pintype "unspecified"))
    )
    (net (code "419") (name "Net-(D5-C)") (class "Default")
      (node (ref "D5") (pin "1") (pinfunction "C_1") (pintype "unspecified"))
      (node (ref "D7") (pin "1") (pinfunction "C_1") (pintype "unspecified"))
      (node (ref "F1") (pin "2") (pinfunction "2_2") (pintype "unspecified"))
      (node (ref "Q4") (pin "2") (pinfunction "D_2") (pintype "unspecified"))
      (node (ref "R26") (pin "2") (pinfunction "2_2") (pintype "input"))
      (node (ref "R31") (pin "2") (pinfunction "2_2") (pintype "input"))
    )
    (net (code "420") (name "Net-(D8-C)") (class "Default")
      (node (ref "D8") (pin "1") (pinfunction "C_1") (pintype "unspecified"))
      (node (ref "Q3") (pin "3") (pinfunction "D_3") (pintype "unspecified"))
      (node (ref "R32") (pin "1") (pinfunction "1_1") (pintype "unspecified"))
    )
    (net (code "421") (name "Net-(D9-K)") (class "Default")
      (node (ref "C32") (pin "2") (pinfunction "2_2") (pintype "input"))
      (node (ref "D9") (pin "4") (pinfunction "K_4") (pintype "unspecified"))
      (node (ref "L1") (pin "1") (pinfunction "1_1") (pintype "unspecified"))
      (node (ref "U29") (pin "1") (pinfunction "SW_OUT_1") (pintype "unspecified"))
    )
    (net (code "422") (name "Net-(D18-A)") (class "Default")
      (node (ref "D18") (pin "2") (pinfunction "A_2") (pintype "unspecified"))
      (node (ref "Q7") (pin "2") (pinfunction "S_2") (pintype "unspecified"))
      (node (ref "R48") (pin "2") (pinfunction "2_2") (pintype "unspecified"))
    )
    (net (code "423") (name "Net-(D21-A)") (class "Default")
      (node (ref "D21") (pin "2") (pinfunction "A_2") (pintype "unspecified"))
      (node (ref "D22") (pin "1") (pinfunction "C_1") (pintype "unspecified"))
      (node (ref "Q8") (pin "5") (pinfunction "D2_5") (pintype "unspecified"))
      (node (ref "Q8") (pin "6") (pinfunction "D2_6") (pintype "unspecified"))
      (node (ref "Q8") (pin "7") (pinfunction "D1_7") (pintype "unspecified"))
      (node (ref "Q8") (pin "8") (pinfunction "D1_8") (pintype "unspecified"))
      (node (ref "U54") (pin "2") (pinfunction "2_2") (pintype "unspecified"))
    )
    (net (code "424") (name "Net-(D23-A)") (class "Default")
      (node (ref "C75") (pin "2") (pinfunction "2_2") (pintype "unspecified"))
      (node (ref "D23") (pin "2") (pinfunction "A_2") (pintype "unspecified"))
      (node (ref "Q8") (pin "4") (pinfunction "G2_4") (pintype "unspecified"))
      (node (ref "R51") (pin "2") (pinfunction "2_2") (pintype "unspecified"))
    )
    (net (code "425") (name "Net-(D24-C)") (class "Default")
      (node (ref "C76") (pin "2") (pinfunction "2_2") (pintype "unspecified"))
      (node (ref "D24") (pin "1") (pinfunction "C_1") (pintype "unspecified"))
      (node (ref "Q8") (pin "2") (pinfunction "G1_2") (pintype "unspecified"))
      (node (ref "R52") (pin "2") (pinfunction "2_2") (pintype "unspecified"))
    )
    (net (code "426") (name "Net-(L3-Pad2)") (class "Default")
      (node (ref "L3") (pin "2") (pinfunction "2_2") (pintype "unspecified"))
      (node (ref "R49") (pin "2") (pinfunction "2_2") (pintype "unspecified"))
      (node (ref "U54") (pin "1") (pinfunction "1_1") (pintype "unspecified"))
    )
    (net (code "427") (name "Net-(LED1-Pad1)") (class "Default")
      (node (ref "LED1") (pin "1") (pinfunction "1_1") (pintype "unspecified"))
      (node (ref "R13") (pin "2") (pinfunction "2_2") (pintype "input"))
    )
    (net (code "428") (name "Net-(LED2-Pad1)") (class "Default")
      (node (ref "LED2") (pin "1") (pinfunction "1_1") (pintype "unspecified"))
      (node (ref "R14") (pin "2") (pinfunction "2_2") (pintype "input"))
    )
    (net (code "429") (name "Net-(LED3-Pad1)") (class "Default")
      (node (ref "LED3") (pin "1") (pinfunction "1_1") (pintype "unspecified"))
      (node (ref "R15") (pin "2") (pinfunction "2_2") (pintype "input"))
    )
    (net (code "430") (name "Net-(LED4-Pad1)") (class "Default")
      (node (ref "LED4") (pin "1") (pinfunction "1_1") (pintype "unspecified"))
      (node (ref "R16") (pin "2") (pinfunction "2_2") (pintype "input"))
    )
    (net (code "431") (name "Net-(LED5-Pad1)") (class "Default")
      (node (ref "LED5") (pin "1") (pinfunction "1_1") (pintype "unspecified"))
      (node (ref "R17") (pin "2") (pinfunction "2_2") (pintype "input"))
    )
    (net (code "432") (name "Net-(LED6-Pad1)") (class "Default")
      (node (ref "LED6") (pin "1") (pinfunction "1_1") (pintype "unspecified"))
      (node (ref "R18") (pin "2") (pinfunction "2_2") (pintype "input"))
    )
    (net (code "433") (name "Net-(LED7-Pad1)") (class "Default")
      (node (ref "LED7") (pin "1") (pinfunction "1_1") (pintype "unspecified"))
      (node (ref "R19") (pin "2") (pinfunction "2_2") (pintype "input"))
    )
    (net (code "434") (name "Net-(Q1-G)") (class "Default")
      (node (ref "Q1") (pin "1") (pinfunction "G_1") (pintype "unspecified"))
      (node (ref "R20") (pin "1") (pinfunction "1_1") (pintype "unspecified"))
      (node (ref "R22") (pin "2") (pinfunction "2_2") (pintype "input"))
    )
    (net (code "435") (name "Net-(Q2-G)") (class "Default")
      (node (ref "Q2") (pin "1") (pinfunction "G_1") (pintype "unspecified"))
      (node (ref "R21") (pin "1") (pinfunction "1_1") (pintype "unspecified"))
      (node (ref "R23") (pin "2") (pinfunction "2_2") (pintype "input"))
    )
    (net (code "436") (name "Net-(Q3-G)") (class "Default")
      (node (ref "D6") (pin "2") (pinfunction "2_2") (pintype "unspecified"))
      (node (ref "Q3") (pin "1") (pinfunction "G_1") (pintype "unspecified"))
      (node (ref "R29") (pin "2") (pinfunction "2_2") (pintype "unspecified"))
      (node (ref "R30") (pin "2") (pinfunction "2_2") (pintype "unspecified"))
    )
    (net (code "437") (name "Net-(Q4-G)") (class "Default")
      (node (ref "Q4") (pin "1") (pinfunction "G_1") (pintype "unspecified"))
      (node (ref "R31") (pin "1") (pinfunction "1_1") (pintype "input"))
      (node (ref "R32") (pin "2") (pinfunction "2_2") (pintype "unspecified"))
    )
    (net (code "438") (name "Net-(Q5-G)") (class "Default")
      (node (ref "Q5") (pin "3") (pinfunction "G_3") (pintype "unspecified"))
      (node (ref "R44") (pin "1") (pinfunction "1_1") (pintype "unspecified"))
      (node (ref "R46") (pin "2") (pinfunction "2_2") (pintype "unspecified"))
    )
    (net (code "439") (name "Net-(Q6-G)") (class "Default")
      (node (ref "Q6") (pin "3") (pinfunction "G_3") (pintype "unspecified"))
      (node (ref "R45") (pin "1") (pinfunction "1_1") (pintype "unspecified"))
      (node (ref "R47") (pin "2") (pinfunction "2_2") (pintype "unspecified"))
    )
    (net (code "440") (name "Net-(U8-Q1)") (class "Default")
      (node (ref "R19") (pin "1") (pinfunction "1_1") (pintype "input"))
      (node (ref "U8") (pin "1") (pinfunction "Q1_1") (pintype "unspecified"))
    )
    (net (code "441") (name "Net-(U8-Q2)") (class "Default")
      (node (ref "R18") (pin "1") (pinfunction "1_1") (pintype "input"))
      (node (ref "U8") (pin "2") (pinfunction "Q2_2") (pintype "unspecified"))
    )
    (net (code "442") (name "Net-(U8-Q3)") (class "Default")
      (node (ref "R17") (pin "1") (pinfunction "1_1") (pintype "input"))
      (node (ref "U8") (pin "3") (pinfunction "Q3_3") (pintype "unspecified"))
    )
    (net (code "443") (name "Net-(U8-Q4)") (class "Default")
      (node (ref "R16") (pin "1") (pinfunction "1_1") (pintype "input"))
      (node (ref "U8") (pin "4") (pinfunction "Q4_4") (pintype "unspecified"))
    )
    (net (code "444") (name "Net-(U8-Q5)") (class "Default")
      (node (ref "R15") (pin "1") (pinfunction "1_1") (pintype "input"))
      (node (ref "U8") (pin "5") (pinfunction "Q5_5") (pintype "unspecified"))
    )
    (net (code "445") (name "Net-(U8-Q6)") (class "Default")
      (node (ref "R14") (pin "1") (pinfunction "1_1") (pintype "input"))
      (node (ref "U8") (pin "6") (pinfunction "Q6_6") (pintype "unspecified"))
    )
    (net (code "446") (name "Net-(U8-Q7)") (class "Default")
      (node (ref "R13") (pin "1") (pinfunction "1_1") (pintype "input"))
      (node (ref "U8") (pin "7") (pinfunction "Q7_7") (pintype "unspecified"))
    )
    (net (code "447") (name "Net-(U29-C_BOOST)") (class "Default")
      (node (ref "C32") (pin "1") (pinfunction "1_1") (pintype "input"))
      (node (ref "U29") (pin "3") (pinfunction "C_BOOST_3") (pintype "unspecified"))
    )
    (net (code "448") (name "Net-(U44-IN+)") (class "Default")
      (node (ref "R40") (pin "1") (pinfunction "1_1") (pintype "unspecified"))
      (node (ref "U44") (pin "10") (pinfunction "IN+_10") (pintype "unspecified"))
    )
    (net (code "449") (name "Net-(U44-IN-)") (class "Default")
      (node (ref "R41") (pin "1") (pinfunction "1_1") (pintype "unspecified"))
      (node (ref "U44") (pin "9") (pinfunction "IN-_9") (pintype "unspecified"))
    )
    (net (code "450") (name "Net-(U44-VS)") (class "Default")
      (node (ref "C44") (pin "2") (pinfunction "2_2") (pintype "unspecified"))
      (node (ref "U44") (pin "6") (pinfunction "VS_6") (pintype "unspecified"))
    )
    (net (code "451") (name "Net-(U45-+IN)") (class "Default")
      (node (ref "C34") (pin "2") (pinfunction "2_2") (pintype "unspecified"))
      (node (ref "R35") (pin "2") (pinfunction "2_2") (pintype "unspecified"))
      (node (ref "U45") (pin "3") (pinfunction "+IN_3") (pintype "unspecified"))
    )
    (net (code "452") (name "Net-(U45--IN)") (class "Default")
      (node (ref "C33") (pin "1") (pinfunction "1_1") (pintype "unspecified"))
      (node (ref "R34") (pin "2") (pinfunction "2_2") (pintype "unspecified"))
      (node (ref "U45") (pin "2") (pinfunction "-IN_2") (pintype "unspecified"))
    )
    (net (code "453") (name "Net-(U45-REF)") (class "Default")
      (node (ref "R36") (pin "1") (pinfunction "1_1") (pintype "unspecified"))
      (node (ref "U45") (pin "1") (pinfunction "REF_1") (pintype "unspecified"))
    )
    (net (code "454") (name "Net-(U45-SENSE)") (class "Default")
      (node (ref "R39") (pin "2") (pinfunction "2_2") (pintype "unspecified"))
      (node (ref "U45") (pin "5") (pinfunction "SENSE_5") (pintype "unspecified"))
    )
    (net (code "455") (name "Net-(U52-REF)") (class "Default")
      (node (ref "C63") (pin "1") (pinfunction "1_1") (pintype "unspecified"))
      (node (ref "U52") (pin "6") (pinfunction "REF_6") (pintype "unspecified"))
    )
    (net (code "456") (name "Net-(U55-A)") (class "Default")
      (node (ref "R50") (pin "2") (pinfunction "2_2") (pintype "unspecified"))
      (node (ref "U55") (pin "4") (pinfunction "A_4") (pintype "unspecified"))
    )
    (net (code "457") (name "Net-(U55-B0)") (class "Default")
      (node (ref "U55") (pin "2") (pinfunction "GND_2") (pintype "unspecified"))
      (node (ref "U55") (pin "3") (pinfunction "B0_3") (pintype "unspecified"))
    )
    (net (code "458") (name "Net-(U56-A)") (class "Default")
      (node (ref "C75") (pin "1") (pinfunction "1_1") (pintype "unspecified"))
      (node (ref "U56") (pin "4") (pinfunction "A_4") (pintype "unspecified"))
    )
    (net (code "459") (name "Net-(U57-A)") (class "Default")
      (node (ref "C76") (pin "1") (pinfunction "1_1") (pintype "unspecified"))
      (node (ref "U57") (pin "4") (pinfunction "A_4") (pintype "unspecified"))
    )
    (net (code "460") (name "unconnected-(C19-Pad1)") (class "Default")
      (node (ref "C19") (pin "1") (pinfunction "1_1") (pintype "input"))
    )
    (net (code "461") (name "unconnected-(C47-Pad1)") (class "Default")
      (node (ref "C47") (pin "1") (pinfunction "1_1") (pintype "unspecified"))
    )
    (net (code "462") (name "unconnected-(C47-Pad2)") (class "Default")
      (node (ref "C47") (pin "2") (pinfunction "2_2") (pintype "unspecified"))
    )
    (net (code "463") (name "unconnected-(C56-Pad1)") (class "Default")
      (node (ref "C56") (pin "1") (pinfunction "1_1") (pintype "unspecified"))
    )
    (net (code "464") (name "unconnected-(C56-Pad2)") (class "Default")
      (node (ref "C56") (pin "2") (pinfunction "2_2") (pintype "unspecified"))
    )
    (net (code "465") (name "unconnected-(C57-Pad1)") (class "Default")
      (node (ref "C57") (pin "1") (pinfunction "1_1") (pintype "unspecified"))
    )
    (net (code "466") (name "unconnected-(C57-Pad2)") (class "Default")
      (node (ref "C57") (pin "2") (pinfunction "2_2") (pintype "unspecified"))
    )
    (net (code "467") (name "unconnected-(C68-Pad1)") (class "Default")
      (node (ref "C68") (pin "1") (pinfunction "1_1") (pintype "unspecified"))
    )
    (net (code "468") (name "unconnected-(C68-Pad2)") (class "Default")
      (node (ref "C68") (pin "2") (pinfunction "2_2") (pintype "unspecified"))
    )
    (net (code "469") (name "unconnected-(D9-NC-Pad1)") (class "Default")
      (node (ref "D9") (pin "1") (pinfunction "NC_1") (pintype "unspecified"))
    )
    (net (code "470") (name "unconnected-(Q7-G-Pad1)") (class "Default")
      (node (ref "Q7") (pin "1") (pinfunction "G_1") (pintype "unspecified"))
    )
    (net (code "471") (name "unconnected-(R50-Pad1)") (class "Default")
      (node (ref "R50") (pin "1") (pinfunction "1_1") (pintype "unspecified"))
    )
    (net (code "472") (name "unconnected-(U1-Pad1)") (class "Default")
      (node (ref "U1") (pin "1") (pinfunction "1_1") (pintype "unspecified"))
    )
    (net (code "473") (name "unconnected-(U1-Pad2)") (class "Default")
      (node (ref "U1") (pin "2") (pinfunction "2_2") (pintype "unspecified"))
    )
    (net (code "474") (name "unconnected-(U2-SD_CS-Pad15)") (class "Default")
      (node (ref "U2") (pin "15") (pinfunction "SD_CS_15") (pintype "unspecified+no_connect"))
    )
    (net (code "475") (name "unconnected-(U2-SD_MISO-Pad17)") (class "Default")
      (node (ref "U2") (pin "17") (pinfunction "SD_MISO_17") (pintype "unspecified+no_connect"))
    )
    (net (code "476") (name "unconnected-(U2-SD_MOSI-Pad16)") (class "Default")
      (node (ref "U2") (pin "16") (pinfunction "SD_MOSI_16") (pintype "unspecified+no_connect"))
    )
    (net (code "477") (name "unconnected-(U2-SD_SCK-Pad18)") (class "Default")
      (node (ref "U2") (pin "18") (pinfunction "SD_SCK_18") (pintype "unspecified+no_connect"))
    )
    (net (code "478") (name "unconnected-(U8-Q0-Pad15)") (class "Default")
      (node (ref "U8") (pin "15") (pinfunction "Q0_15") (pintype "unspecified"))
    )
    (net (code "479") (name "unconnected-(U8-Q7S-Pad9)") (class "Default")
      (node (ref "U8") (pin "9") (pinfunction "Q7S_9") (pintype "unspecified"))
    )
    (net (code "480") (name "unconnected-(U10-EP-Pad49)") (class "Default")
      (node (ref "U10") (pin "49") (pinfunction "EP_49") (pintype "unspecified"))
    )
    (net (code "481") (name "unconnected-(U11-AIN9-Pad11)") (class "Default")
      (node (ref "U11") (pin "11") (pinfunction "AIN9_11") (pintype "unspecified+no_connect"))
    )
    (net (code "482") (name "unconnected-(U11-AIN10-Pad12)") (class "Default")
      (node (ref "U11") (pin "12") (pinfunction "AIN10_12") (pintype "unspecified+no_connect"))
    )
    (net (code "483") (name "unconnected-(U18-5-Pad+)") (class "Default")
      (node (ref "U18") (pin "+") (pinfunction "5_+") (pintype "unspecified"))
    )
    (net (code "484") (name "unconnected-(U25-5-Pad+)") (class "Default")
      (node (ref "U25") (pin "+") (pinfunction "5_+") (pintype "unspecified"))
    )
    (net (code "485") (name "unconnected-(U29-Pad5)") (class "Default")
      (node (ref "U29") (pin "5") (pinfunction "5_5") (pintype "unspecified"))
    )
    (net (code "486") (name "unconnected-(U30-NC-Pad7)") (class "Default")
      (node (ref "U30") (pin "7") (pinfunction "NC_7") (pintype "unspecified+no_connect"))
    )
    (net (code "487") (name "unconnected-(U31-NC-Pad7)") (class "Default")
      (node (ref "U31") (pin "7") (pinfunction "NC_7") (pintype "unspecified+no_connect"))
    )
    (net (code "488") (name "unconnected-(U32-NC-Pad7)") (class "Default")
      (node (ref "U32") (pin "7") (pinfunction "NC_7") (pintype "unspecified+no_connect"))
    )
    (net (code "489") (name "unconnected-(U33-NC-Pad7)") (class "Default")
      (node (ref "U33") (pin "7") (pinfunction "NC_7") (pintype "unspecified+no_connect"))
    )
    (net (code "490") (name "unconnected-(U34-NC-Pad7)") (class "Default")
      (node (ref "U34") (pin "7") (pinfunction "NC_7") (pintype "unspecified+no_connect"))
    )
    (net (code "491") (name "unconnected-(U35-NC-Pad7)") (class "Default")
      (node (ref "U35") (pin "7") (pinfunction "NC_7") (pintype "unspecified+no_connect"))
    )
    (net (code "492") (name "unconnected-(U36-NC-Pad7)") (class "Default")
      (node (ref "U36") (pin "7") (pinfunction "NC_7") (pintype "unspecified+no_connect"))
    )
    (net (code "493") (name "unconnected-(U37-NC-Pad7)") (class "Default")
      (node (ref "U37") (pin "7") (pinfunction "NC_7") (pintype "unspecified+no_connect"))
    )
    (net (code "494") (name "unconnected-(U38-NC-Pad7)") (class "Default")
      (node (ref "U38") (pin "7") (pinfunction "NC_7") (pintype "unspecified+no_connect"))
    )
    (net (code "495") (name "unconnected-(U39-NC-Pad7)") (class "Default")
      (node (ref "U39") (pin "7") (pinfunction "NC_7") (pintype "unspecified+no_connect"))
    )
    (net (code "496") (name "unconnected-(U40-NC-Pad7)") (class "Default")
      (node (ref "U40") (pin "7") (pinfunction "NC_7") (pintype "unspecified+no_connect"))
    )
    (net (code "497") (name "unconnected-(U41-NC-Pad7)") (class "Default")
      (node (ref "U41") (pin "7") (pinfunction "NC_7") (pintype "unspecified+no_connect"))
    )
    (net (code "498") (name "unconnected-(U42-NC-Pad7)") (class "Default")
      (node (ref "U42") (pin "7") (pinfunction "NC_7") (pintype "unspecified+no_connect"))
    )
    (net (code "499") (name "unconnected-(U43-NC-Pad7)") (class "Default")
      (node (ref "U43") (pin "7") (pinfunction "NC_7") (pintype "unspecified+no_connect"))
    )
    (net (code "500") (name "unconnected-(U45-NC-Pad8)") (class "Default")
      (node (ref "U45") (pin "8") (pinfunction "NC_8") (pintype "unspecified+no_connect"))
    )
    (net (code "501") (name "unconnected-(U46-GND-Pad12)") (class "Default")
      (node (ref "U46") (pin "12") (pinfunction "GND_12") (pintype "unspecified"))
    )
    (net (code "502") (name "unconnected-(U46-NC-Pad2)") (class "Default")
      (node (ref "U46") (pin "2") (pinfunction "NC_2") (pintype "unspecified+no_connect"))
    )
    (net (code "503") (name "unconnected-(U46-NC-Pad3)") (class "Default")
      (node (ref "U46") (pin "3") (pinfunction "NC_3") (pintype "unspecified+no_connect"))
    )
    (net (code "504") (name "unconnected-(U46-NC-Pad13)") (class "Default")
      (node (ref "U46") (pin "13") (pinfunction "NC_13") (pintype "unspecified+no_connect"))
    )
    (net (code "505") (name "unconnected-(U46-VSS-Pad27)") (class "Default")
      (node (ref "U46") (pin "27") (pinfunction "VSS_27") (pintype "unspecified"))
    )
    (net (code "506") (name "unconnected-(U47-EP-Pad33)") (class "Default")
      (node (ref "U47") (pin "33") (pinfunction "EP_33") (pintype "passive"))
    )
    (net (code "507") (name "unconnected-(U47-GND-Pad9)") (class "Default")
      (node (ref "U47") (pin "9") (pinfunction "GND_9") (pintype "passive"))
    )
    (net (code "508") (name "unconnected-(U47-NC-Pad12)") (class "Default")
      (node (ref "U47") (pin "12") (pinfunction "NC_12") (pintype "unspecified+no_connect"))
    )
    (net (code "509") (name "unconnected-(U47-NC-Pad13)") (class "Default")
      (node (ref "U47") (pin "13") (pinfunction "NC_13") (pintype "unspecified+no_connect"))
    )
    (net (code "510") (name "unconnected-(U47-NC-Pad26)") (class "Default")
      (node (ref "U47") (pin "26") (pinfunction "NC_26") (pintype "unspecified+no_connect"))
    )
    (net (code "511") (name "unconnected-(U47-NC-Pad27)") (class "Default")
      (node (ref "U47") (pin "27") (pinfunction "NC_27") (pintype "unspecified+no_connect"))
    )
    (net (code "512") (name "unconnected-(U47-NC-Pad28)") (class "Default")
      (node (ref "U47") (pin "28") (pinfunction "NC_28") (pintype "unspecified+no_connect"))
    )
    (net (code "513") (name "unconnected-(U47-NC-Pad30)") (class "Default")
      (node (ref "U47") (pin "30") (pinfunction "NC_30") (pintype "unspecified+no_connect"))
    )
    (net (code "514") (name "unconnected-(U47-NC-Pad32)") (class "Default")
      (node (ref "U47") (pin "32") (pinfunction "NC_32") (pintype "unspecified+no_connect"))
    )
    (net (code "515") (name "unconnected-(U48-EP-Pad33)") (class "Default")
      (node (ref "U48") (pin "33") (pinfunction "EP_33") (pintype "passive"))
    )
    (net (code "516") (name "unconnected-(U48-GND-Pad9)") (class "Default")
      (node (ref "U48") (pin "9") (pinfunction "GND_9") (pintype "passive"))
    )
    (net (code "517") (name "unconnected-(U48-NC-Pad12)") (class "Default")
      (node (ref "U48") (pin "12") (pinfunction "NC_12") (pintype "unspecified+no_connect"))
    )
    (net (code "518") (name "unconnected-(U48-NC-Pad13)") (class "Default")
      (node (ref "U48") (pin "13") (pinfunction "NC_13") (pintype "unspecified+no_connect"))
    )
    (net (code "519") (name "unconnected-(U48-NC-Pad26)") (class "Default")
      (node (ref "U48") (pin "26") (pinfunction "NC_26") (pintype "unspecified+no_connect"))
    )
    (net (code "520") (name "unconnected-(U48-NC-Pad27)") (class "Default")
      (node (ref "U48") (pin "27") (pinfunction "NC_27") (pintype "unspecified+no_connect"))
    )
    (net (code "521") (name "unconnected-(U48-NC-Pad28)") (class "Default")
      (node (ref "U48") (pin "28") (pinfunction "NC_28") (pintype "unspecified+no_connect"))
    )
    (net (code "522") (name "unconnected-(U48-NC-Pad30)") (class "Default")
      (node (ref "U48") (pin "30") (pinfunction "NC_30") (pintype "unspecified+no_connect"))
    )
    (net (code "523") (name "unconnected-(U48-NC-Pad32)") (class "Default")
      (node (ref "U48") (pin "32") (pinfunction "NC_32") (pintype "unspecified+no_connect"))
    )
    (net (code "524") (name "unconnected-(U50-GND-Pad12)") (class "Default")
      (node (ref "U50") (pin "12") (pinfunction "GND_12") (pintype "unspecified"))
    )
    (net (code "525") (name "unconnected-(U50-NC-Pad2)") (class "Default")
      (node (ref "U50") (pin "2") (pinfunction "NC_2") (pintype "unspecified+no_connect"))
    )
    (net (code "526") (name "unconnected-(U50-NC-Pad3)") (class "Default")
      (node (ref "U50") (pin "3") (pinfunction "NC_3") (pintype "unspecified+no_connect"))
    )
    (net (code "527") (name "unconnected-(U50-NC-Pad13)") (class "Default")
      (node (ref "U50") (pin "13") (pinfunction "NC_13") (pintype "unspecified+no_connect"))
    )
    (net (code "528") (name "unconnected-(U50-VSS-Pad27)") (class "Default")
      (node (ref "U50") (pin "27") (pinfunction "VSS_27") (pintype "unspecified"))
    )
    (net (code "529") (name "unconnected-(U51-EP-Pad33)") (class "Default")
      (node (ref "U51") (pin "33") (pinfunction "EP_33") (pintype "passive"))
    )
    (net (code "530") (name "unconnected-(U51-GND-Pad9)") (class "Default")
      (node (ref "U51") (pin "9") (pinfunction "GND_9") (pintype "passive"))
    )
    (net (code "531") (name "unconnected-(U51-NC-Pad12)") (class "Default")
      (node (ref "U51") (pin "12") (pinfunction "NC_12") (pintype "unspecified+no_connect"))
    )
    (net (code "532") (name "unconnected-(U51-NC-Pad13)") (class "Default")
      (node (ref "U51") (pin "13") (pinfunction "NC_13") (pintype "unspecified+no_connect"))
    )
    (net (code "533") (name "unconnected-(U51-NC-Pad26)") (class "Default")
      (node (ref "U51") (pin "26") (pinfunction "NC_26") (pintype "unspecified+no_connect"))
    )
    (net (code "534") (name "unconnected-(U51-NC-Pad27)") (class "Default")
      (node (ref "U51") (pin "27") (pinfunction "NC_27") (pintype "unspecified+no_connect"))
    )
    (net (code "535") (name "unconnected-(U51-NC-Pad28)") (class "Default")
      (node (ref "U51") (pin "28") (pinfunction "NC_28") (pintype "unspecified+no_connect"))
    )
    (net (code "536") (name "unconnected-(U51-NC-Pad30)") (class "Default")
      (node (ref "U51") (pin "30") (pinfunction "NC_30") (pintype "unspecified+no_connect"))
    )
    (net (code "537") (name "unconnected-(U51-NC-Pad32)") (class "Default")
      (node (ref "U51") (pin "32") (pinfunction "NC_32") (pintype "unspecified+no_connect"))
    )
    (net (code "538") (name "unconnected-(U53-1-PadVin)") (class "Default")
      (node (ref "U53") (pin "Vin") (pinfunction "1_Vin") (pintype "unspecified"))
    )
    (net (code "539") (name "unconnected-(U53-2-PadGND)") (class "Default")
      (node (ref "U53") (pin "GND") (pinfunction "2_GND") (pintype "unspecified"))
    )
    (net (code "540") (name "unconnected-(U53-3-PadVout+)") (class "Default")
      (node (ref "U53") (pin "Vout+") (pinfunction "3_Vout+") (pintype "unspecified"))
    )
    (net (code "541") (name "unconnected-(U53-4-PadGND)") (class "Default")
      (node (ref "U53") (pin "GND") (pinfunction "4_GND") (pintype "unspecified"))
    )
    (net (code "542") (name "unconnected-(U53-5-PadVout-)") (class "Default")
      (node (ref "U53") (pin "Vout-") (pinfunction "5_Vout-") (pintype "unspecified"))
    )
  )
)
